# 63-00013_Battery_PCB_6_3.net
KiCad netlist of a schematic drawn in EAGLE
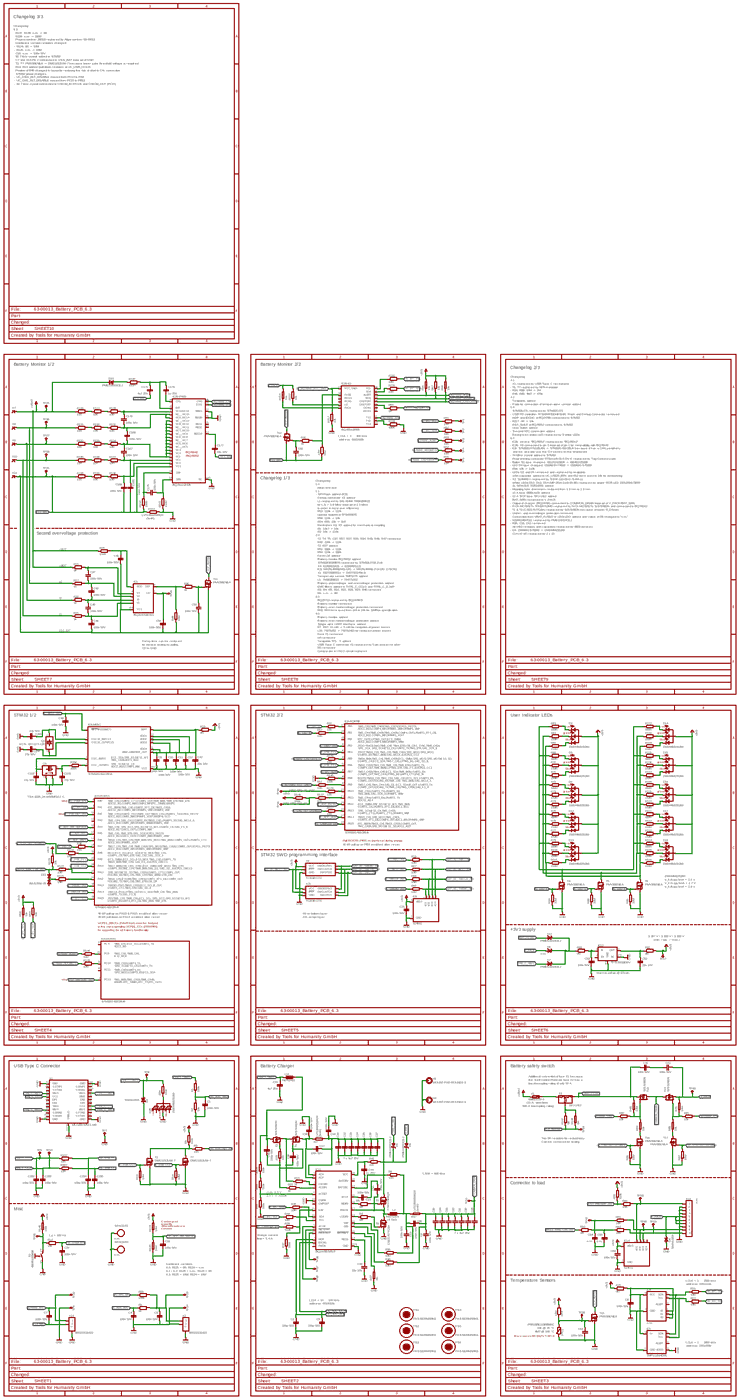
[diagram p0: schematic, sheet 1, overview]
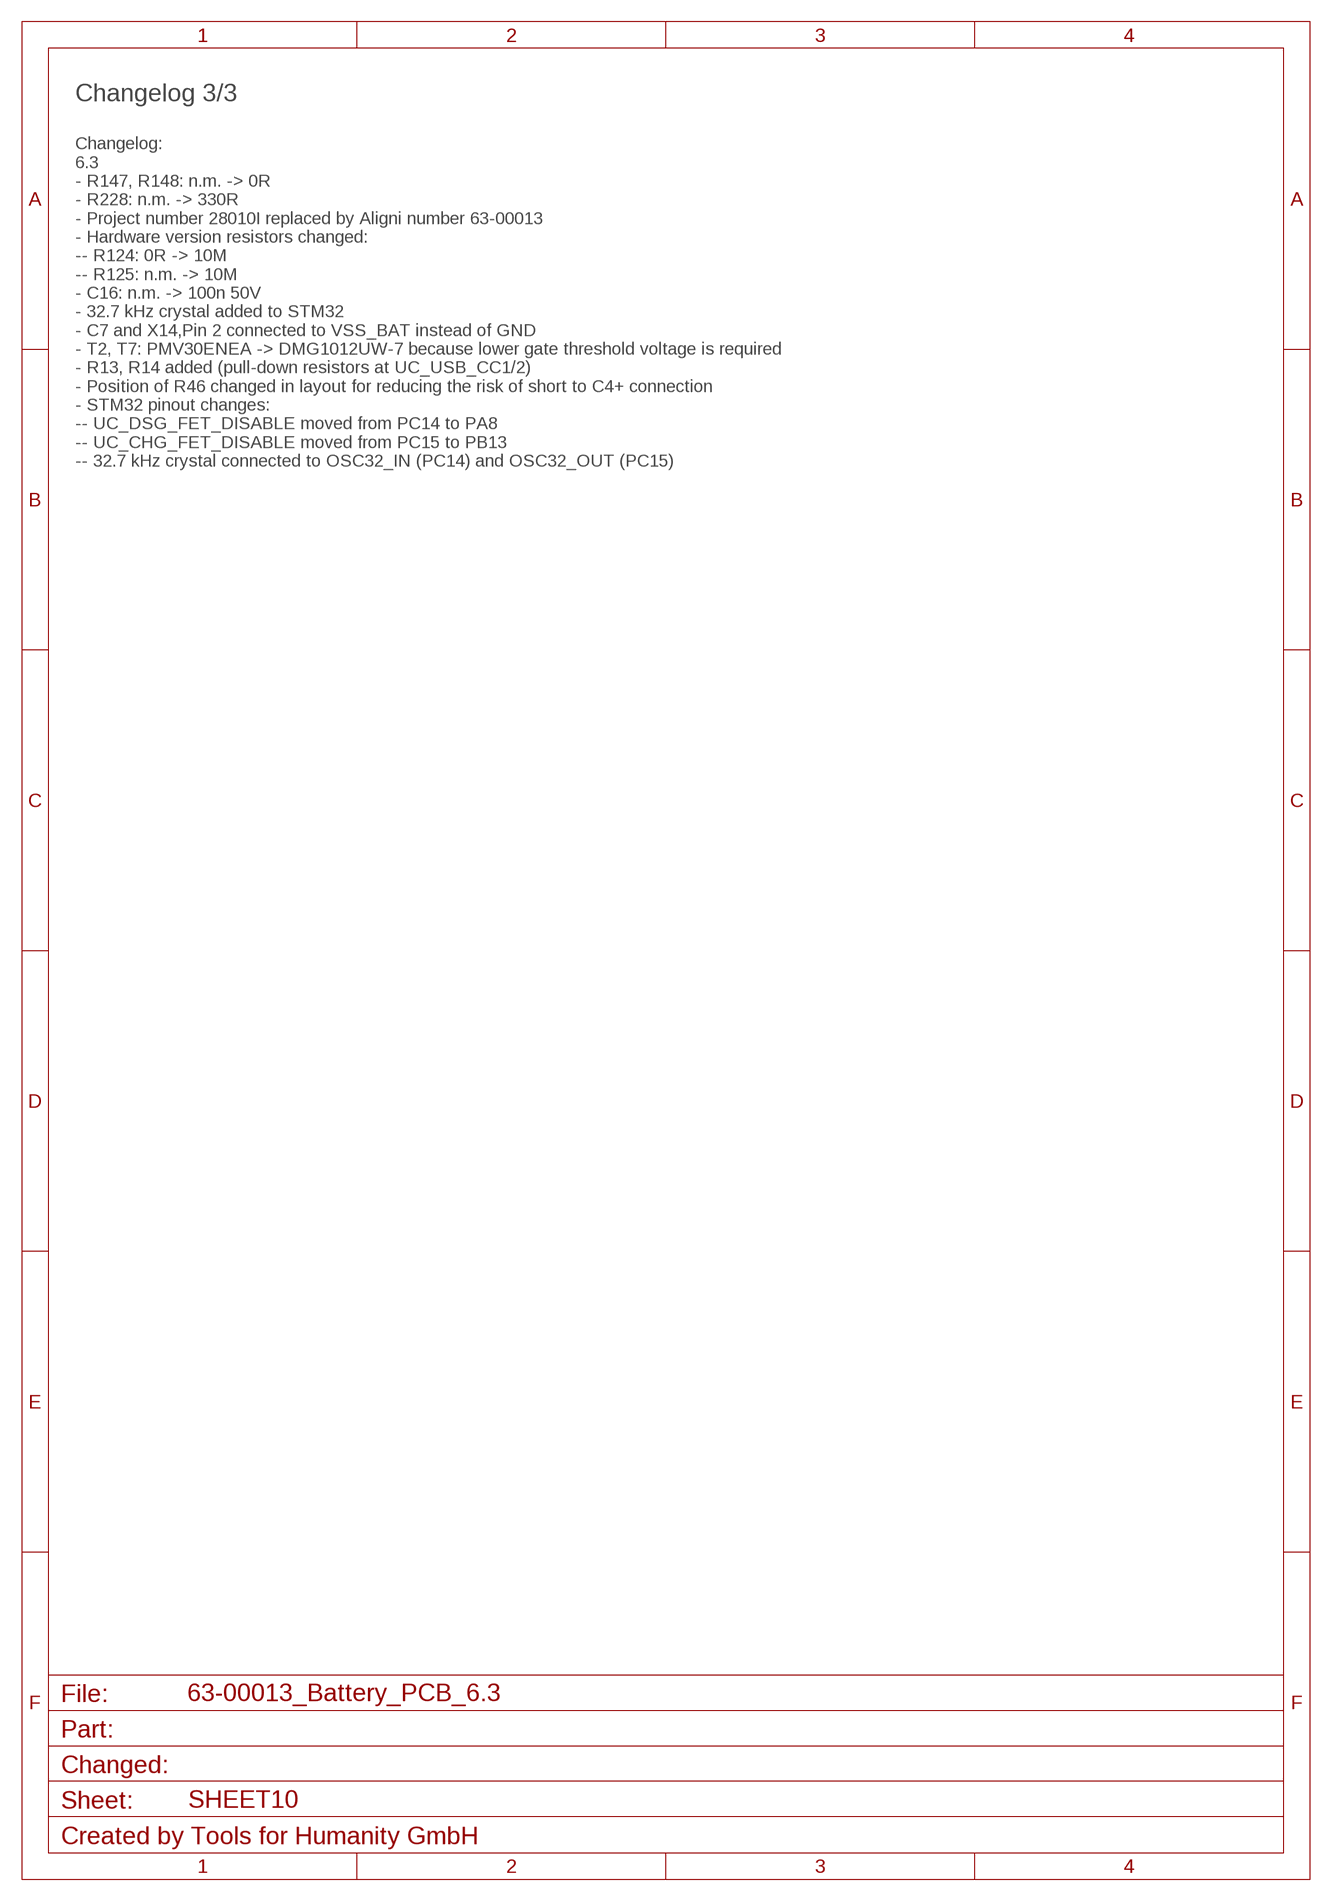
[diagram p1: schematic, sheet 1, part 1 of 7]
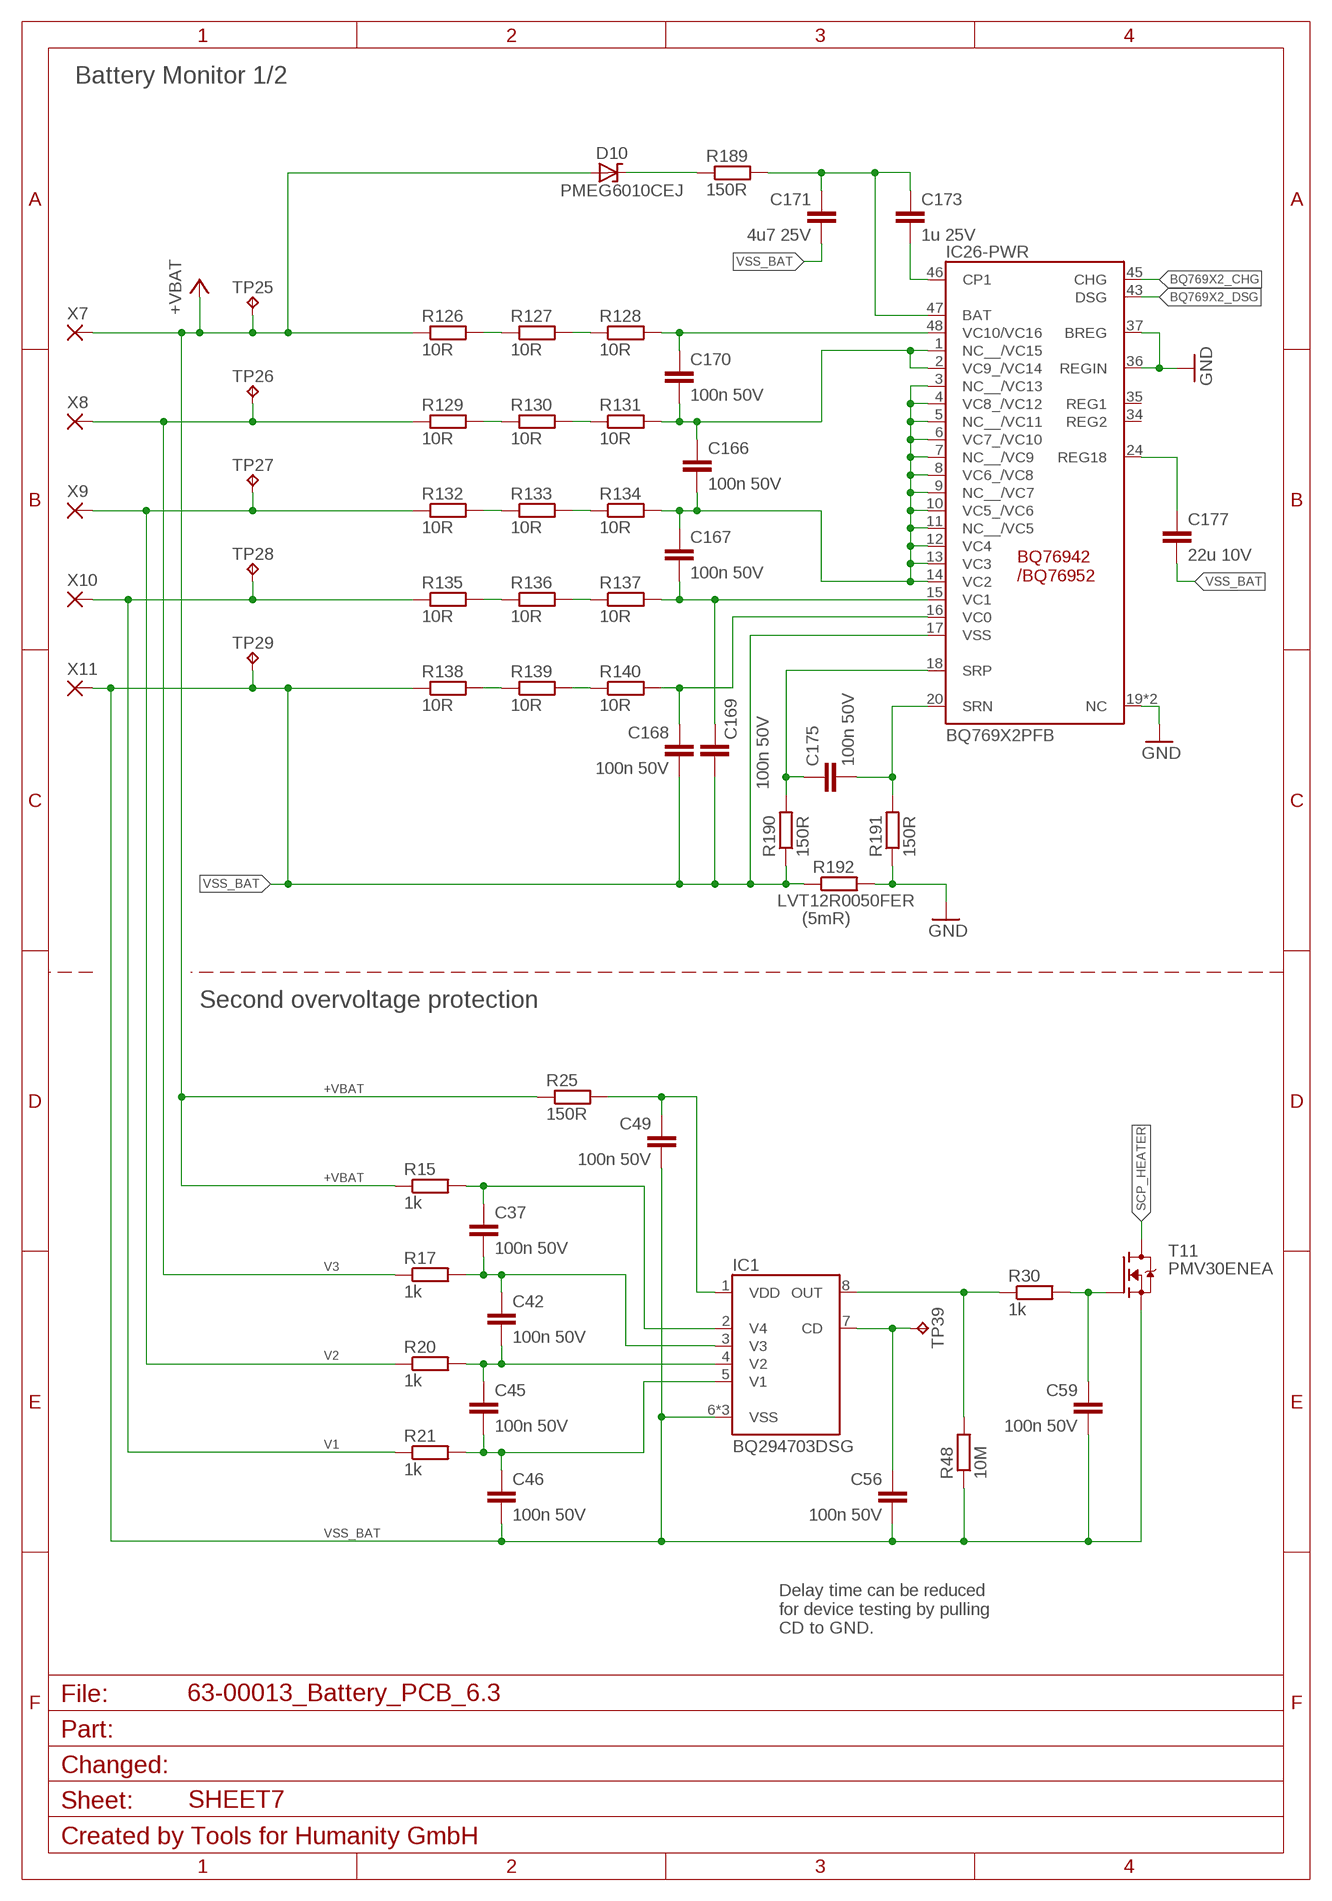
[diagram p2: schematic, sheet 1, part 2 of 7]
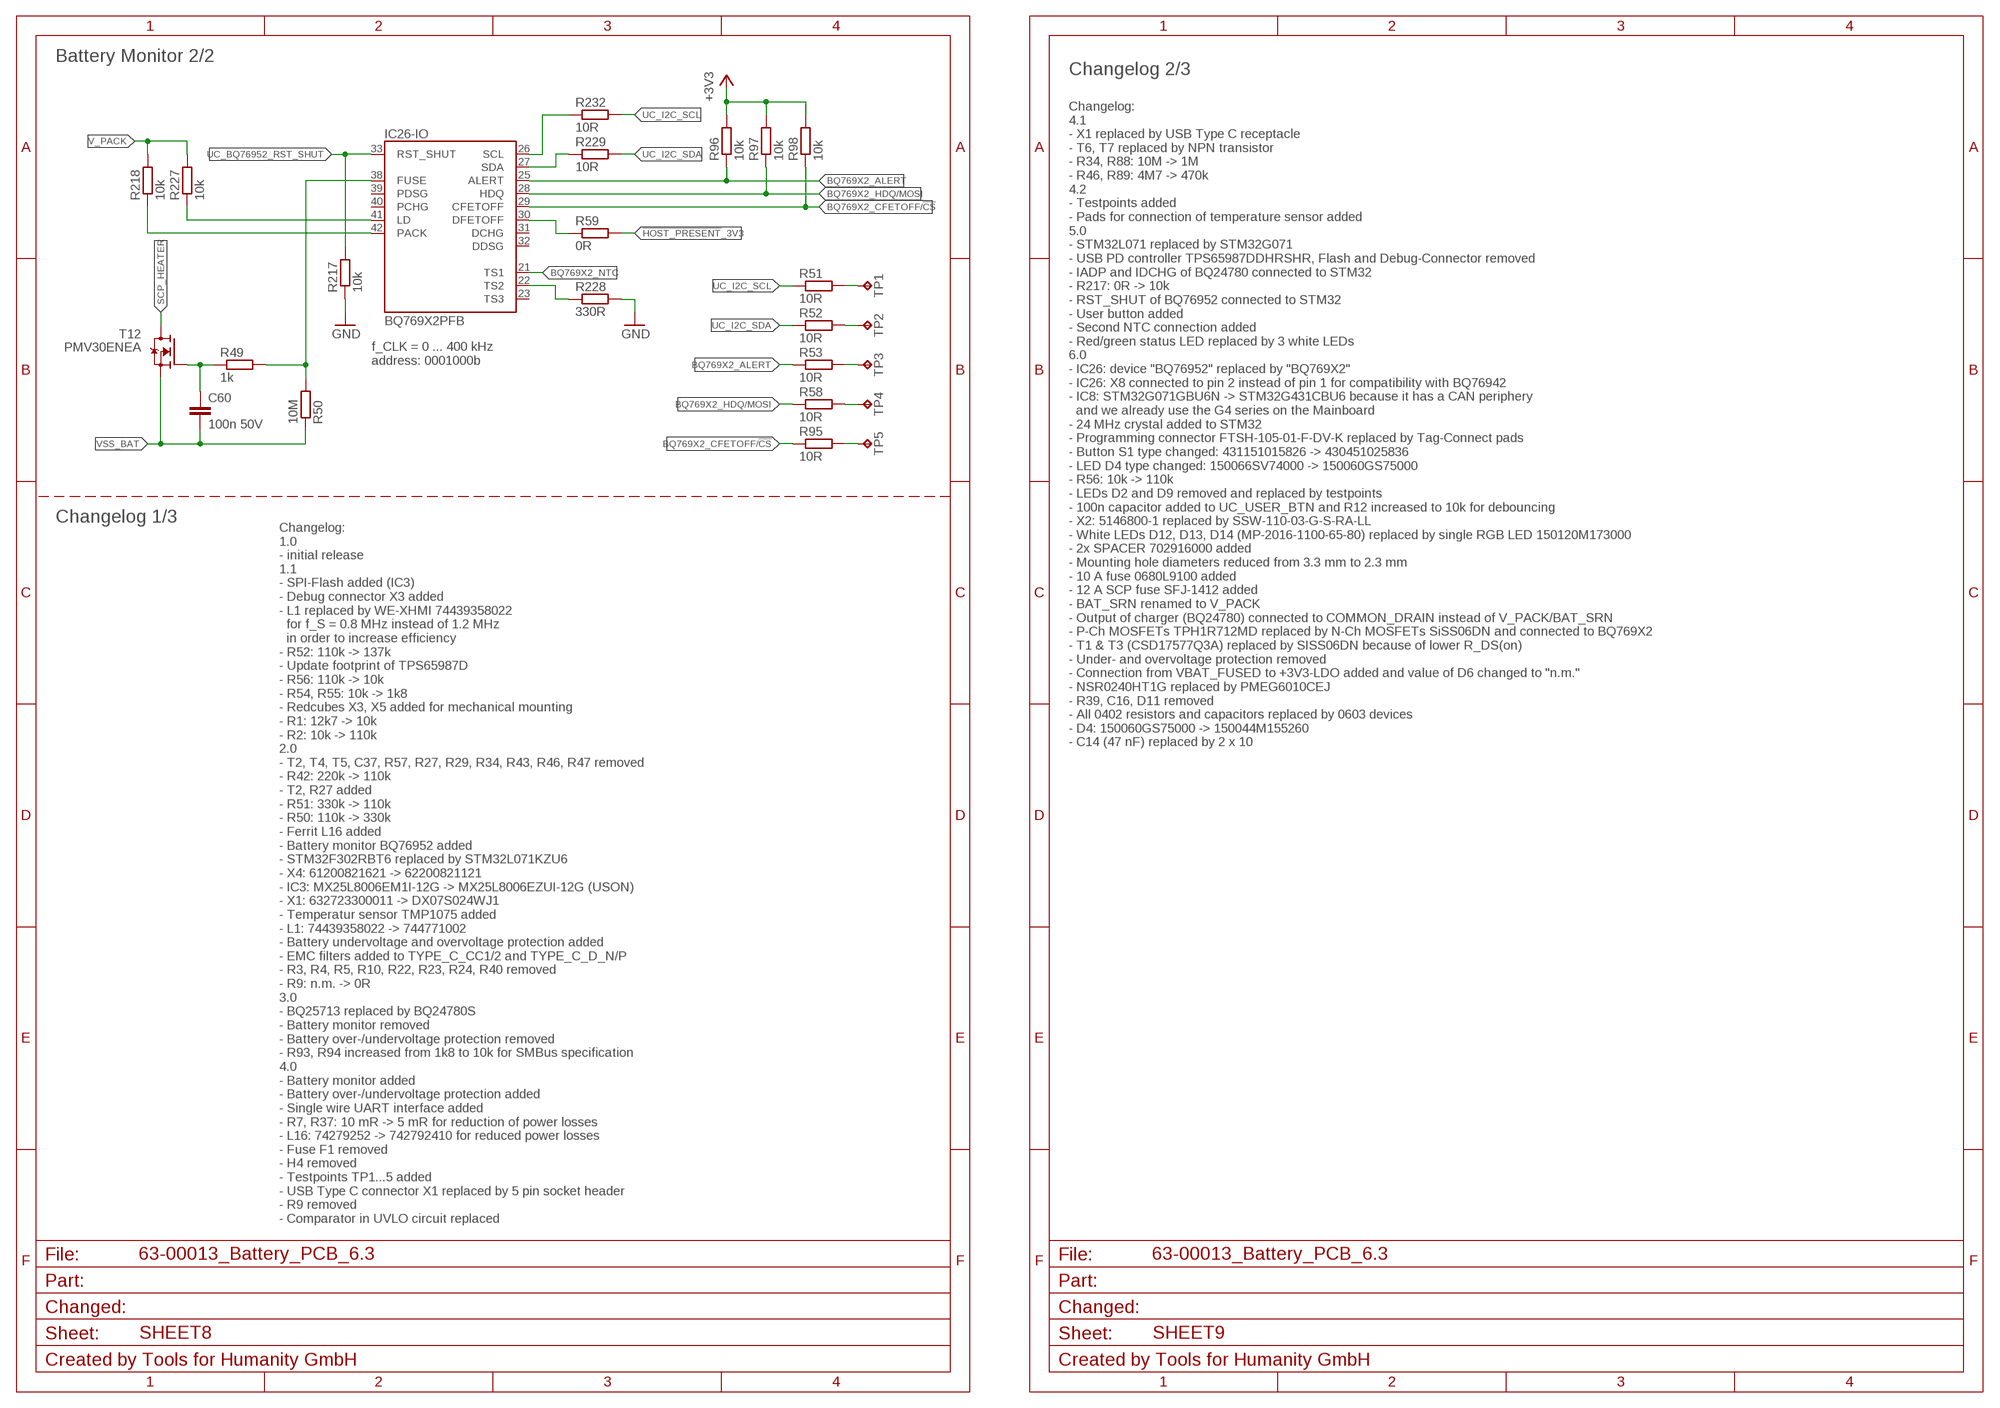
[diagram p3: schematic, sheet 1, part 3 of 7]
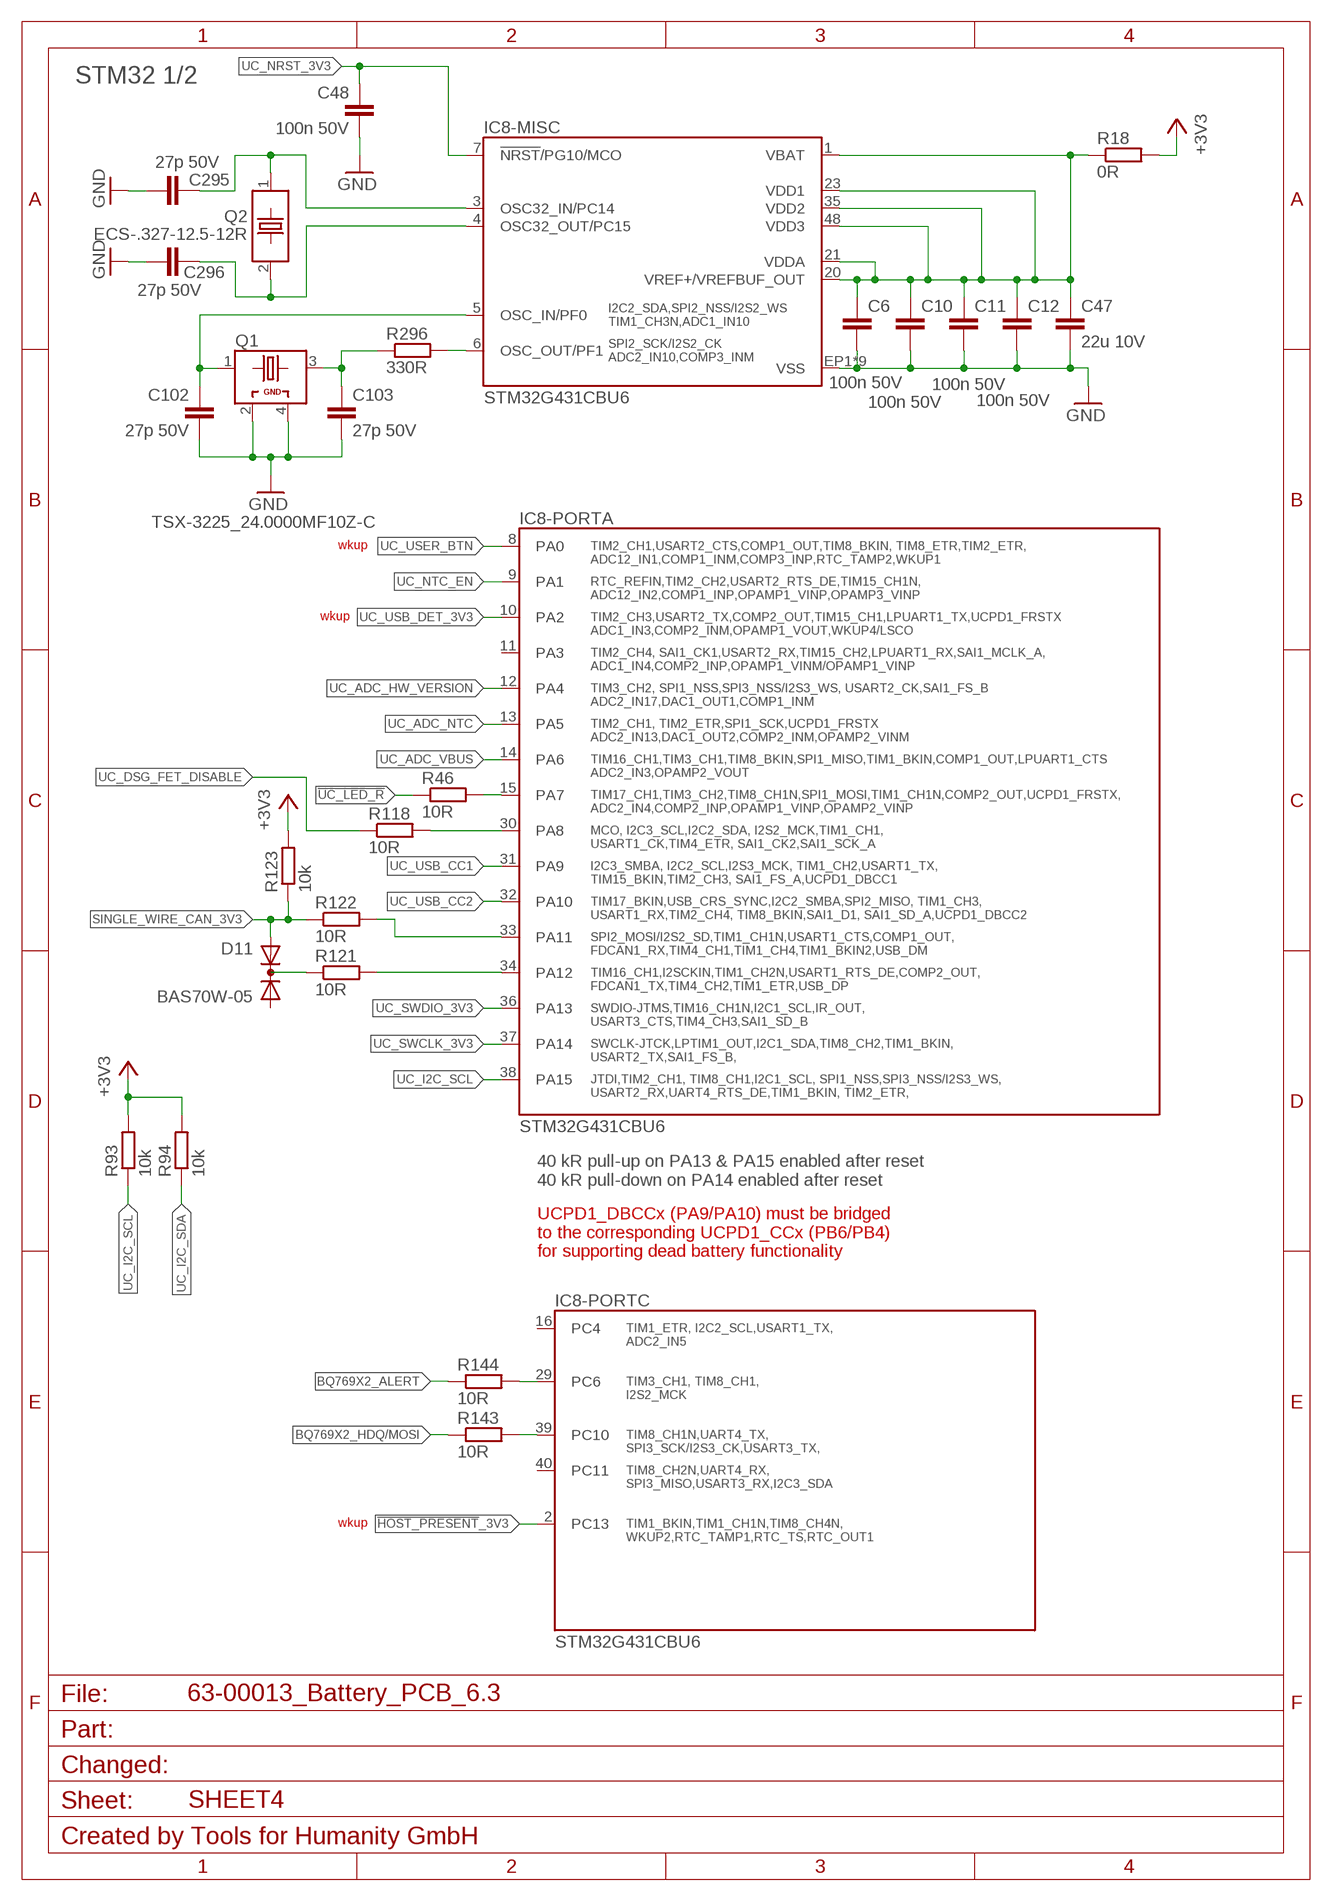
[diagram p4: schematic, sheet 1, part 4 of 7]
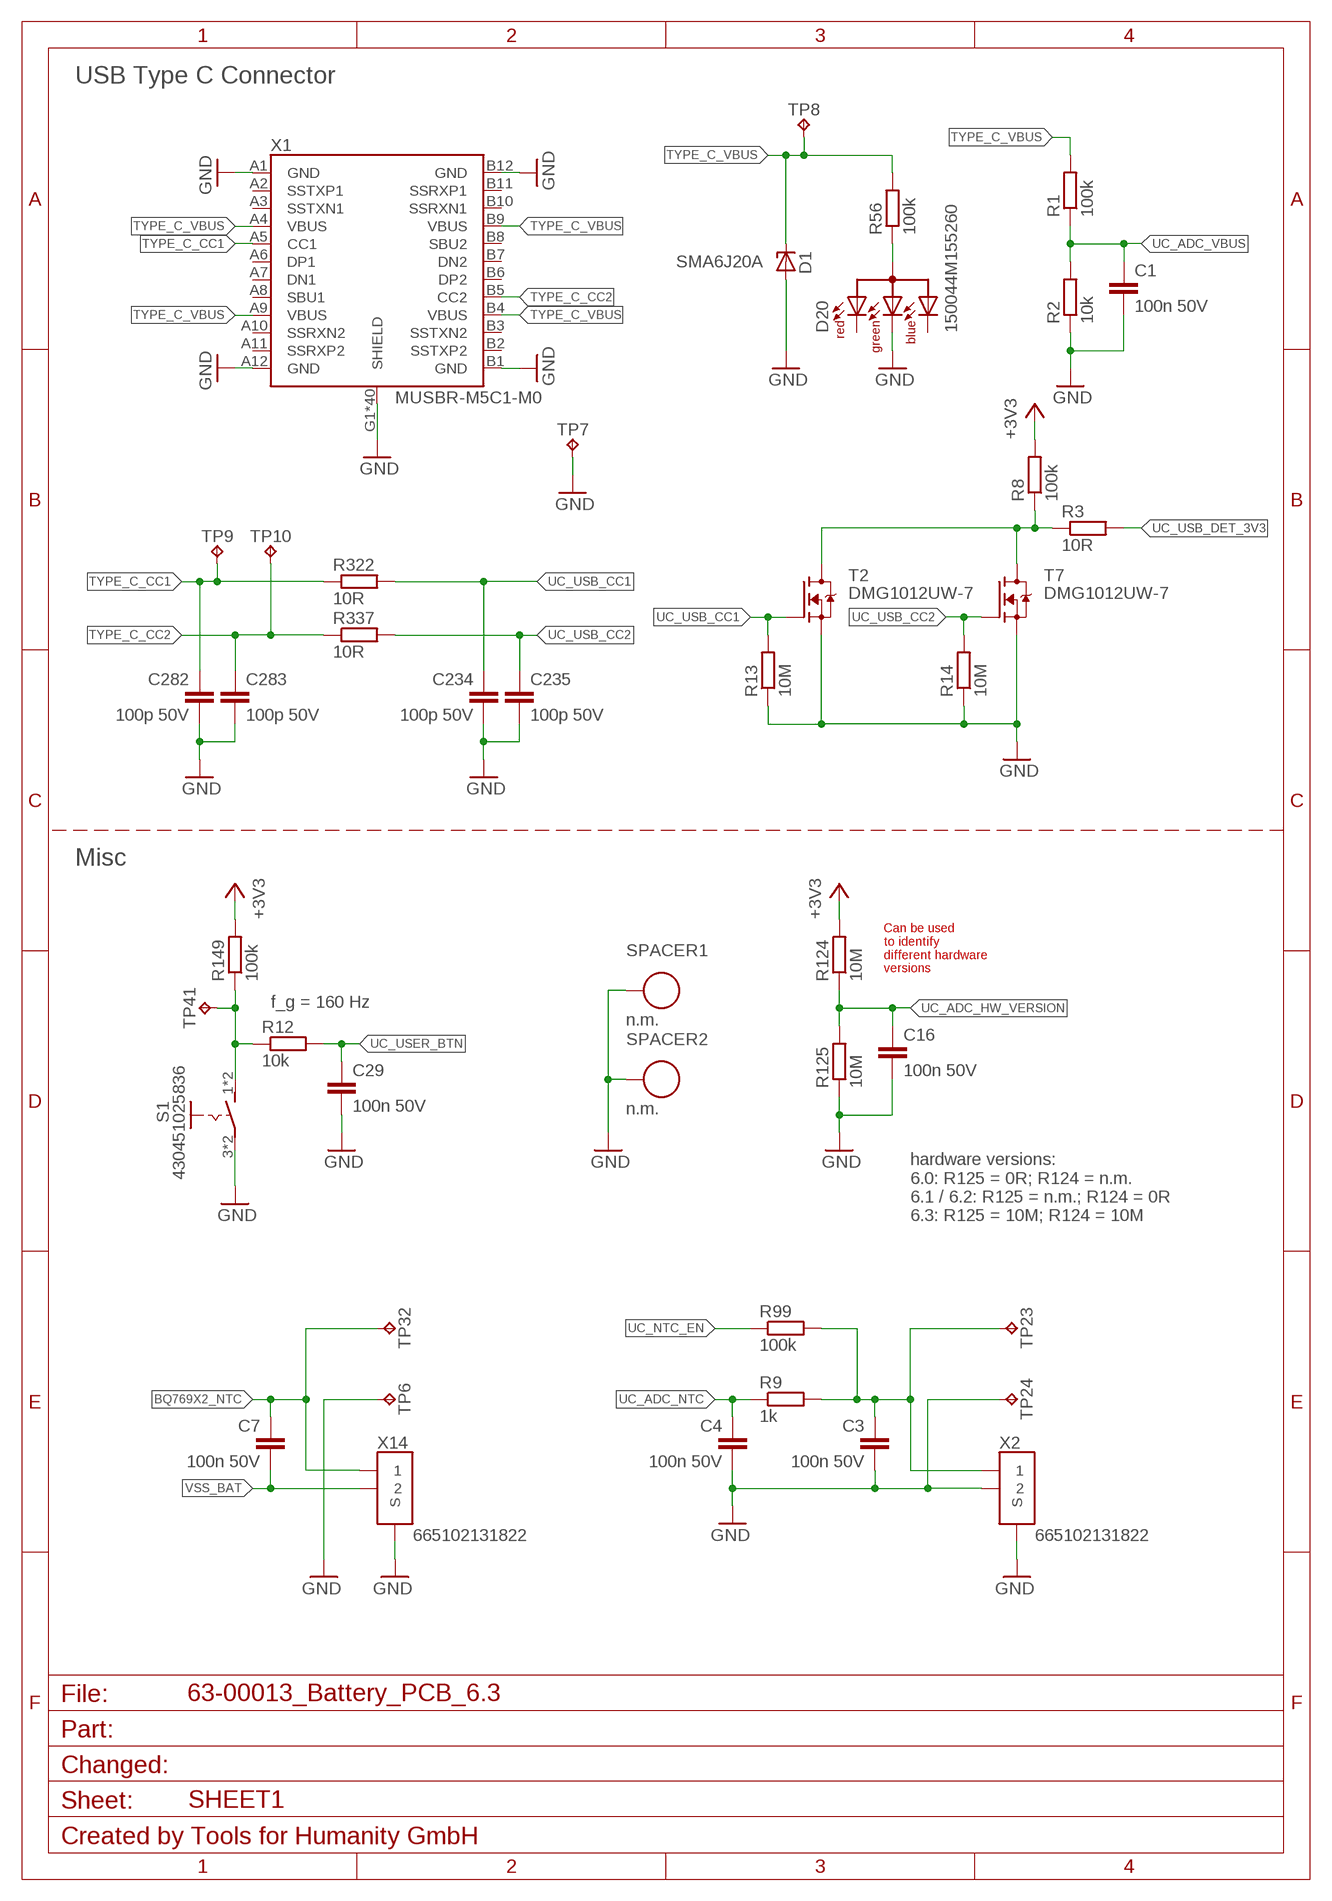
[diagram p5: schematic, sheet 1, part 5 of 7]
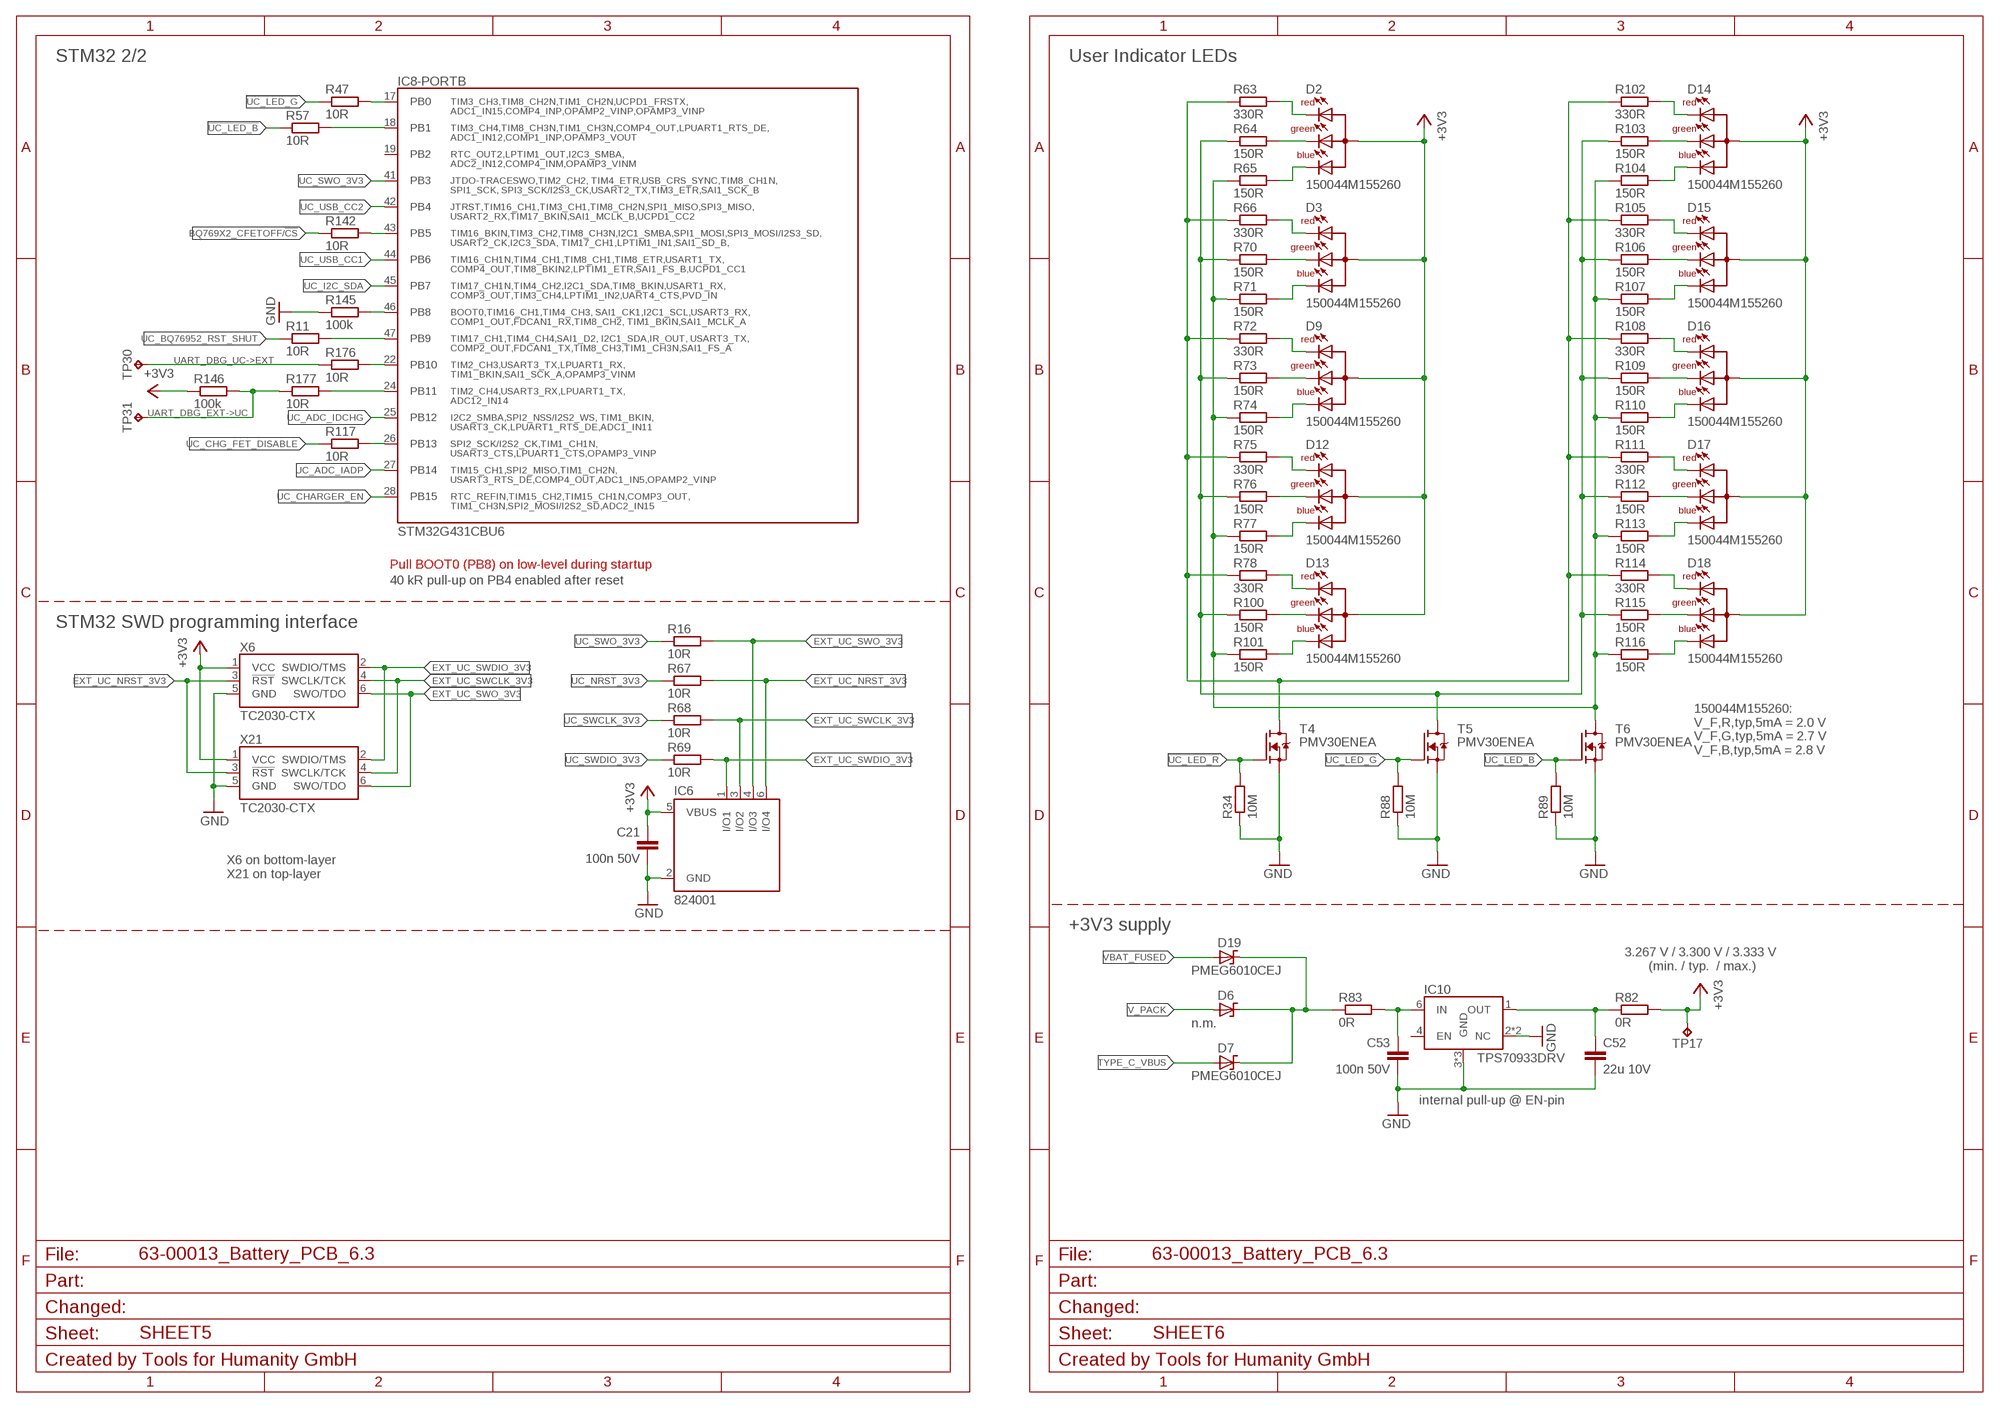
[diagram p6: schematic, sheet 1, part 6 of 7]
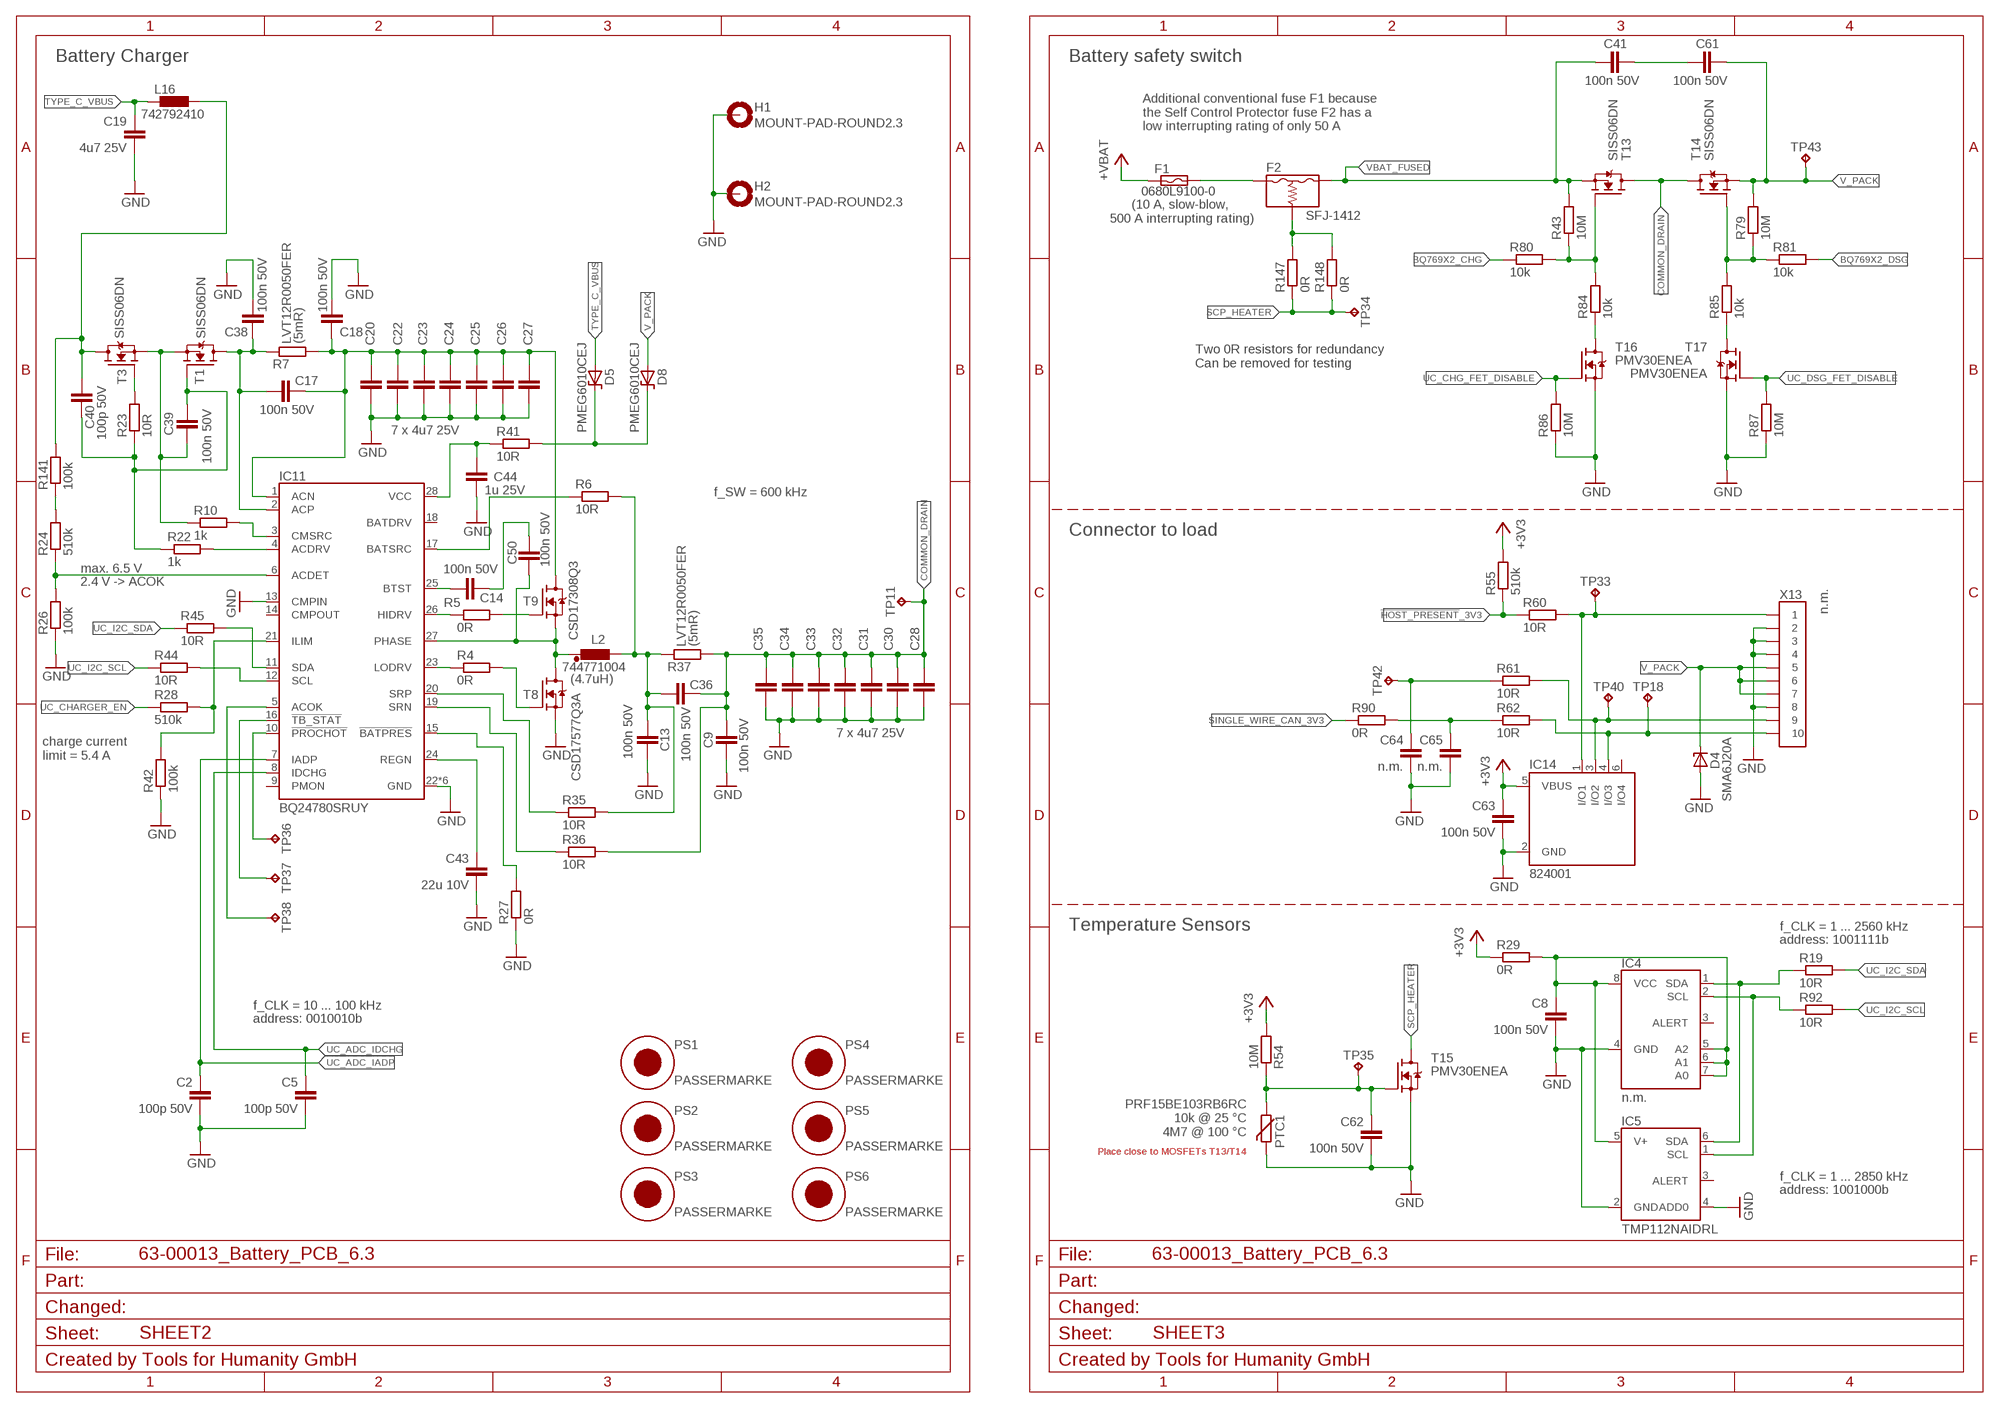
[diagram p7: schematic, sheet 1, part 7 of 7]

(export (version "E")
  (design (tool "Eeschema 10.0.6"))
  (components
    (comp (ref "C1")
      (value "100n 50V")
      (footprint "eagle-import:C0603")
      (fields
        (field (name "MANUFACTURER") "AVX")
        (field (name "TOLERANCE") "±20 %")
        (field (name "VOLTAGE") "50.0 V")
      )
      (libsource (lib "eagle-import") (part "C-EU-C0603-100N"))
    )
    (comp (ref "C2")
      (value "100p 50V")
      (footprint "eagle-import:C0603")
      (fields
        (field (name "MANUFACTURER") "Walsin")
        (field (name "TOLERANCE") "±10 %")
        (field (name "VOLTAGE") "50.0 V")
      )
      (libsource (lib "eagle-import") (part "C-EU-C0603-100P"))
    )
    (comp (ref "C3")
      (value "100n 50V")
      (footprint "eagle-import:C0603")
      (fields
        (field (name "MANUFACTURER") "AVX")
        (field (name "TOLERANCE") "±20 %")
        (field (name "VOLTAGE") "50.0 V")
      )
      (libsource (lib "eagle-import") (part "C-EU-C0603-100N"))
    )
    (comp (ref "C4")
      (value "100n 50V")
      (footprint "eagle-import:C0603")
      (fields
        (field (name "MANUFACTURER") "AVX")
        (field (name "TOLERANCE") "±20 %")
        (field (name "VOLTAGE") "50.0 V")
      )
      (libsource (lib "eagle-import") (part "C-EU-C0603-100N"))
    )
    (comp (ref "C5")
      (value "100p 50V")
      (footprint "eagle-import:C0603")
      (fields
        (field (name "MANUFACTURER") "Walsin")
        (field (name "TOLERANCE") "±10 %")
        (field (name "VOLTAGE") "50.0 V")
      )
      (libsource (lib "eagle-import") (part "C-EU-C0603-100P"))
    )
    (comp (ref "C6")
      (value "100n 50V")
      (footprint "eagle-import:C0603")
      (fields
        (field (name "MANUFACTURER") "AVX")
        (field (name "TOLERANCE") "±20 %")
        (field (name "VOLTAGE") "50.0 V")
      )
      (libsource (lib "eagle-import") (part "C-EU-C0603-100N"))
    )
    (comp (ref "C7")
      (value "100n 50V")
      (footprint "eagle-import:C0603")
      (fields
        (field (name "MANUFACTURER") "AVX")
        (field (name "TOLERANCE") "±20 %")
        (field (name "VOLTAGE") "50.0 V")
      )
      (libsource (lib "eagle-import") (part "C-EU-C0603-100N"))
    )
    (comp (ref "C8")
      (value "100n 50V")
      (footprint "eagle-import:C0603")
      (fields
        (field (name "MANUFACTURER") "AVX")
        (field (name "TOLERANCE") "±20 %")
        (field (name "VOLTAGE") "50.0 V")
      )
      (libsource (lib "eagle-import") (part "C-EU-C0603-100N"))
    )
    (comp (ref "C9")
      (value "100n 50V")
      (footprint "eagle-import:C0603")
      (fields
        (field (name "MANUFACTURER") "AVX")
        (field (name "TOLERANCE") "±20 %")
        (field (name "VOLTAGE") "50.0 V")
      )
      (libsource (lib "eagle-import") (part "C-EU-C0603-100N"))
    )
    (comp (ref "C10")
      (value "100n 50V")
      (footprint "eagle-import:C0603")
      (fields
        (field (name "MANUFACTURER") "AVX")
        (field (name "TOLERANCE") "±20 %")
        (field (name "VOLTAGE") "50.0 V")
      )
      (libsource (lib "eagle-import") (part "C-EU-C0603-100N"))
    )
    (comp (ref "C11")
      (value "100n 50V")
      (footprint "eagle-import:C0603")
      (fields
        (field (name "MANUFACTURER") "AVX")
        (field (name "TOLERANCE") "±20 %")
        (field (name "VOLTAGE") "50.0 V")
      )
      (libsource (lib "eagle-import") (part "C-EU-C0603-100N"))
    )
    (comp (ref "C12")
      (value "100n 50V")
      (footprint "eagle-import:C0603")
      (fields
        (field (name "MANUFACTURER") "AVX")
        (field (name "TOLERANCE") "±20 %")
        (field (name "VOLTAGE") "50.0 V")
      )
      (libsource (lib "eagle-import") (part "C-EU-C0603-100N"))
    )
    (comp (ref "C13")
      (value "100n 50V")
      (footprint "eagle-import:C0603")
      (fields
        (field (name "MANUFACTURER") "AVX")
        (field (name "TOLERANCE") "±20 %")
        (field (name "VOLTAGE") "50.0 V")
      )
      (libsource (lib "eagle-import") (part "C-EU-C0603-100N"))
    )
    (comp (ref "C14")
      (value "100n 50V")
      (footprint "eagle-import:C0603")
      (fields
        (field (name "MANUFACTURER") "AVX")
        (field (name "TOLERANCE") "±20 %")
        (field (name "VOLTAGE") "50.0 V")
      )
      (libsource (lib "eagle-import") (part "C-EU-C0603-100N"))
    )
    (comp (ref "C16")
      (value "100n 50V")
      (footprint "eagle-import:C0603")
      (fields
        (field (name "MANUFACTURER") "AVX")
        (field (name "TOLERANCE") "±20 %")
        (field (name "VOLTAGE") "50.0 V")
      )
      (libsource (lib "eagle-import") (part "C-EU-C0603-100N"))
    )
    (comp (ref "C17")
      (value "100n 50V")
      (footprint "eagle-import:C0603")
      (fields
        (field (name "MANUFACTURER") "AVX")
        (field (name "TOLERANCE") "±20 %")
        (field (name "VOLTAGE") "50.0 V")
      )
      (libsource (lib "eagle-import") (part "C-EU-C0603-100N"))
    )
    (comp (ref "C18")
      (value "100n 50V")
      (footprint "eagle-import:C0603")
      (fields
        (field (name "MANUFACTURER") "AVX")
        (field (name "TOLERANCE") "±20 %")
        (field (name "VOLTAGE") "50.0 V")
      )
      (libsource (lib "eagle-import") (part "C-EU-C0603-100N"))
    )
    (comp (ref "C19")
      (value "4u7 25V")
      (footprint "eagle-import:C1210")
      (fields
        (field (name "MANUFACTURER") "Taiyo Yuden")
        (field (name "TOLERANCE") "±20 %")
        (field (name "VOLTAGE") "25.0 V")
      )
      (libsource (lib "eagle-import") (part "C-EU-C1210-4U7-25V"))
    )
    (comp (ref "C20")
      (value "4u7 25V")
      (footprint "eagle-import:C1210")
      (fields
        (field (name "MANUFACTURER") "Taiyo Yuden")
        (field (name "TOLERANCE") "±20 %")
        (field (name "VOLTAGE") "25.0 V")
      )
      (libsource (lib "eagle-import") (part "C-EU-C1210-4U7-25V"))
    )
    (comp (ref "C21")
      (value "100n 50V")
      (footprint "eagle-import:C0603")
      (fields
        (field (name "MANUFACTURER") "AVX")
        (field (name "TOLERANCE") "±20 %")
        (field (name "VOLTAGE") "50.0 V")
      )
      (libsource (lib "eagle-import") (part "C-EU-C0603-100N"))
    )
    (comp (ref "C22")
      (value "4u7 25V")
      (footprint "eagle-import:C1210")
      (fields
        (field (name "MANUFACTURER") "Taiyo Yuden")
        (field (name "TOLERANCE") "±20 %")
        (field (name "VOLTAGE") "25.0 V")
      )
      (libsource (lib "eagle-import") (part "C-EU-C1210-4U7-25V"))
    )
    (comp (ref "C23")
      (value "4u7 25V")
      (footprint "eagle-import:C1210")
      (fields
        (field (name "MANUFACTURER") "Taiyo Yuden")
        (field (name "TOLERANCE") "±20 %")
        (field (name "VOLTAGE") "25.0 V")
      )
      (libsource (lib "eagle-import") (part "C-EU-C1210-4U7-25V"))
    )
    (comp (ref "C24")
      (value "4u7 25V")
      (footprint "eagle-import:C1210")
      (fields
        (field (name "MANUFACTURER") "Taiyo Yuden")
        (field (name "TOLERANCE") "±20 %")
        (field (name "VOLTAGE") "25.0 V")
      )
      (libsource (lib "eagle-import") (part "C-EU-C1210-4U7-25V"))
    )
    (comp (ref "C25")
      (value "4u7 25V")
      (footprint "eagle-import:C1210")
      (fields
        (field (name "MANUFACTURER") "Taiyo Yuden")
        (field (name "TOLERANCE") "±20 %")
        (field (name "VOLTAGE") "25.0 V")
      )
      (libsource (lib "eagle-import") (part "C-EU-C1210-4U7-25V"))
    )
    (comp (ref "C26")
      (value "4u7 25V")
      (footprint "eagle-import:C1210")
      (fields
        (field (name "MANUFACTURER") "Taiyo Yuden")
        (field (name "TOLERANCE") "±20 %")
        (field (name "VOLTAGE") "25.0 V")
      )
      (libsource (lib "eagle-import") (part "C-EU-C1210-4U7-25V"))
    )
    (comp (ref "C27")
      (value "4u7 25V")
      (footprint "eagle-import:C1210")
      (fields
        (field (name "MANUFACTURER") "Taiyo Yuden")
        (field (name "TOLERANCE") "±20 %")
        (field (name "VOLTAGE") "25.0 V")
      )
      (libsource (lib "eagle-import") (part "C-EU-C1210-4U7-25V"))
    )
    (comp (ref "C28")
      (value "4u7 25V")
      (footprint "eagle-import:C1210")
      (fields
        (field (name "MANUFACTURER") "Taiyo Yuden")
        (field (name "TOLERANCE") "±20 %")
        (field (name "VOLTAGE") "25.0 V")
      )
      (libsource (lib "eagle-import") (part "C-EU-C1210-4U7-25V"))
    )
    (comp (ref "C29")
      (value "100n 50V")
      (footprint "eagle-import:C0603")
      (fields
        (field (name "MANUFACTURER") "AVX")
        (field (name "TOLERANCE") "±20 %")
        (field (name "VOLTAGE") "50.0 V")
      )
      (libsource (lib "eagle-import") (part "C-EU-C0603-100N"))
    )
    (comp (ref "C30")
      (value "4u7 25V")
      (footprint "eagle-import:C1210")
      (fields
        (field (name "MANUFACTURER") "Taiyo Yuden")
        (field (name "TOLERANCE") "±20 %")
        (field (name "VOLTAGE") "25.0 V")
      )
      (libsource (lib "eagle-import") (part "C-EU-C1210-4U7-25V"))
    )
    (comp (ref "C31")
      (value "4u7 25V")
      (footprint "eagle-import:C1210")
      (fields
        (field (name "MANUFACTURER") "Taiyo Yuden")
        (field (name "TOLERANCE") "±20 %")
        (field (name "VOLTAGE") "25.0 V")
      )
      (libsource (lib "eagle-import") (part "C-EU-C1210-4U7-25V"))
    )
    (comp (ref "C32")
      (value "4u7 25V")
      (footprint "eagle-import:C1210")
      (fields
        (field (name "MANUFACTURER") "Taiyo Yuden")
        (field (name "TOLERANCE") "±20 %")
        (field (name "VOLTAGE") "25.0 V")
      )
      (libsource (lib "eagle-import") (part "C-EU-C1210-4U7-25V"))
    )
    (comp (ref "C33")
      (value "4u7 25V")
      (footprint "eagle-import:C1210")
      (fields
        (field (name "MANUFACTURER") "Taiyo Yuden")
        (field (name "TOLERANCE") "±20 %")
        (field (name "VOLTAGE") "25.0 V")
      )
      (libsource (lib "eagle-import") (part "C-EU-C1210-4U7-25V"))
    )
    (comp (ref "C34")
      (value "4u7 25V")
      (footprint "eagle-import:C1210")
      (fields
        (field (name "MANUFACTURER") "Taiyo Yuden")
        (field (name "TOLERANCE") "±20 %")
        (field (name "VOLTAGE") "25.0 V")
      )
      (libsource (lib "eagle-import") (part "C-EU-C1210-4U7-25V"))
    )
    (comp (ref "C35")
      (value "4u7 25V")
      (footprint "eagle-import:C1210")
      (fields
        (field (name "MANUFACTURER") "Taiyo Yuden")
        (field (name "TOLERANCE") "±20 %")
        (field (name "VOLTAGE") "25.0 V")
      )
      (libsource (lib "eagle-import") (part "C-EU-C1210-4U7-25V"))
    )
    (comp (ref "C36")
      (value "100n 50V")
      (footprint "eagle-import:C0603")
      (fields
        (field (name "MANUFACTURER") "AVX")
        (field (name "TOLERANCE") "±20 %")
        (field (name "VOLTAGE") "50.0 V")
      )
      (libsource (lib "eagle-import") (part "C-EU-C0603-100N"))
    )
    (comp (ref "C37")
      (value "100n 50V")
      (footprint "eagle-import:C0603")
      (fields
        (field (name "MANUFACTURER") "AVX")
        (field (name "TOLERANCE") "±20 %")
        (field (name "VOLTAGE") "50.0 V")
      )
      (libsource (lib "eagle-import") (part "C-EU-C0603-100N"))
    )
    (comp (ref "C38")
      (value "100n 50V")
      (footprint "eagle-import:C0603")
      (fields
        (field (name "MANUFACTURER") "AVX")
        (field (name "TOLERANCE") "±20 %")
        (field (name "VOLTAGE") "50.0 V")
      )
      (libsource (lib "eagle-import") (part "C-EU-C0603-100N"))
    )
    (comp (ref "C39")
      (value "100n 50V")
      (footprint "eagle-import:C0603")
      (fields
        (field (name "MANUFACTURER") "AVX")
        (field (name "TOLERANCE") "±20 %")
        (field (name "VOLTAGE") "50.0 V")
      )
      (libsource (lib "eagle-import") (part "C-EU-C0603-100N"))
    )
    (comp (ref "C40")
      (value "100p 50V")
      (footprint "eagle-import:C0603")
      (fields
        (field (name "MANUFACTURER") "Walsin")
        (field (name "TOLERANCE") "±10 %")
        (field (name "VOLTAGE") "50.0 V")
      )
      (libsource (lib "eagle-import") (part "C-EU-C0603-100P"))
    )
    (comp (ref "C41")
      (value "100n 50V")
      (footprint "eagle-import:C0603")
      (fields
        (field (name "MANUFACTURER") "AVX")
        (field (name "TOLERANCE") "±20 %")
        (field (name "VOLTAGE") "50.0 V")
      )
      (libsource (lib "eagle-import") (part "C-EU-C0603-100N"))
    )
    (comp (ref "C42")
      (value "100n 50V")
      (footprint "eagle-import:C0603")
      (fields
        (field (name "MANUFACTURER") "AVX")
        (field (name "TOLERANCE") "±20 %")
        (field (name "VOLTAGE") "50.0 V")
      )
      (libsource (lib "eagle-import") (part "C-EU-C0603-100N"))
    )
    (comp (ref "C43")
      (value "22u 10V")
      (footprint "eagle-import:C0805")
      (fields
        (field (name "MANUFACTURER") "AVX")
        (field (name "TOLERANCE") "±20 %")
        (field (name "VOLTAGE") "10.0 V")
      )
      (libsource (lib "eagle-import") (part "C-EU-C0805-22U"))
    )
    (comp (ref "C44")
      (value "1u 25V")
      (footprint "eagle-import:C0805")
      (fields
        (field (name "MANUFACTURER") "AVX")
        (field (name "TOLERANCE") "±20 %")
        (field (name "VOLTAGE") "25.0 V")
      )
      (libsource (lib "eagle-import") (part "C-EU-C0805-1U"))
    )
    (comp (ref "C45")
      (value "100n 50V")
      (footprint "eagle-import:C0603")
      (fields
        (field (name "MANUFACTURER") "AVX")
        (field (name "TOLERANCE") "±20 %")
        (field (name "VOLTAGE") "50.0 V")
      )
      (libsource (lib "eagle-import") (part "C-EU-C0603-100N"))
    )
    (comp (ref "C46")
      (value "100n 50V")
      (footprint "eagle-import:C0603")
      (fields
        (field (name "MANUFACTURER") "AVX")
        (field (name "TOLERANCE") "±20 %")
        (field (name "VOLTAGE") "50.0 V")
      )
      (libsource (lib "eagle-import") (part "C-EU-C0603-100N"))
    )
    (comp (ref "C47")
      (value "22u 10V")
      (footprint "eagle-import:C0805")
      (fields
        (field (name "MANUFACTURER") "AVX")
        (field (name "TOLERANCE") "±20 %")
        (field (name "VOLTAGE") "10.0 V")
      )
      (libsource (lib "eagle-import") (part "C-EU-C0805-22U"))
    )
    (comp (ref "C48")
      (value "100n 50V")
      (footprint "eagle-import:C0603")
      (fields
        (field (name "MANUFACTURER") "AVX")
        (field (name "TOLERANCE") "±20 %")
        (field (name "VOLTAGE") "50.0 V")
      )
      (libsource (lib "eagle-import") (part "C-EU-C0603-100N"))
    )
    (comp (ref "C49")
      (value "100n 50V")
      (footprint "eagle-import:C0603")
      (fields
        (field (name "MANUFACTURER") "AVX")
        (field (name "TOLERANCE") "±20 %")
        (field (name "VOLTAGE") "50.0 V")
      )
      (libsource (lib "eagle-import") (part "C-EU-C0603-100N"))
    )
    (comp (ref "C50")
      (value "100n 50V")
      (footprint "eagle-import:C0603")
      (fields
        (field (name "MANUFACTURER") "AVX")
        (field (name "TOLERANCE") "±20 %")
        (field (name "VOLTAGE") "50.0 V")
      )
      (libsource (lib "eagle-import") (part "C-EU-C0603-100N"))
    )
    (comp (ref "C52")
      (value "22u 10V")
      (footprint "eagle-import:C0805")
      (fields
        (field (name "MANUFACTURER") "AVX")
        (field (name "TOLERANCE") "±20 %")
        (field (name "VOLTAGE") "10.0 V")
      )
      (libsource (lib "eagle-import") (part "C-EU-C0805-22U"))
    )
    (comp (ref "C53")
      (value "100n 50V")
      (footprint "eagle-import:C0603")
      (fields
        (field (name "MANUFACTURER") "AVX")
        (field (name "TOLERANCE") "±20 %")
        (field (name "VOLTAGE") "50.0 V")
      )
      (libsource (lib "eagle-import") (part "C-EU-C0603-100N"))
    )
    (comp (ref "C56")
      (value "100n 50V")
      (footprint "eagle-import:C0603")
      (fields
        (field (name "MANUFACTURER") "AVX")
        (field (name "TOLERANCE") "±20 %")
        (field (name "VOLTAGE") "50.0 V")
      )
      (libsource (lib "eagle-import") (part "C-EU-C0603-100N"))
    )
    (comp (ref "C59")
      (value "100n 50V")
      (footprint "eagle-import:C0603")
      (fields
        (field (name "MANUFACTURER") "AVX")
        (field (name "TOLERANCE") "±20 %")
        (field (name "VOLTAGE") "50.0 V")
      )
      (libsource (lib "eagle-import") (part "C-EU-C0603-100N"))
    )
    (comp (ref "C60")
      (value "100n 50V")
      (footprint "eagle-import:C0603")
      (fields
        (field (name "MANUFACTURER") "AVX")
        (field (name "TOLERANCE") "±20 %")
        (field (name "VOLTAGE") "50.0 V")
      )
      (libsource (lib "eagle-import") (part "C-EU-C0603-100N"))
    )
    (comp (ref "C61")
      (value "100n 50V")
      (footprint "eagle-import:C0603")
      (fields
        (field (name "MANUFACTURER") "AVX")
        (field (name "TOLERANCE") "±20 %")
        (field (name "VOLTAGE") "50.0 V")
      )
      (libsource (lib "eagle-import") (part "C-EU-C0603-100N"))
    )
    (comp (ref "C62")
      (value "100n 50V")
      (footprint "eagle-import:C0603")
      (fields
        (field (name "MANUFACTURER") "AVX")
        (field (name "TOLERANCE") "±20 %")
        (field (name "VOLTAGE") "50.0 V")
      )
      (libsource (lib "eagle-import") (part "C-EU-C0603-100N"))
    )
    (comp (ref "C63")
      (value "100n 50V")
      (footprint "eagle-import:C0603")
      (fields
        (field (name "MANUFACTURER") "AVX")
        (field (name "TOLERANCE") "±20 %")
        (field (name "VOLTAGE") "50.0 V")
      )
      (libsource (lib "eagle-import") (part "C-EU-C0603-100N"))
    )
    (comp (ref "C64")
      (value "n.m.")
      (footprint "eagle-import:C0603")
      (fields (field (name "TOLERANCE") "±20 %") (field (name "VOLTAGE") "25.0 V"))
      (libsource (lib "eagle-import") (part "C-EU-C0603"))
    )
    (comp (ref "C65")
      (value "n.m.")
      (footprint "eagle-import:C0603")
      (fields (field (name "TOLERANCE") "±20 %") (field (name "VOLTAGE") "25.0 V"))
      (libsource (lib "eagle-import") (part "C-EU-C0603"))
    )
    (comp (ref "C102")
      (value "27p 50V")
      (footprint "eagle-import:C0603")
      (fields
        (field (name "MANUFACTURER") "AVX")
        (field (name "TOLERANCE") "±20 %")
        (field (name "VOLTAGE") "50.0 V")
      )
      (libsource (lib "eagle-import") (part "C-EU-C0603-27P"))
    )
    (comp (ref "C103")
      (value "27p 50V")
      (footprint "eagle-import:C0603")
      (fields
        (field (name "MANUFACTURER") "AVX")
        (field (name "TOLERANCE") "±20 %")
        (field (name "VOLTAGE") "50.0 V")
      )
      (libsource (lib "eagle-import") (part "C-EU-C0603-27P"))
    )
    (comp (ref "C166")
      (value "100n 50V")
      (footprint "eagle-import:C0603")
      (fields
        (field (name "MANUFACTURER") "AVX")
        (field (name "TOLERANCE") "±20 %")
        (field (name "VOLTAGE") "50.0 V")
      )
      (libsource (lib "eagle-import") (part "C-EU-C0603-100N"))
    )
    (comp (ref "C167")
      (value "100n 50V")
      (footprint "eagle-import:C0603")
      (fields
        (field (name "MANUFACTURER") "AVX")
        (field (name "TOLERANCE") "±20 %")
        (field (name "VOLTAGE") "50.0 V")
      )
      (libsource (lib "eagle-import") (part "C-EU-C0603-100N"))
    )
    (comp (ref "C168")
      (value "100n 50V")
      (footprint "eagle-import:C0603")
      (fields
        (field (name "MANUFACTURER") "AVX")
        (field (name "TOLERANCE") "±20 %")
        (field (name "VOLTAGE") "50.0 V")
      )
      (libsource (lib "eagle-import") (part "C-EU-C0603-100N"))
    )
    (comp (ref "C169")
      (value "100n 50V")
      (footprint "eagle-import:C0603")
      (fields
        (field (name "MANUFACTURER") "AVX")
        (field (name "TOLERANCE") "±20 %")
        (field (name "VOLTAGE") "50.0 V")
      )
      (libsource (lib "eagle-import") (part "C-EU-C0603-100N"))
    )
    (comp (ref "C170")
      (value "100n 50V")
      (footprint "eagle-import:C0603")
      (fields
        (field (name "MANUFACTURER") "AVX")
        (field (name "TOLERANCE") "±20 %")
        (field (name "VOLTAGE") "50.0 V")
      )
      (libsource (lib "eagle-import") (part "C-EU-C0603-100N"))
    )
    (comp (ref "C171")
      (value "4u7 25V")
      (footprint "eagle-import:C1210")
      (fields
        (field (name "MANUFACTURER") "Taiyo Yuden")
        (field (name "TOLERANCE") "±20 %")
        (field (name "VOLTAGE") "25.0 V")
      )
      (libsource (lib "eagle-import") (part "C-EU-C1210-4U7-25V"))
    )
    (comp (ref "C173")
      (value "1u 25V")
      (footprint "eagle-import:C0805")
      (fields
        (field (name "MANUFACTURER") "AVX")
        (field (name "TOLERANCE") "±20 %")
        (field (name "VOLTAGE") "25.0 V")
      )
      (libsource (lib "eagle-import") (part "C-EU-C0805-1U"))
    )
    (comp (ref "C175")
      (value "100n 50V")
      (footprint "eagle-import:C0603")
      (fields
        (field (name "MANUFACTURER") "AVX")
        (field (name "TOLERANCE") "±20 %")
        (field (name "VOLTAGE") "50.0 V")
      )
      (libsource (lib "eagle-import") (part "C-EU-C0603-100N"))
    )
    (comp (ref "C177")
      (value "22u 10V")
      (footprint "eagle-import:C0805")
      (fields
        (field (name "MANUFACTURER") "AVX")
        (field (name "TOLERANCE") "±20 %")
        (field (name "VOLTAGE") "10.0 V")
      )
      (libsource (lib "eagle-import") (part "C-EU-C0805-22U"))
    )
    (comp (ref "C234")
      (value "100p 50V")
      (footprint "eagle-import:C0603")
      (fields
        (field (name "MANUFACTURER") "Walsin")
        (field (name "TOLERANCE") "±10 %")
        (field (name "VOLTAGE") "50.0 V")
      )
      (libsource (lib "eagle-import") (part "C-EU-C0603-100P"))
    )
    (comp (ref "C235")
      (value "100p 50V")
      (footprint "eagle-import:C0603")
      (fields
        (field (name "MANUFACTURER") "Walsin")
        (field (name "TOLERANCE") "±10 %")
        (field (name "VOLTAGE") "50.0 V")
      )
      (libsource (lib "eagle-import") (part "C-EU-C0603-100P"))
    )
    (comp (ref "C282")
      (value "100p 50V")
      (footprint "eagle-import:C0603")
      (fields
        (field (name "MANUFACTURER") "Walsin")
        (field (name "TOLERANCE") "±10 %")
        (field (name "VOLTAGE") "50.0 V")
      )
      (libsource (lib "eagle-import") (part "C-EU-C0603-100P"))
    )
    (comp (ref "C283")
      (value "100p 50V")
      (footprint "eagle-import:C0603")
      (fields
        (field (name "MANUFACTURER") "Walsin")
        (field (name "TOLERANCE") "±10 %")
        (field (name "VOLTAGE") "50.0 V")
      )
      (libsource (lib "eagle-import") (part "C-EU-C0603-100P"))
    )
    (comp (ref "C295")
      (value "27p 50V")
      (footprint "eagle-import:C0603")
      (fields
        (field (name "MANUFACTURER") "AVX")
        (field (name "TOLERANCE") "±20 %")
        (field (name "VOLTAGE") "50.0 V")
      )
      (libsource (lib "eagle-import") (part "C-EU-C0603-27P"))
    )
    (comp (ref "C296")
      (value "27p 50V")
      (footprint "eagle-import:C0603")
      (fields
        (field (name "MANUFACTURER") "AVX")
        (field (name "TOLERANCE") "±20 %")
        (field (name "VOLTAGE") "50.0 V")
      )
      (libsource (lib "eagle-import") (part "C-EU-C0603-27P"))
    )
    (comp (ref "D1")
      (value "SMA6J20A")
      (footprint "eagle-import:SMA_ST")
      (fields (field (name "MANUFACTURER") "STM") (field (name "VOLTAGE") "20.0 V"))
      (libsource (lib "eagle-import") (part "SMA6JA20"))
    )
    (comp (ref "D2")
      (value "150044M155260")
      (footprint "eagle-import:150044M155260_WUERTH")
      (fields (field (name "MANUFACTURER") "Wuerth") (field (name "VOLTAGE") "5.0 V"))
      (libsource (lib "eagle-import") (part "150044M155260"))
    )
    (comp (ref "D3")
      (value "150044M155260")
      (footprint "eagle-import:150044M155260_WUERTH")
      (fields (field (name "MANUFACTURER") "Wuerth") (field (name "VOLTAGE") "5.0 V"))
      (libsource (lib "eagle-import") (part "150044M155260"))
    )
    (comp (ref "D4")
      (value "SMA6J20A")
      (footprint "eagle-import:SMA_ST")
      (fields (field (name "MANUFACTURER") "STM") (field (name "VOLTAGE") "20.0 V"))
      (libsource (lib "eagle-import") (part "SMA6JA20"))
    )
    (comp (ref "D5")
      (value "PMEG6010CEJ")
      (footprint "eagle-import:SOD323F_SC-90_NXP")
      (fields (field (name "MANUFACTURER") "Nexperia") (field (name "VOLTAGE") "60 V"))
      (libsource (lib "eagle-import") (part "PMEG6010CEJ"))
    )
    (comp (ref "D6")
      (value "n.m.")
      (footprint "eagle-import:SOD323F_SC-90_NXP")
      (fields (field (name "MANUFACTURER") "Nexperia") (field (name "VOLTAGE") "60 V"))
      (libsource (lib "eagle-import") (part "PMEG6010CEJ"))
    )
    (comp (ref "D7")
      (value "PMEG6010CEJ")
      (footprint "eagle-import:SOD323F_SC-90_NXP")
      (fields (field (name "MANUFACTURER") "Nexperia") (field (name "VOLTAGE") "60 V"))
      (libsource (lib "eagle-import") (part "PMEG6010CEJ"))
    )
    (comp (ref "D8")
      (value "PMEG6010CEJ")
      (footprint "eagle-import:SOD323F_SC-90_NXP")
      (fields (field (name "MANUFACTURER") "Nexperia") (field (name "VOLTAGE") "60 V"))
      (libsource (lib "eagle-import") (part "PMEG6010CEJ"))
    )
    (comp (ref "D9")
      (value "150044M155260")
      (footprint "eagle-import:150044M155260_WUERTH")
      (fields (field (name "MANUFACTURER") "Wuerth") (field (name "VOLTAGE") "5.0 V"))
      (libsource (lib "eagle-import") (part "150044M155260"))
    )
    (comp (ref "D10")
      (value "PMEG6010CEJ")
      (footprint "eagle-import:SOD323F_SC-90_NXP")
      (fields (field (name "MANUFACTURER") "Nexperia") (field (name "VOLTAGE") "60 V"))
      (libsource (lib "eagle-import") (part "PMEG6010CEJ"))
    )
    (comp (ref "D11")
      (value "BAS70W-05")
      (footprint "eagle-import:SOT-323_DIODES_INC")
      (fields (field (name "MANUFACTURER") "Diodes Inc") (field (name "VOLTAGE") "70.0 V"))
      (libsource (lib "eagle-import") (part "BAS70W-05"))
    )
    (comp (ref "D12")
      (value "150044M155260")
      (footprint "eagle-import:150044M155260_WUERTH")
      (fields (field (name "MANUFACTURER") "Wuerth") (field (name "VOLTAGE") "5.0 V"))
      (libsource (lib "eagle-import") (part "150044M155260"))
    )
    (comp (ref "D13")
      (value "150044M155260")
      (footprint "eagle-import:150044M155260_WUERTH")
      (fields (field (name "MANUFACTURER") "Wuerth") (field (name "VOLTAGE") "5.0 V"))
      (libsource (lib "eagle-import") (part "150044M155260"))
    )
    (comp (ref "D14")
      (value "150044M155260")
      (footprint "eagle-import:150044M155260_WUERTH")
      (fields (field (name "MANUFACTURER") "Wuerth") (field (name "VOLTAGE") "5.0 V"))
      (libsource (lib "eagle-import") (part "150044M155260"))
    )
    (comp (ref "D15")
      (value "150044M155260")
      (footprint "eagle-import:150044M155260_WUERTH")
      (fields (field (name "MANUFACTURER") "Wuerth") (field (name "VOLTAGE") "5.0 V"))
      (libsource (lib "eagle-import") (part "150044M155260"))
    )
    (comp (ref "D16")
      (value "150044M155260")
      (footprint "eagle-import:150044M155260_WUERTH")
      (fields (field (name "MANUFACTURER") "Wuerth") (field (name "VOLTAGE") "5.0 V"))
      (libsource (lib "eagle-import") (part "150044M155260"))
    )
    (comp (ref "D17")
      (value "150044M155260")
      (footprint "eagle-import:150044M155260_WUERTH")
      (fields (field (name "MANUFACTURER") "Wuerth") (field (name "VOLTAGE") "5.0 V"))
      (libsource (lib "eagle-import") (part "150044M155260"))
    )
    (comp (ref "D18")
      (value "150044M155260")
      (footprint "eagle-import:150044M155260_WUERTH")
      (fields (field (name "MANUFACTURER") "Wuerth") (field (name "VOLTAGE") "5.0 V"))
      (libsource (lib "eagle-import") (part "150044M155260"))
    )
    (comp (ref "D19")
      (value "PMEG6010CEJ")
      (footprint "eagle-import:SOD323F_SC-90_NXP")
      (fields (field (name "MANUFACTURER") "Nexperia") (field (name "VOLTAGE") "60 V"))
      (libsource (lib "eagle-import") (part "PMEG6010CEJ"))
    )
    (comp (ref "D20")
      (value "150044M155260")
      (footprint "eagle-import:150044M155260_WUERTH")
      (fields (field (name "MANUFACTURER") "Wuerth") (field (name "VOLTAGE") "5.0 V"))
      (libsource (lib "eagle-import") (part "150044M155260"))
    )
    (comp (ref "F1")
      (value "0680L9100-0")
      (footprint "eagle-import:0680L_BEL_FUSE")
      (fields (field (name "MANUFACTURER") "Bel Fuse"))
      (libsource (lib "eagle-import") (part "0680L9100-0"))
    )
    (comp (ref "F2")
      (value "SFJ-1412")
      (footprint "eagle-import:SFJ-XX12_DEXERIALS")
      (fields (field (name "MANUFACTURER") "Dexerials") (field (name "VOLTAGE") "19.6 V"))
      (libsource (lib "eagle-import") (part "SFJ-1412"))
    )
    (comp (ref "H1")
      (value "MOUNT-PAD-ROUND2.3")
      (footprint "eagle-import:2,3-PAD")
      (libsource (lib "eagle-import") (part "MOUNT-PAD-ROUND2.3"))
    )
    (comp (ref "H2")
      (value "MOUNT-PAD-ROUND2.3")
      (footprint "eagle-import:2,3-PAD")
      (libsource (lib "eagle-import") (part "MOUNT-PAD-ROUND2.3"))
    )
    (comp (ref "IC1")
      (value "BQ294703DSG")
      (footprint "eagle-import:DSG0008A_WSON_TI")
      (fields (field (name "MANUFACTURER") "TI") (field (name "VOLTAGE") "20.0 V"))
      (libsource (lib "eagle-import") (part "BQ2947DSG03"))
    )
    (comp (ref "IC4")
      (value "n.m.")
      (footprint "eagle-import:S-PDSO-G8_DGK_VSSOP_TI")
      (fields (field (name "MANUFACTURER") "TI") (field (name "VOLTAGE") "5.5 V"))
      (libsource (lib "eagle-import") (part "TMP1075DGK"))
    )
    (comp (ref "IC5")
      (value "TMP112NAIDRL")
      (footprint "eagle-import:DRL0006A_TI")
      (fields (field (name "MANUFACTURER") "TI") (field (name "VOLTAGE") "3.6 V"))
      (libsource (lib "eagle-import") (part "TMP112DRLNAI"))
    )
    (comp (ref "IC6")
      (value "824001")
      (footprint "eagle-import:SOT23-6L_WE")
      (fields (field (name "MANUFACTURER") "Wuerth") (field (name "VOLTAGE") "5.0 V"))
      (libsource (lib "eagle-import") (part "824001"))
    )
    (comp (ref "IC8")
      (value "STM32G431CBU6")
      (footprint "eagle-import:UFQFPN48_ST")
      (fields (field (name "MANUFACTURER") "STM") (field (name "VOLTAGE") "3.6 V"))
      (libsource (lib "eagle-import") (part "STM32G431CBU6"))
    )
    (comp (ref "IC10")
      (value "TPS70933DRV")
      (footprint "eagle-import:DRV0006A_TI")
      (fields (field (name "MANUFACTURER") "TI") (field (name "VOLTAGE") "30.0 V"))
      (libsource (lib "eagle-import") (part "TPS70933DRV"))
    )
    (comp (ref "IC11")
      (value "BQ24780SRUY")
      (footprint "eagle-import:RUY0028A_TI")
      (fields (field (name "MANUFACTURER") "TI") (field (name "VOLTAGE") "24.0 V"))
      (libsource (lib "eagle-import") (part "BQ24780SRUY"))
    )
    (comp (ref "IC14")
      (value "824001")
      (footprint "eagle-import:SOT23-6L_WE")
      (fields (field (name "MANUFACTURER") "Wuerth") (field (name "VOLTAGE") "5.0 V"))
      (libsource (lib "eagle-import") (part "824001"))
    )
    (comp (ref "IC26")
      (value "BQ769X2PFB")
      (footprint "eagle-import:S-PQFP-G48_PFB_TI")
      (fields (field (name "MANUFACTURER") "TI") (field (name "VOLTAGE") "55.0 / 80.0 V"))
      (libsource (lib "eagle-import") (part "BQ769X2PFB"))
    )
    (comp (ref "L2")
      (value "744771004")
      (footprint "eagle-import:WE-PD_1260_WE")
      (fields (field (name "MANUFACTURER") "Wuerth") (field (name "TOLERANCE") "±20 %"))
      (libsource (lib "eagle-import") (part "744771004"))
    )
    (comp (ref "L16")
      (value "742792410")
      (footprint "eagle-import:FERRIT_1806_WUERTH")
      (fields (field (name "MANUFACTURER") "Wuerth"))
      (libsource (lib "eagle-import") (part "742792410"))
    )
    (comp (ref "PS1")
      (value "PASSERMARKE")
      (footprint "eagle-import:PASSERMARKE")
      (libsource (lib "eagle-import") (part "PASSERMARKE"))
    )
    (comp (ref "PS2")
      (value "PASSERMARKE")
      (footprint "eagle-import:PASSERMARKE")
      (libsource (lib "eagle-import") (part "PASSERMARKE"))
    )
    (comp (ref "PS3")
      (value "PASSERMARKE")
      (footprint "eagle-import:PASSERMARKE")
      (libsource (lib "eagle-import") (part "PASSERMARKE"))
    )
    (comp (ref "PS4")
      (value "PASSERMARKE")
      (footprint "eagle-import:PASSERMARKE")
      (libsource (lib "eagle-import") (part "PASSERMARKE"))
    )
    (comp (ref "PS5")
      (value "PASSERMARKE")
      (footprint "eagle-import:PASSERMARKE")
      (libsource (lib "eagle-import") (part "PASSERMARKE"))
    )
    (comp (ref "PS6")
      (value "PASSERMARKE")
      (footprint "eagle-import:PASSERMARKE")
      (libsource (lib "eagle-import") (part "PASSERMARKE"))
    )
    (comp (ref "PTC1")
      (value "PRF15BE103RB6RC")
      (footprint "eagle-import:R0402")
      (fields
        (field (name "MANUFACTURER") "Murata")
        (field (name "TOLERANCE") "±50 %")
        (field (name "VOLTAGE") "32.0 V")
      )
      (libsource (lib "eagle-import") (part "PRF15BE103RB6RC"))
    )
    (comp (ref "Q1")
      (value "TSX-3225_24.0000MF10Z-C")
      (footprint "eagle-import:TSX-3225_SEIKO_EPSON")
      (fields (field (name "MANUFACTURER") "Epson") (field (name "TOLERANCE") "±10 PPM"))
      (libsource (lib "eagle-import") (part "TSX-3225_24.0000MF10Z-C"))
    )
    (comp (ref "Q2")
      (value "ECS-.327-12.5-12R")
      (footprint "eagle-import:ECX-12R_ECS")
      (fields (field (name "MANUFACTURER") "ECS") (field (name "TOLERANCE") "±20 ppm"))
      (libsource (lib "eagle-import") (part "ECS-.327-12.5-12R"))
    )
    (comp (ref "R1")
      (value "100k")
      (footprint "eagle-import:R0603")
      (fields
        (field (name "MANUFACTURER") "Stackpole")
        (field (name "POWER") "63 mW")
        (field (name "TOLERANCE") "±1 %")
      )
      (libsource (lib "eagle-import") (part "R-EU-R0603-100K"))
    )
    (comp (ref "R2")
      (value "10k")
      (footprint "eagle-import:R0603")
      (fields
        (field (name "MANUFACTURER") "Stackpole")
        (field (name "POWER") "63 mW")
        (field (name "TOLERANCE") "±1 %")
      )
      (libsource (lib "eagle-import") (part "R-EU-R0603-10K"))
    )
    (comp (ref "R3")
      (value "10R")
      (footprint "eagle-import:R0603")
      (fields
        (field (name "MANUFACTURER") "Stackpole")
        (field (name "POWER") "63 mW")
        (field (name "TOLERANCE") "±1 %")
      )
      (libsource (lib "eagle-import") (part "R-EU-R0603-10R"))
    )
    (comp (ref "R4")
      (value "0R")
      (footprint "eagle-import:R0603")
      (fields
        (field (name "MANUFACTURER") "Stackpole")
        (field (name "POWER") "63 mW")
        (field (name "VOLTAGE") "50.0 V")
      )
      (libsource (lib "eagle-import") (part "R-EU-R0603-0R"))
    )
    (comp (ref "R5")
      (value "0R")
      (footprint "eagle-import:R0603")
      (fields
        (field (name "MANUFACTURER") "Stackpole")
        (field (name "POWER") "63 mW")
        (field (name "VOLTAGE") "50.0 V")
      )
      (libsource (lib "eagle-import") (part "R-EU-R0603-0R"))
    )
    (comp (ref "R6")
      (value "10R")
      (footprint "eagle-import:R0603")
      (fields
        (field (name "MANUFACTURER") "Stackpole")
        (field (name "POWER") "63 mW")
        (field (name "TOLERANCE") "±1 %")
      )
      (libsource (lib "eagle-import") (part "R-EU-R0603-10R"))
    )
    (comp (ref "R7")
      (value "LVT12R0050FER")
      (footprint "eagle-import:LVT12_R003_OHMITE")
      (fields (field (name "MANUFACTURER") "ohmite") (field (name "TOLERANCE") "±1 %"))
      (libsource (lib "eagle-import") (part "LVT12R0050FER"))
    )
    (comp (ref "R8")
      (value "100k")
      (footprint "eagle-import:R0603")
      (fields
        (field (name "MANUFACTURER") "Stackpole")
        (field (name "POWER") "63 mW")
        (field (name "TOLERANCE") "±1 %")
      )
      (libsource (lib "eagle-import") (part "R-EU-R0603-100K"))
    )
    (comp (ref "R9")
      (value "1k")
      (footprint "eagle-import:R0603")
      (fields
        (field (name "MANUFACTURER") "Stackpole")
        (field (name "POWER") "63 mW")
        (field (name "TOLERANCE") "±1 %")
      )
      (libsource (lib "eagle-import") (part "R-EU-R0603-1K"))
    )
    (comp (ref "R10")
      (value "1k")
      (footprint "eagle-import:R0603")
      (fields
        (field (name "MANUFACTURER") "Stackpole")
        (field (name "POWER") "63 mW")
        (field (name "TOLERANCE") "±1 %")
      )
      (libsource (lib "eagle-import") (part "R-EU-R0603-1K"))
    )
    (comp (ref "R11")
      (value "10R")
      (footprint "eagle-import:R0603")
      (fields
        (field (name "MANUFACTURER") "Stackpole")
        (field (name "POWER") "63 mW")
        (field (name "TOLERANCE") "±1 %")
      )
      (libsource (lib "eagle-import") (part "R-EU-R0603-10R"))
    )
    (comp (ref "R12")
      (value "10k")
      (footprint "eagle-import:R0603")
      (fields
        (field (name "MANUFACTURER") "Stackpole")
        (field (name "POWER") "63 mW")
        (field (name "TOLERANCE") "±1 %")
      )
      (libsource (lib "eagle-import") (part "R-EU-R0603-10K"))
    )
    (comp (ref "R13")
      (value "10M")
      (footprint "eagle-import:R0603")
      (fields
        (field (name "MANUFACTURER") "Stackpole")
        (field (name "POWER") "63 mW")
        (field (name "TOLERANCE") "±1 %")
      )
      (libsource (lib "eagle-import") (part "R-EU-R0603-10M"))
    )
    (comp (ref "R14")
      (value "10M")
      (footprint "eagle-import:R0603")
      (fields
        (field (name "MANUFACTURER") "Stackpole")
        (field (name "POWER") "63 mW")
        (field (name "TOLERANCE") "±1 %")
      )
      (libsource (lib "eagle-import") (part "R-EU-R0603-10M"))
    )
    (comp (ref "R15")
      (value "1k")
      (footprint "eagle-import:R0603")
      (fields
        (field (name "MANUFACTURER") "Stackpole")
        (field (name "POWER") "63 mW")
        (field (name "TOLERANCE") "±1 %")
      )
      (libsource (lib "eagle-import") (part "R-EU-R0603-1K"))
    )
    (comp (ref "R16")
      (value "10R")
      (footprint "eagle-import:R0603")
      (fields
        (field (name "MANUFACTURER") "Stackpole")
        (field (name "POWER") "63 mW")
        (field (name "TOLERANCE") "±1 %")
      )
      (libsource (lib "eagle-import") (part "R-EU-R0603-10R"))
    )
    (comp (ref "R17")
      (value "1k")
      (footprint "eagle-import:R0603")
      (fields
        (field (name "MANUFACTURER") "Stackpole")
        (field (name "POWER") "63 mW")
        (field (name "TOLERANCE") "±1 %")
      )
      (libsource (lib "eagle-import") (part "R-EU-R0603-1K"))
    )
    (comp (ref "R18")
      (value "0R")
      (footprint "eagle-import:R0603")
      (fields
        (field (name "MANUFACTURER") "Stackpole")
        (field (name "POWER") "63 mW")
        (field (name "VOLTAGE") "50.0 V")
      )
      (libsource (lib "eagle-import") (part "R-EU-R0603-0R"))
    )
    (comp (ref "R19")
      (value "10R")
      (footprint "eagle-import:R0603")
      (fields
        (field (name "MANUFACTURER") "Stackpole")
        (field (name "POWER") "63 mW")
        (field (name "TOLERANCE") "±1 %")
      )
      (libsource (lib "eagle-import") (part "R-EU-R0603-10R"))
    )
    (comp (ref "R20")
      (value "1k")
      (footprint "eagle-import:R0603")
      (fields
        (field (name "MANUFACTURER") "Stackpole")
        (field (name "POWER") "63 mW")
        (field (name "TOLERANCE") "±1 %")
      )
      (libsource (lib "eagle-import") (part "R-EU-R0603-1K"))
    )
    (comp (ref "R21")
      (value "1k")
      (footprint "eagle-import:R0603")
      (fields
        (field (name "MANUFACTURER") "Stackpole")
        (field (name "POWER") "63 mW")
        (field (name "TOLERANCE") "±1 %")
      )
      (libsource (lib "eagle-import") (part "R-EU-R0603-1K"))
    )
    (comp (ref "R22")
      (value "1k")
      (footprint "eagle-import:R0603")
      (fields
        (field (name "MANUFACTURER") "Stackpole")
        (field (name "POWER") "63 mW")
        (field (name "TOLERANCE") "±1 %")
      )
      (libsource (lib "eagle-import") (part "R-EU-R0603-1K"))
    )
    (comp (ref "R23")
      (value "10R")
      (footprint "eagle-import:R0603")
      (fields
        (field (name "MANUFACTURER") "Stackpole")
        (field (name "POWER") "63 mW")
        (field (name "TOLERANCE") "±1 %")
      )
      (libsource (lib "eagle-import") (part "R-EU-R0603-10R"))
    )
    (comp (ref "R24")
      (value "510k")
      (footprint "eagle-import:R0603")
      (fields
        (field (name "MANUFACTURER") "Stackpole")
        (field (name "POWER") "63 mW")
        (field (name "TOLERANCE") "±1 %")
      )
      (libsource (lib "eagle-import") (part "R-EU-R0603-510K"))
    )
    (comp (ref "R25")
      (value "150R")
      (footprint "eagle-import:R0603")
      (fields
        (field (name "MANUFACTURER") "Uniroyal")
        (field (name "POWER") "63 mW")
        (field (name "TOLERANCE") "±1 %")
      )
      (libsource (lib "eagle-import") (part "R-EU-R0603-150R"))
    )
    (comp (ref "R26")
      (value "100k")
      (footprint "eagle-import:R0603")
      (fields
        (field (name "MANUFACTURER") "Stackpole")
        (field (name "POWER") "63 mW")
        (field (name "TOLERANCE") "±1 %")
      )
      (libsource (lib "eagle-import") (part "R-EU-R0603-100K"))
    )
    (comp (ref "R27")
      (value "0R")
      (footprint "eagle-import:R0603")
      (fields
        (field (name "MANUFACTURER") "Stackpole")
        (field (name "POWER") "63 mW")
        (field (name "VOLTAGE") "50.0 V")
      )
      (libsource (lib "eagle-import") (part "R-EU-R0603-0R"))
    )
    (comp (ref "R28")
      (value "510k")
      (footprint "eagle-import:R0603")
      (fields
        (field (name "MANUFACTURER") "Stackpole")
        (field (name "POWER") "63 mW")
        (field (name "TOLERANCE") "±1 %")
      )
      (libsource (lib "eagle-import") (part "R-EU-R0603-510K"))
    )
    (comp (ref "R29")
      (value "0R")
      (footprint "eagle-import:R0603")
      (fields
        (field (name "MANUFACTURER") "Stackpole")
        (field (name "POWER") "63 mW")
        (field (name "VOLTAGE") "50.0 V")
      )
      (libsource (lib "eagle-import") (part "R-EU-R0603-0R"))
    )
    (comp (ref "R30")
      (value "1k")
      (footprint "eagle-import:R0603")
      (fields
        (field (name "MANUFACTURER") "Stackpole")
        (field (name "POWER") "63 mW")
        (field (name "TOLERANCE") "±1 %")
      )
      (libsource (lib "eagle-import") (part "R-EU-R0603-1K"))
    )
    (comp (ref "R34")
      (value "10M")
      (footprint "eagle-import:R0603")
      (fields
        (field (name "MANUFACTURER") "Stackpole")
        (field (name "POWER") "63 mW")
        (field (name "TOLERANCE") "±1 %")
      )
      (libsource (lib "eagle-import") (part "R-EU-R0603-10M"))
    )
    (comp (ref "R35")
      (value "10R")
      (footprint "eagle-import:R0603")
      (fields
        (field (name "MANUFACTURER") "Stackpole")
        (field (name "POWER") "63 mW")
        (field (name "TOLERANCE") "±1 %")
      )
      (libsource (lib "eagle-import") (part "R-EU-R0603-10R"))
    )
    (comp (ref "R36")
      (value "10R")
      (footprint "eagle-import:R0603")
      (fields
        (field (name "MANUFACTURER") "Stackpole")
        (field (name "POWER") "63 mW")
        (field (name "TOLERANCE") "±1 %")
      )
      (libsource (lib "eagle-import") (part "R-EU-R0603-10R"))
    )
    (comp (ref "R37")
      (value "LVT12R0050FER")
      (footprint "eagle-import:LVT12_R003_OHMITE")
      (fields (field (name "MANUFACTURER") "ohmite") (field (name "TOLERANCE") "±1 %"))
      (libsource (lib "eagle-import") (part "LVT12R0050FER"))
    )
    (comp (ref "R41")
      (value "10R")
      (footprint "eagle-import:R0603")
      (fields
        (field (name "MANUFACTURER") "Stackpole")
        (field (name "POWER") "63 mW")
        (field (name "TOLERANCE") "±1 %")
      )
      (libsource (lib "eagle-import") (part "R-EU-R0603-10R"))
    )
    (comp (ref "R42")
      (value "100k")
      (footprint "eagle-import:R0603")
      (fields
        (field (name "MANUFACTURER") "Stackpole")
        (field (name "POWER") "63 mW")
        (field (name "TOLERANCE") "±1 %")
      )
      (libsource (lib "eagle-import") (part "R-EU-R0603-100K"))
    )
    (comp (ref "R43")
      (value "10M")
      (footprint "eagle-import:R0603")
      (fields
        (field (name "MANUFACTURER") "Stackpole")
        (field (name "POWER") "63 mW")
        (field (name "TOLERANCE") "±1 %")
      )
      (libsource (lib "eagle-import") (part "R-EU-R0603-10M"))
    )
    (comp (ref "R44")
      (value "10R")
      (footprint "eagle-import:R0603")
      (fields
        (field (name "MANUFACTURER") "Stackpole")
        (field (name "POWER") "63 mW")
        (field (name "TOLERANCE") "±1 %")
      )
      (libsource (lib "eagle-import") (part "R-EU-R0603-10R"))
    )
    (comp (ref "R45")
      (value "10R")
      (footprint "eagle-import:R0603")
      (fields
        (field (name "MANUFACTURER") "Stackpole")
        (field (name "POWER") "63 mW")
        (field (name "TOLERANCE") "±1 %")
      )
      (libsource (lib "eagle-import") (part "R-EU-R0603-10R"))
    )
    (comp (ref "R46")
      (value "10R")
      (footprint "eagle-import:R0603")
      (fields
        (field (name "MANUFACTURER") "Stackpole")
        (field (name "POWER") "63 mW")
        (field (name "TOLERANCE") "±1 %")
      )
      (libsource (lib "eagle-import") (part "R-EU-R0603-10R"))
    )
    (comp (ref "R47")
      (value "10R")
      (footprint "eagle-import:R0603")
      (fields
        (field (name "MANUFACTURER") "Stackpole")
        (field (name "POWER") "63 mW")
        (field (name "TOLERANCE") "±1 %")
      )
      (libsource (lib "eagle-import") (part "R-EU-R0603-10R"))
    )
    (comp (ref "R48")
      (value "10M")
      (footprint "eagle-import:R0603")
      (fields
        (field (name "MANUFACTURER") "Stackpole")
        (field (name "POWER") "63 mW")
        (field (name "TOLERANCE") "±1 %")
      )
      (libsource (lib "eagle-import") (part "R-EU-R0603-10M"))
    )
    (comp (ref "R49")
      (value "1k")
      (footprint "eagle-import:R0603")
      (fields
        (field (name "MANUFACTURER") "Stackpole")
        (field (name "POWER") "63 mW")
        (field (name "TOLERANCE") "±1 %")
      )
      (libsource (lib "eagle-import") (part "R-EU-R0603-1K"))
    )
    (comp (ref "R50")
      (value "10M")
      (footprint "eagle-import:R0603")
      (fields
        (field (name "MANUFACTURER") "Stackpole")
        (field (name "POWER") "63 mW")
        (field (name "TOLERANCE") "±1 %")
      )
      (libsource (lib "eagle-import") (part "R-EU-R0603-10M"))
    )
    (comp (ref "R51")
      (value "10R")
      (footprint "eagle-import:R0603")
      (fields
        (field (name "MANUFACTURER") "Stackpole")
        (field (name "POWER") "63 mW")
        (field (name "TOLERANCE") "±1 %")
      )
      (libsource (lib "eagle-import") (part "R-EU-R0603-10R"))
    )
    (comp (ref "R52")
      (value "10R")
      (footprint "eagle-import:R0603")
      (fields
        (field (name "MANUFACTURER") "Stackpole")
        (field (name "POWER") "63 mW")
        (field (name "TOLERANCE") "±1 %")
      )
      (libsource (lib "eagle-import") (part "R-EU-R0603-10R"))
    )
    (comp (ref "R53")
      (value "10R")
      (footprint "eagle-import:R0603")
      (fields
        (field (name "MANUFACTURER") "Stackpole")
        (field (name "POWER") "63 mW")
        (field (name "TOLERANCE") "±1 %")
      )
      (libsource (lib "eagle-import") (part "R-EU-R0603-10R"))
    )
    (comp (ref "R54")
      (value "10M")
      (footprint "eagle-import:R0603")
      (fields
        (field (name "MANUFACTURER") "Stackpole")
        (field (name "POWER") "63 mW")
        (field (name "TOLERANCE") "±1 %")
      )
      (libsource (lib "eagle-import") (part "R-EU-R0603-10M"))
    )
    (comp (ref "R55")
      (value "510k")
      (footprint "eagle-import:R0603")
      (fields
        (field (name "MANUFACTURER") "Stackpole")
        (field (name "POWER") "63 mW")
        (field (name "TOLERANCE") "±1 %")
      )
      (libsource (lib "eagle-import") (part "R-EU-R0603-510K"))
    )
    (comp (ref "R56")
      (value "100k")
      (footprint "eagle-import:R0603")
      (fields
        (field (name "MANUFACTURER") "Stackpole")
        (field (name "POWER") "63 mW")
        (field (name "TOLERANCE") "±1 %")
      )
      (libsource (lib "eagle-import") (part "R-EU-R0603-100K"))
    )
    (comp (ref "R57")
      (value "10R")
      (footprint "eagle-import:R0603")
      (fields
        (field (name "MANUFACTURER") "Stackpole")
        (field (name "POWER") "63 mW")
        (field (name "TOLERANCE") "±1 %")
      )
      (libsource (lib "eagle-import") (part "R-EU-R0603-10R"))
    )
    (comp (ref "R58")
      (value "10R")
      (footprint "eagle-import:R0603")
      (fields
        (field (name "MANUFACTURER") "Stackpole")
        (field (name "POWER") "63 mW")
        (field (name "TOLERANCE") "±1 %")
      )
      (libsource (lib "eagle-import") (part "R-EU-R0603-10R"))
    )
    (comp (ref "R59")
      (value "0R")
      (footprint "eagle-import:R0603")
      (fields
        (field (name "MANUFACTURER") "Stackpole")
        (field (name "POWER") "63 mW")
        (field (name "VOLTAGE") "50.0 V")
      )
      (libsource (lib "eagle-import") (part "R-EU-R0603-0R"))
    )
    (comp (ref "R60")
      (value "10R")
      (footprint "eagle-import:R0603")
      (fields
        (field (name "MANUFACTURER") "Stackpole")
        (field (name "POWER") "63 mW")
        (field (name "TOLERANCE") "±1 %")
      )
      (libsource (lib "eagle-import") (part "R-EU-R0603-10R"))
    )
    (comp (ref "R61")
      (value "10R")
      (footprint "eagle-import:R0603")
      (fields
        (field (name "MANUFACTURER") "Stackpole")
        (field (name "POWER") "63 mW")
        (field (name "TOLERANCE") "±1 %")
      )
      (libsource (lib "eagle-import") (part "R-EU-R0603-10R"))
    )
    (comp (ref "R62")
      (value "10R")
      (footprint "eagle-import:R0603")
      (fields
        (field (name "MANUFACTURER") "Stackpole")
        (field (name "POWER") "63 mW")
        (field (name "TOLERANCE") "±1 %")
      )
      (libsource (lib "eagle-import") (part "R-EU-R0603-10R"))
    )
    (comp (ref "R63")
      (value "330R")
      (footprint "eagle-import:R0603")
      (fields
        (field (name "MANUFACTURER") "Stackpole")
        (field (name "POWER") "63 mW")
        (field (name "TOLERANCE") "±1 %")
      )
      (libsource (lib "eagle-import") (part "R-EU-R0603-330R"))
    )
    (comp (ref "R64")
      (value "150R")
      (footprint "eagle-import:R0603")
      (fields
        (field (name "MANUFACTURER") "Uniroyal")
        (field (name "POWER") "63 mW")
        (field (name "TOLERANCE") "±1 %")
      )
      (libsource (lib "eagle-import") (part "R-EU-R0603-150R"))
    )
    (comp (ref "R65")
      (value "150R")
      (footprint "eagle-import:R0603")
      (fields
        (field (name "MANUFACTURER") "Uniroyal")
        (field (name "POWER") "63 mW")
        (field (name "TOLERANCE") "±1 %")
      )
      (libsource (lib "eagle-import") (part "R-EU-R0603-150R"))
    )
    (comp (ref "R66")
      (value "330R")
      (footprint "eagle-import:R0603")
      (fields
        (field (name "MANUFACTURER") "Stackpole")
        (field (name "POWER") "63 mW")
        (field (name "TOLERANCE") "±1 %")
      )
      (libsource (lib "eagle-import") (part "R-EU-R0603-330R"))
    )
    (comp (ref "R67")
      (value "10R")
      (footprint "eagle-import:R0603")
      (fields
        (field (name "MANUFACTURER") "Stackpole")
        (field (name "POWER") "63 mW")
        (field (name "TOLERANCE") "±1 %")
      )
      (libsource (lib "eagle-import") (part "R-EU-R0603-10R"))
    )
    (comp (ref "R68")
      (value "10R")
      (footprint "eagle-import:R0603")
      (fields
        (field (name "MANUFACTURER") "Stackpole")
        (field (name "POWER") "63 mW")
        (field (name "TOLERANCE") "±1 %")
      )
      (libsource (lib "eagle-import") (part "R-EU-R0603-10R"))
    )
    (comp (ref "R69")
      (value "10R")
      (footprint "eagle-import:R0603")
      (fields
        (field (name "MANUFACTURER") "Stackpole")
        (field (name "POWER") "63 mW")
        (field (name "TOLERANCE") "±1 %")
      )
      (libsource (lib "eagle-import") (part "R-EU-R0603-10R"))
    )
    (comp (ref "R70")
      (value "150R")
      (footprint "eagle-import:R0603")
      (fields
        (field (name "MANUFACTURER") "Uniroyal")
        (field (name "POWER") "63 mW")
        (field (name "TOLERANCE") "±1 %")
      )
      (libsource (lib "eagle-import") (part "R-EU-R0603-150R"))
    )
    (comp (ref "R71")
      (value "150R")
      (footprint "eagle-import:R0603")
      (fields
        (field (name "MANUFACTURER") "Uniroyal")
        (field (name "POWER") "63 mW")
        (field (name "TOLERANCE") "±1 %")
      )
      (libsource (lib "eagle-import") (part "R-EU-R0603-150R"))
    )
    (comp (ref "R72")
      (value "330R")
      (footprint "eagle-import:R0603")
      (fields
        (field (name "MANUFACTURER") "Stackpole")
        (field (name "POWER") "63 mW")
        (field (name "TOLERANCE") "±1 %")
      )
      (libsource (lib "eagle-import") (part "R-EU-R0603-330R"))
    )
    (comp (ref "R73")
      (value "150R")
      (footprint "eagle-import:R0603")
      (fields
        (field (name "MANUFACTURER") "Uniroyal")
        (field (name "POWER") "63 mW")
        (field (name "TOLERANCE") "±1 %")
      )
      (libsource (lib "eagle-import") (part "R-EU-R0603-150R"))
    )
    (comp (ref "R74")
      (value "150R")
      (footprint "eagle-import:R0603")
      (fields
        (field (name "MANUFACTURER") "Uniroyal")
        (field (name "POWER") "63 mW")
        (field (name "TOLERANCE") "±1 %")
      )
      (libsource (lib "eagle-import") (part "R-EU-R0603-150R"))
    )
    (comp (ref "R75")
      (value "330R")
      (footprint "eagle-import:R0603")
      (fields
        (field (name "MANUFACTURER") "Stackpole")
        (field (name "POWER") "63 mW")
        (field (name "TOLERANCE") "±1 %")
      )
      (libsource (lib "eagle-import") (part "R-EU-R0603-330R"))
    )
    (comp (ref "R76")
      (value "150R")
      (footprint "eagle-import:R0603")
      (fields
        (field (name "MANUFACTURER") "Uniroyal")
        (field (name "POWER") "63 mW")
        (field (name "TOLERANCE") "±1 %")
      )
      (libsource (lib "eagle-import") (part "R-EU-R0603-150R"))
    )
    (comp (ref "R77")
      (value "150R")
      (footprint "eagle-import:R0603")
      (fields
        (field (name "MANUFACTURER") "Uniroyal")
        (field (name "POWER") "63 mW")
        (field (name "TOLERANCE") "±1 %")
      )
      (libsource (lib "eagle-import") (part "R-EU-R0603-150R"))
    )
    (comp (ref "R78")
      (value "330R")
      (footprint "eagle-import:R0603")
      (fields
        (field (name "MANUFACTURER") "Stackpole")
        (field (name "POWER") "63 mW")
        (field (name "TOLERANCE") "±1 %")
      )
      (libsource (lib "eagle-import") (part "R-EU-R0603-330R"))
    )
    (comp (ref "R79")
      (value "10M")
      (footprint "eagle-import:R0603")
      (fields
        (field (name "MANUFACTURER") "Stackpole")
        (field (name "POWER") "63 mW")
        (field (name "TOLERANCE") "±1 %")
      )
      (libsource (lib "eagle-import") (part "R-EU-R0603-10M"))
    )
    (comp (ref "R80")
      (value "10k")
      (footprint "eagle-import:R0603")
      (fields
        (field (name "MANUFACTURER") "Stackpole")
        (field (name "POWER") "63 mW")
        (field (name "TOLERANCE") "±1 %")
      )
      (libsource (lib "eagle-import") (part "R-EU-R0603-10K"))
    )
    (comp (ref "R81")
      (value "10k")
      (footprint "eagle-import:R0603")
      (fields
        (field (name "MANUFACTURER") "Stackpole")
        (field (name "POWER") "63 mW")
        (field (name "TOLERANCE") "±1 %")
      )
      (libsource (lib "eagle-import") (part "R-EU-R0603-10K"))
    )
    (comp (ref "R82")
      (value "0R")
      (footprint "eagle-import:R0603")
      (fields
        (field (name "MANUFACTURER") "Stackpole")
        (field (name "POWER") "63 mW")
        (field (name "VOLTAGE") "50.0 V")
      )
      (libsource (lib "eagle-import") (part "R-EU-R0603-0R"))
    )
    (comp (ref "R83")
      (value "0R")
      (footprint "eagle-import:R0603")
      (fields
        (field (name "MANUFACTURER") "Stackpole")
        (field (name "POWER") "63 mW")
        (field (name "VOLTAGE") "50.0 V")
      )
      (libsource (lib "eagle-import") (part "R-EU-R0603-0R"))
    )
    (comp (ref "R84")
      (value "10k")
      (footprint "eagle-import:R0603")
      (fields
        (field (name "MANUFACTURER") "Stackpole")
        (field (name "POWER") "63 mW")
        (field (name "TOLERANCE") "±1 %")
      )
      (libsource (lib "eagle-import") (part "R-EU-R0603-10K"))
    )
    (comp (ref "R85")
      (value "10k")
      (footprint "eagle-import:R0603")
      (fields
        (field (name "MANUFACTURER") "Stackpole")
        (field (name "POWER") "63 mW")
        (field (name "TOLERANCE") "±1 %")
      )
      (libsource (lib "eagle-import") (part "R-EU-R0603-10K"))
    )
    (comp (ref "R86")
      (value "10M")
      (footprint "eagle-import:R0603")
      (fields
        (field (name "MANUFACTURER") "Stackpole")
        (field (name "POWER") "63 mW")
        (field (name "TOLERANCE") "±1 %")
      )
      (libsource (lib "eagle-import") (part "R-EU-R0603-10M"))
    )
    (comp (ref "R87")
      (value "10M")
      (footprint "eagle-import:R0603")
      (fields
        (field (name "MANUFACTURER") "Stackpole")
        (field (name "POWER") "63 mW")
        (field (name "TOLERANCE") "±1 %")
      )
      (libsource (lib "eagle-import") (part "R-EU-R0603-10M"))
    )
    (comp (ref "R88")
      (value "10M")
      (footprint "eagle-import:R0603")
      (fields
        (field (name "MANUFACTURER") "Stackpole")
        (field (name "POWER") "63 mW")
        (field (name "TOLERANCE") "±1 %")
      )
      (libsource (lib "eagle-import") (part "R-EU-R0603-10M"))
    )
    (comp (ref "R89")
      (value "10M")
      (footprint "eagle-import:R0603")
      (fields
        (field (name "MANUFACTURER") "Stackpole")
        (field (name "POWER") "63 mW")
        (field (name "TOLERANCE") "±1 %")
      )
      (libsource (lib "eagle-import") (part "R-EU-R0603-10M"))
    )
    (comp (ref "R90")
      (value "0R")
      (footprint "eagle-import:R0603")
      (fields
        (field (name "MANUFACTURER") "Stackpole")
        (field (name "POWER") "63 mW")
        (field (name "VOLTAGE") "50.0 V")
      )
      (libsource (lib "eagle-import") (part "R-EU-R0603-0R"))
    )
    (comp (ref "R92")
      (value "10R")
      (footprint "eagle-import:R0603")
      (fields
        (field (name "MANUFACTURER") "Stackpole")
        (field (name "POWER") "63 mW")
        (field (name "TOLERANCE") "±1 %")
      )
      (libsource (lib "eagle-import") (part "R-EU-R0603-10R"))
    )
    (comp (ref "R93")
      (value "10k")
      (footprint "eagle-import:R0603")
      (fields
        (field (name "MANUFACTURER") "Stackpole")
        (field (name "POWER") "63 mW")
        (field (name "TOLERANCE") "±1 %")
      )
      (libsource (lib "eagle-import") (part "R-EU-R0603-10K"))
    )
    (comp (ref "R94")
      (value "10k")
      (footprint "eagle-import:R0603")
      (fields
        (field (name "MANUFACTURER") "Stackpole")
        (field (name "POWER") "63 mW")
        (field (name "TOLERANCE") "±1 %")
      )
      (libsource (lib "eagle-import") (part "R-EU-R0603-10K"))
    )
    (comp (ref "R95")
      (value "10R")
      (footprint "eagle-import:R0603")
      (fields
        (field (name "MANUFACTURER") "Stackpole")
        (field (name "POWER") "63 mW")
        (field (name "TOLERANCE") "±1 %")
      )
      (libsource (lib "eagle-import") (part "R-EU-R0603-10R"))
    )
    (comp (ref "R96")
      (value "10k")
      (footprint "eagle-import:R0603")
      (fields
        (field (name "MANUFACTURER") "Stackpole")
        (field (name "POWER") "63 mW")
        (field (name "TOLERANCE") "±1 %")
      )
      (libsource (lib "eagle-import") (part "R-EU-R0603-10K"))
    )
    (comp (ref "R97")
      (value "10k")
      (footprint "eagle-import:R0603")
      (fields
        (field (name "MANUFACTURER") "Stackpole")
        (field (name "POWER") "63 mW")
        (field (name "TOLERANCE") "±1 %")
      )
      (libsource (lib "eagle-import") (part "R-EU-R0603-10K"))
    )
    (comp (ref "R98")
      (value "10k")
      (footprint "eagle-import:R0603")
      (fields
        (field (name "MANUFACTURER") "Stackpole")
        (field (name "POWER") "63 mW")
        (field (name "TOLERANCE") "±1 %")
      )
      (libsource (lib "eagle-import") (part "R-EU-R0603-10K"))
    )
    (comp (ref "R99")
      (value "100k")
      (footprint "eagle-import:R0603")
      (fields
        (field (name "MANUFACTURER") "Stackpole")
        (field (name "POWER") "63 mW")
        (field (name "TOLERANCE") "±1 %")
      )
      (libsource (lib "eagle-import") (part "R-EU-R0603-100K"))
    )
    (comp (ref "R100")
      (value "150R")
      (footprint "eagle-import:R0603")
      (fields
        (field (name "MANUFACTURER") "Uniroyal")
        (field (name "POWER") "63 mW")
        (field (name "TOLERANCE") "±1 %")
      )
      (libsource (lib "eagle-import") (part "R-EU-R0603-150R"))
    )
    (comp (ref "R101")
      (value "150R")
      (footprint "eagle-import:R0603")
      (fields
        (field (name "MANUFACTURER") "Uniroyal")
        (field (name "POWER") "63 mW")
        (field (name "TOLERANCE") "±1 %")
      )
      (libsource (lib "eagle-import") (part "R-EU-R0603-150R"))
    )
    (comp (ref "R102")
      (value "330R")
      (footprint "eagle-import:R0603")
      (fields
        (field (name "MANUFACTURER") "Stackpole")
        (field (name "POWER") "63 mW")
        (field (name "TOLERANCE") "±1 %")
      )
      (libsource (lib "eagle-import") (part "R-EU-R0603-330R"))
    )
    (comp (ref "R103")
      (value "150R")
      (footprint "eagle-import:R0603")
      (fields
        (field (name "MANUFACTURER") "Uniroyal")
        (field (name "POWER") "63 mW")
        (field (name "TOLERANCE") "±1 %")
      )
      (libsource (lib "eagle-import") (part "R-EU-R0603-150R"))
    )
    (comp (ref "R104")
      (value "150R")
      (footprint "eagle-import:R0603")
      (fields
        (field (name "MANUFACTURER") "Uniroyal")
        (field (name "POWER") "63 mW")
        (field (name "TOLERANCE") "±1 %")
      )
      (libsource (lib "eagle-import") (part "R-EU-R0603-150R"))
    )
    (comp (ref "R105")
      (value "330R")
      (footprint "eagle-import:R0603")
      (fields
        (field (name "MANUFACTURER") "Stackpole")
        (field (name "POWER") "63 mW")
        (field (name "TOLERANCE") "±1 %")
      )
      (libsource (lib "eagle-import") (part "R-EU-R0603-330R"))
    )
    (comp (ref "R106")
      (value "150R")
      (footprint "eagle-import:R0603")
      (fields
        (field (name "MANUFACTURER") "Uniroyal")
        (field (name "POWER") "63 mW")
        (field (name "TOLERANCE") "±1 %")
      )
      (libsource (lib "eagle-import") (part "R-EU-R0603-150R"))
    )
    (comp (ref "R107")
      (value "150R")
      (footprint "eagle-import:R0603")
      (fields
        (field (name "MANUFACTURER") "Uniroyal")
        (field (name "POWER") "63 mW")
        (field (name "TOLERANCE") "±1 %")
      )
      (libsource (lib "eagle-import") (part "R-EU-R0603-150R"))
    )
    (comp (ref "R108")
      (value "330R")
      (footprint "eagle-import:R0603")
      (fields
        (field (name "MANUFACTURER") "Stackpole")
        (field (name "POWER") "63 mW")
        (field (name "TOLERANCE") "±1 %")
      )
      (libsource (lib "eagle-import") (part "R-EU-R0603-330R"))
    )
    (comp (ref "R109")
      (value "150R")
      (footprint "eagle-import:R0603")
      (fields
        (field (name "MANUFACTURER") "Uniroyal")
        (field (name "POWER") "63 mW")
        (field (name "TOLERANCE") "±1 %")
      )
      (libsource (lib "eagle-import") (part "R-EU-R0603-150R"))
    )
    (comp (ref "R110")
      (value "150R")
      (footprint "eagle-import:R0603")
      (fields
        (field (name "MANUFACTURER") "Uniroyal")
        (field (name "POWER") "63 mW")
        (field (name "TOLERANCE") "±1 %")
      )
      (libsource (lib "eagle-import") (part "R-EU-R0603-150R"))
    )
    (comp (ref "R111")
      (value "330R")
      (footprint "eagle-import:R0603")
      (fields
        (field (name "MANUFACTURER") "Stackpole")
        (field (name "POWER") "63 mW")
        (field (name "TOLERANCE") "±1 %")
      )
      (libsource (lib "eagle-import") (part "R-EU-R0603-330R"))
    )
    (comp (ref "R112")
      (value "150R")
      (footprint "eagle-import:R0603")
      (fields
        (field (name "MANUFACTURER") "Uniroyal")
        (field (name "POWER") "63 mW")
        (field (name "TOLERANCE") "±1 %")
      )
      (libsource (lib "eagle-import") (part "R-EU-R0603-150R"))
    )
    (comp (ref "R113")
      (value "150R")
      (footprint "eagle-import:R0603")
      (fields
        (field (name "MANUFACTURER") "Uniroyal")
        (field (name "POWER") "63 mW")
        (field (name "TOLERANCE") "±1 %")
      )
      (libsource (lib "eagle-import") (part "R-EU-R0603-150R"))
    )
    (comp (ref "R114")
      (value "330R")
      (footprint "eagle-import:R0603")
      (fields
        (field (name "MANUFACTURER") "Stackpole")
        (field (name "POWER") "63 mW")
        (field (name "TOLERANCE") "±1 %")
      )
      (libsource (lib "eagle-import") (part "R-EU-R0603-330R"))
    )
    (comp (ref "R115")
      (value "150R")
      (footprint "eagle-import:R0603")
      (fields
        (field (name "MANUFACTURER") "Uniroyal")
        (field (name "POWER") "63 mW")
        (field (name "TOLERANCE") "±1 %")
      )
      (libsource (lib "eagle-import") (part "R-EU-R0603-150R"))
    )
    (comp (ref "R116")
      (value "150R")
      (footprint "eagle-import:R0603")
      (fields
        (field (name "MANUFACTURER") "Uniroyal")
        (field (name "POWER") "63 mW")
        (field (name "TOLERANCE") "±1 %")
      )
      (libsource (lib "eagle-import") (part "R-EU-R0603-150R"))
    )
    (comp (ref "R117")
      (value "10R")
      (footprint "eagle-import:R0603")
      (fields
        (field (name "MANUFACTURER") "Stackpole")
        (field (name "POWER") "63 mW")
        (field (name "TOLERANCE") "±1 %")
      )
      (libsource (lib "eagle-import") (part "R-EU-R0603-10R"))
    )
    (comp (ref "R118")
      (value "10R")
      (footprint "eagle-import:R0603")
      (fields
        (field (name "MANUFACTURER") "Stackpole")
        (field (name "POWER") "63 mW")
        (field (name "TOLERANCE") "±1 %")
      )
      (libsource (lib "eagle-import") (part "R-EU-R0603-10R"))
    )
    (comp (ref "R121")
      (value "10R")
      (footprint "eagle-import:R0603")
      (fields
        (field (name "MANUFACTURER") "Stackpole")
        (field (name "POWER") "63 mW")
        (field (name "TOLERANCE") "±1 %")
      )
      (libsource (lib "eagle-import") (part "R-EU-R0603-10R"))
    )
    (comp (ref "R122")
      (value "10R")
      (footprint "eagle-import:R0603")
      (fields
        (field (name "MANUFACTURER") "Stackpole")
        (field (name "POWER") "63 mW")
        (field (name "TOLERANCE") "±1 %")
      )
      (libsource (lib "eagle-import") (part "R-EU-R0603-10R"))
    )
    (comp (ref "R123")
      (value "10k")
      (footprint "eagle-import:R0603")
      (fields
        (field (name "MANUFACTURER") "Stackpole")
        (field (name "POWER") "63 mW")
        (field (name "TOLERANCE") "±1 %")
      )
      (libsource (lib "eagle-import") (part "R-EU-R0603-10K"))
    )
    (comp (ref "R124")
      (value "10M")
      (footprint "eagle-import:R0603")
      (fields
        (field (name "MANUFACTURER") "Stackpole")
        (field (name "POWER") "63 mW")
        (field (name "TOLERANCE") "±1 %")
      )
      (libsource (lib "eagle-import") (part "R-EU-R0603-10M"))
    )
    (comp (ref "R125")
      (value "10M")
      (footprint "eagle-import:R0603")
      (fields
        (field (name "MANUFACTURER") "Stackpole")
        (field (name "POWER") "63 mW")
        (field (name "TOLERANCE") "±1 %")
      )
      (libsource (lib "eagle-import") (part "R-EU-R0603-10M"))
    )
    (comp (ref "R126")
      (value "10R")
      (footprint "eagle-import:R0603")
      (fields
        (field (name "MANUFACTURER") "Stackpole")
        (field (name "POWER") "63 mW")
        (field (name "TOLERANCE") "±1 %")
      )
      (libsource (lib "eagle-import") (part "R-EU-R0603-10R"))
    )
    (comp (ref "R127")
      (value "10R")
      (footprint "eagle-import:R0603")
      (fields
        (field (name "MANUFACTURER") "Stackpole")
        (field (name "POWER") "63 mW")
        (field (name "TOLERANCE") "±1 %")
      )
      (libsource (lib "eagle-import") (part "R-EU-R0603-10R"))
    )
    (comp (ref "R128")
      (value "10R")
      (footprint "eagle-import:R0603")
      (fields
        (field (name "MANUFACTURER") "Stackpole")
        (field (name "POWER") "63 mW")
        (field (name "TOLERANCE") "±1 %")
      )
      (libsource (lib "eagle-import") (part "R-EU-R0603-10R"))
    )
    (comp (ref "R129")
      (value "10R")
      (footprint "eagle-import:R0603")
      (fields
        (field (name "MANUFACTURER") "Stackpole")
        (field (name "POWER") "63 mW")
        (field (name "TOLERANCE") "±1 %")
      )
      (libsource (lib "eagle-import") (part "R-EU-R0603-10R"))
    )
    (comp (ref "R130")
      (value "10R")
      (footprint "eagle-import:R0603")
      (fields
        (field (name "MANUFACTURER") "Stackpole")
        (field (name "POWER") "63 mW")
        (field (name "TOLERANCE") "±1 %")
      )
      (libsource (lib "eagle-import") (part "R-EU-R0603-10R"))
    )
    (comp (ref "R131")
      (value "10R")
      (footprint "eagle-import:R0603")
      (fields
        (field (name "MANUFACTURER") "Stackpole")
        (field (name "POWER") "63 mW")
        (field (name "TOLERANCE") "±1 %")
      )
      (libsource (lib "eagle-import") (part "R-EU-R0603-10R"))
    )
    (comp (ref "R132")
      (value "10R")
      (footprint "eagle-import:R0603")
      (fields
        (field (name "MANUFACTURER") "Stackpole")
        (field (name "POWER") "63 mW")
        (field (name "TOLERANCE") "±1 %")
      )
      (libsource (lib "eagle-import") (part "R-EU-R0603-10R"))
    )
    (comp (ref "R133")
      (value "10R")
      (footprint "eagle-import:R0603")
      (fields
        (field (name "MANUFACTURER") "Stackpole")
        (field (name "POWER") "63 mW")
        (field (name "TOLERANCE") "±1 %")
      )
      (libsource (lib "eagle-import") (part "R-EU-R0603-10R"))
    )
    (comp (ref "R134")
      (value "10R")
      (footprint "eagle-import:R0603")
      (fields
        (field (name "MANUFACTURER") "Stackpole")
        (field (name "POWER") "63 mW")
        (field (name "TOLERANCE") "±1 %")
      )
      (libsource (lib "eagle-import") (part "R-EU-R0603-10R"))
    )
    (comp (ref "R135")
      (value "10R")
      (footprint "eagle-import:R0603")
      (fields
        (field (name "MANUFACTURER") "Stackpole")
        (field (name "POWER") "63 mW")
        (field (name "TOLERANCE") "±1 %")
      )
      (libsource (lib "eagle-import") (part "R-EU-R0603-10R"))
    )
    (comp (ref "R136")
      (value "10R")
      (footprint "eagle-import:R0603")
      (fields
        (field (name "MANUFACTURER") "Stackpole")
        (field (name "POWER") "63 mW")
        (field (name "TOLERANCE") "±1 %")
      )
      (libsource (lib "eagle-import") (part "R-EU-R0603-10R"))
    )
    (comp (ref "R137")
      (value "10R")
      (footprint "eagle-import:R0603")
      (fields
        (field (name "MANUFACTURER") "Stackpole")
        (field (name "POWER") "63 mW")
        (field (name "TOLERANCE") "±1 %")
      )
      (libsource (lib "eagle-import") (part "R-EU-R0603-10R"))
    )
    (comp (ref "R138")
      (value "10R")
      (footprint "eagle-import:R0603")
      (fields
        (field (name "MANUFACTURER") "Stackpole")
        (field (name "POWER") "63 mW")
        (field (name "TOLERANCE") "±1 %")
      )
      (libsource (lib "eagle-import") (part "R-EU-R0603-10R"))
    )
    (comp (ref "R139")
      (value "10R")
      (footprint "eagle-import:R0603")
      (fields
        (field (name "MANUFACTURER") "Stackpole")
        (field (name "POWER") "63 mW")
        (field (name "TOLERANCE") "±1 %")
      )
      (libsource (lib "eagle-import") (part "R-EU-R0603-10R"))
    )
    (comp (ref "R140")
      (value "10R")
      (footprint "eagle-import:R0603")
      (fields
        (field (name "MANUFACTURER") "Stackpole")
        (field (name "POWER") "63 mW")
        (field (name "TOLERANCE") "±1 %")
      )
      (libsource (lib "eagle-import") (part "R-EU-R0603-10R"))
    )
    (comp (ref "R141")
      (value "100k")
      (footprint "eagle-import:R0603")
      (fields
        (field (name "MANUFACTURER") "Stackpole")
        (field (name "POWER") "63 mW")
        (field (name "TOLERANCE") "±1 %")
      )
      (libsource (lib "eagle-import") (part "R-EU-R0603-100K"))
    )
    (comp (ref "R142")
      (value "10R")
      (footprint "eagle-import:R0603")
      (fields
        (field (name "MANUFACTURER") "Stackpole")
        (field (name "POWER") "63 mW")
        (field (name "TOLERANCE") "±1 %")
      )
      (libsource (lib "eagle-import") (part "R-EU-R0603-10R"))
    )
    (comp (ref "R143")
      (value "10R")
      (footprint "eagle-import:R0603")
      (fields
        (field (name "MANUFACTURER") "Stackpole")
        (field (name "POWER") "63 mW")
        (field (name "TOLERANCE") "±1 %")
      )
      (libsource (lib "eagle-import") (part "R-EU-R0603-10R"))
    )
    (comp (ref "R144")
      (value "10R")
      (footprint "eagle-import:R0603")
      (fields
        (field (name "MANUFACTURER") "Stackpole")
        (field (name "POWER") "63 mW")
        (field (name "TOLERANCE") "±1 %")
      )
      (libsource (lib "eagle-import") (part "R-EU-R0603-10R"))
    )
    (comp (ref "R145")
      (value "100k")
      (footprint "eagle-import:R0603")
      (fields
        (field (name "MANUFACTURER") "Stackpole")
        (field (name "POWER") "63 mW")
        (field (name "TOLERANCE") "±1 %")
      )
      (libsource (lib "eagle-import") (part "R-EU-R0603-100K"))
    )
    (comp (ref "R146")
      (value "100k")
      (footprint "eagle-import:R0603")
      (fields
        (field (name "MANUFACTURER") "Stackpole")
        (field (name "POWER") "63 mW")
        (field (name "TOLERANCE") "±1 %")
      )
      (libsource (lib "eagle-import") (part "R-EU-R0603-100K"))
    )
    (comp (ref "R147")
      (value "0R")
      (footprint "eagle-import:R0603")
      (fields
        (field (name "MANUFACTURER") "Stackpole")
        (field (name "POWER") "63 mW")
        (field (name "VOLTAGE") "50.0 V")
      )
      (libsource (lib "eagle-import") (part "R-EU-R0603-0R"))
    )
    (comp (ref "R148")
      (value "0R")
      (footprint "eagle-import:R0603")
      (fields
        (field (name "MANUFACTURER") "Stackpole")
        (field (name "POWER") "63 mW")
        (field (name "VOLTAGE") "50.0 V")
      )
      (libsource (lib "eagle-import") (part "R-EU-R0603-0R"))
    )
    (comp (ref "R149")
      (value "100k")
      (footprint "eagle-import:R0603")
      (fields
        (field (name "MANUFACTURER") "Stackpole")
        (field (name "POWER") "63 mW")
        (field (name "TOLERANCE") "±1 %")
      )
      (libsource (lib "eagle-import") (part "R-EU-R0603-100K"))
    )
    (comp (ref "R176")
      (value "10R")
      (footprint "eagle-import:R0603")
      (fields
        (field (name "MANUFACTURER") "Stackpole")
        (field (name "POWER") "63 mW")
        (field (name "TOLERANCE") "±1 %")
      )
      (libsource (lib "eagle-import") (part "R-EU-R0603-10R"))
    )
    (comp (ref "R177")
      (value "10R")
      (footprint "eagle-import:R0603")
      (fields
        (field (name "MANUFACTURER") "Stackpole")
        (field (name "POWER") "63 mW")
        (field (name "TOLERANCE") "±1 %")
      )
      (libsource (lib "eagle-import") (part "R-EU-R0603-10R"))
    )
    (comp (ref "R189")
      (value "150R")
      (footprint "eagle-import:R0603")
      (fields
        (field (name "MANUFACTURER") "Uniroyal")
        (field (name "POWER") "63 mW")
        (field (name "TOLERANCE") "±1 %")
      )
      (libsource (lib "eagle-import") (part "R-EU-R0603-150R"))
    )
    (comp (ref "R190")
      (value "150R")
      (footprint "eagle-import:R0603")
      (fields
        (field (name "MANUFACTURER") "Uniroyal")
        (field (name "POWER") "63 mW")
        (field (name "TOLERANCE") "±1 %")
      )
      (libsource (lib "eagle-import") (part "R-EU-R0603-150R"))
    )
    (comp (ref "R191")
      (value "150R")
      (footprint "eagle-import:R0603")
      (fields
        (field (name "MANUFACTURER") "Uniroyal")
        (field (name "POWER") "63 mW")
        (field (name "TOLERANCE") "±1 %")
      )
      (libsource (lib "eagle-import") (part "R-EU-R0603-150R"))
    )
    (comp (ref "R192")
      (value "LVT12R0050FER")
      (footprint "eagle-import:LVT12_R003_OHMITE")
      (fields (field (name "MANUFACTURER") "ohmite") (field (name "TOLERANCE") "±1 %"))
      (libsource (lib "eagle-import") (part "LVT12R0050FER"))
    )
    (comp (ref "R217")
      (value "10k")
      (footprint "eagle-import:R0603")
      (fields
        (field (name "MANUFACTURER") "Stackpole")
        (field (name "POWER") "63 mW")
        (field (name "TOLERANCE") "±1 %")
      )
      (libsource (lib "eagle-import") (part "R-EU-R0603-10K"))
    )
    (comp (ref "R218")
      (value "10k")
      (footprint "eagle-import:R0603")
      (fields
        (field (name "MANUFACTURER") "Stackpole")
        (field (name "POWER") "63 mW")
        (field (name "TOLERANCE") "±1 %")
      )
      (libsource (lib "eagle-import") (part "R-EU-R0603-10K"))
    )
    (comp (ref "R227")
      (value "10k")
      (footprint "eagle-import:R0603")
      (fields
        (field (name "MANUFACTURER") "Stackpole")
        (field (name "POWER") "63 mW")
        (field (name "TOLERANCE") "±1 %")
      )
      (libsource (lib "eagle-import") (part "R-EU-R0603-10K"))
    )
    (comp (ref "R228")
      (value "330R")
      (footprint "eagle-import:R0603")
      (fields
        (field (name "MANUFACTURER") "Stackpole")
        (field (name "POWER") "63 mW")
        (field (name "TOLERANCE") "±1 %")
      )
      (libsource (lib "eagle-import") (part "R-EU-R0603-330R"))
    )
    (comp (ref "R229")
      (value "10R")
      (footprint "eagle-import:R0603")
      (fields
        (field (name "MANUFACTURER") "Stackpole")
        (field (name "POWER") "63 mW")
        (field (name "TOLERANCE") "±1 %")
      )
      (libsource (lib "eagle-import") (part "R-EU-R0603-10R"))
    )
    (comp (ref "R232")
      (value "10R")
      (footprint "eagle-import:R0603")
      (fields
        (field (name "MANUFACTURER") "Stackpole")
        (field (name "POWER") "63 mW")
        (field (name "TOLERANCE") "±1 %")
      )
      (libsource (lib "eagle-import") (part "R-EU-R0603-10R"))
    )
    (comp (ref "R296")
      (value "330R")
      (footprint "eagle-import:R0603")
      (fields
        (field (name "MANUFACTURER") "Stackpole")
        (field (name "POWER") "63 mW")
        (field (name "TOLERANCE") "±1 %")
      )
      (libsource (lib "eagle-import") (part "R-EU-R0603-330R"))
    )
    (comp (ref "R322")
      (value "10R")
      (footprint "eagle-import:R0603")
      (fields
        (field (name "MANUFACTURER") "Stackpole")
        (field (name "POWER") "63 mW")
        (field (name "TOLERANCE") "±1 %")
      )
      (libsource (lib "eagle-import") (part "R-EU-R0603-10R"))
    )
    (comp (ref "R337")
      (value "10R")
      (footprint "eagle-import:R0603")
      (fields
        (field (name "MANUFACTURER") "Stackpole")
        (field (name "POWER") "63 mW")
        (field (name "TOLERANCE") "±1 %")
      )
      (libsource (lib "eagle-import") (part "R-EU-R0603-10R"))
    )
    (comp (ref "S1")
      (value "430451025836")
      (footprint "eagle-import:430451025836_WUERTH")
      (fields (field (name "MANUFACTURER") "Wuerth") (field (name "VOLTAGE") "12.0 V"))
      (libsource (lib "eagle-import") (part "430451025836"))
    )
    (comp (ref "SPACER1")
      (value "n.m.")
      (footprint "eagle-import:702916000_WUERTH")
      (fields (field (name "MANUFACTURER") "Wuerth"))
      (libsource (lib "eagle-import") (part "702916000"))
    )
    (comp (ref "SPACER2")
      (value "n.m.")
      (footprint "eagle-import:702916000_WUERTH")
      (fields (field (name "MANUFACTURER") "Wuerth"))
      (libsource (lib "eagle-import") (part "702916000"))
    )
    (comp (ref "T1")
      (value "SISS06DN")
      (footprint "eagle-import:POWERPAK_1212-8S_VISHAY")
      (fields (field (name "MANUFACTURER") "Vishay"))
      (libsource (lib "eagle-import") (part "SISS06DN"))
    )
    (comp (ref "T2")
      (value "DMG1012UW-7")
      (footprint "eagle-import:SOT-323_DIODES_INC")
      (fields (field (name "MANUFACTURER") "Diodes Inc"))
      (libsource (lib "eagle-import") (part "DMG1012UW-7"))
    )
    (comp (ref "T3")
      (value "SISS06DN")
      (footprint "eagle-import:POWERPAK_1212-8S_VISHAY")
      (fields (field (name "MANUFACTURER") "Vishay"))
      (libsource (lib "eagle-import") (part "SISS06DN"))
    )
    (comp (ref "T4")
      (value "PMV30ENEA")
      (footprint "eagle-import:SOT-23_NXP")
      (fields (field (name "MANUFACTURER") "Nexperia"))
      (libsource (lib "eagle-import") (part "PMV30ENEA"))
    )
    (comp (ref "T5")
      (value "PMV30ENEA")
      (footprint "eagle-import:SOT-23_NXP")
      (fields (field (name "MANUFACTURER") "Nexperia"))
      (libsource (lib "eagle-import") (part "PMV30ENEA"))
    )
    (comp (ref "T6")
      (value "PMV30ENEA")
      (footprint "eagle-import:SOT-23_NXP")
      (fields (field (name "MANUFACTURER") "Nexperia"))
      (libsource (lib "eagle-import") (part "PMV30ENEA"))
    )
    (comp (ref "T7")
      (value "DMG1012UW-7")
      (footprint "eagle-import:SOT-323_DIODES_INC")
      (fields (field (name "MANUFACTURER") "Diodes Inc"))
      (libsource (lib "eagle-import") (part "DMG1012UW-7"))
    )
    (comp (ref "T8")
      (value "CSD17577Q3A")
      (footprint "eagle-import:Q3A_TI")
      (fields (field (name "MANUFACTURER") "TI"))
      (libsource (lib "eagle-import") (part "CSD17577Q3A"))
    )
    (comp (ref "T9")
      (value "CSD17308Q3")
      (footprint "eagle-import:Q3_TI")
      (fields (field (name "MANUFACTURER") "TI"))
      (libsource (lib "eagle-import") (part "CSD17308Q3"))
    )
    (comp (ref "T11")
      (value "PMV30ENEA")
      (footprint "eagle-import:SOT-23_NXP")
      (fields (field (name "MANUFACTURER") "Nexperia"))
      (libsource (lib "eagle-import") (part "PMV30ENEA"))
    )
    (comp (ref "T12")
      (value "PMV30ENEA")
      (footprint "eagle-import:SOT-23_NXP")
      (fields (field (name "MANUFACTURER") "Nexperia"))
      (libsource (lib "eagle-import") (part "PMV30ENEA"))
    )
    (comp (ref "T13")
      (value "SISS06DN")
      (footprint "eagle-import:POWERPAK_1212-8S_VISHAY")
      (fields (field (name "MANUFACTURER") "Vishay"))
      (libsource (lib "eagle-import") (part "SISS06DN"))
    )
    (comp (ref "T14")
      (value "SISS06DN")
      (footprint "eagle-import:POWERPAK_1212-8S_VISHAY")
      (fields (field (name "MANUFACTURER") "Vishay"))
      (libsource (lib "eagle-import") (part "SISS06DN"))
    )
    (comp (ref "T15")
      (value "PMV30ENEA")
      (footprint "eagle-import:SOT-23_NXP")
      (fields (field (name "MANUFACTURER") "Nexperia"))
      (libsource (lib "eagle-import") (part "PMV30ENEA"))
    )
    (comp (ref "T16")
      (value "PMV30ENEA")
      (footprint "eagle-import:SOT-23_NXP")
      (fields (field (name "MANUFACTURER") "Nexperia"))
      (libsource (lib "eagle-import") (part "PMV30ENEA"))
    )
    (comp (ref "T17")
      (value "PMV30ENEA")
      (footprint "eagle-import:SOT-23_NXP")
      (fields (field (name "MANUFACTURER") "Nexperia"))
      (libsource (lib "eagle-import") (part "PMV30ENEA"))
    )
    (comp (ref "TP1")
      (value "TESTPOINT_VIA_ROUND_0.8MM")
      (footprint "eagle-import:TESTVIA_ROUND_0.8MM")
      (libsource (lib "eagle-import") (part "TESTPOINT_VIA_ROUND_0.8MM"))
    )
    (comp (ref "TP2")
      (value "TESTPOINT_VIA_ROUND_0.8MM")
      (footprint "eagle-import:TESTVIA_ROUND_0.8MM")
      (libsource (lib "eagle-import") (part "TESTPOINT_VIA_ROUND_0.8MM"))
    )
    (comp (ref "TP3")
      (value "TESTPOINT_VIA_ROUND_0.8MM")
      (footprint "eagle-import:TESTVIA_ROUND_0.8MM")
      (libsource (lib "eagle-import") (part "TESTPOINT_VIA_ROUND_0.8MM"))
    )
    (comp (ref "TP4")
      (value "TESTPOINT_VIA_ROUND_0.8MM")
      (footprint "eagle-import:TESTVIA_ROUND_0.8MM")
      (libsource (lib "eagle-import") (part "TESTPOINT_VIA_ROUND_0.8MM"))
    )
    (comp (ref "TP5")
      (value "TESTPOINT_VIA_ROUND_0.8MM")
      (footprint "eagle-import:TESTVIA_ROUND_0.8MM")
      (libsource (lib "eagle-import") (part "TESTPOINT_VIA_ROUND_0.8MM"))
    )
    (comp (ref "TP6")
      (value "TESTPOINT_VIA_ROUND_0.8MM")
      (footprint "eagle-import:TESTVIA_ROUND_0.8MM")
      (libsource (lib "eagle-import") (part "TESTPOINT_VIA_ROUND_0.8MM"))
    )
    (comp (ref "TP7")
      (value "TESTPOINT_VIA_ROUND_0.8MM")
      (footprint "eagle-import:TESTVIA_ROUND_0.8MM")
      (libsource (lib "eagle-import") (part "TESTPOINT_VIA_ROUND_0.8MM"))
    )
    (comp (ref "TP8")
      (value "TESTPOINT_VIA_ROUND_0.8MM")
      (footprint "eagle-import:TESTVIA_ROUND_0.8MM")
      (libsource (lib "eagle-import") (part "TESTPOINT_VIA_ROUND_0.8MM"))
    )
    (comp (ref "TP9")
      (value "TESTPOINT_VIA_ROUND_0.8MM")
      (footprint "eagle-import:TESTVIA_ROUND_0.8MM")
      (libsource (lib "eagle-import") (part "TESTPOINT_VIA_ROUND_0.8MM"))
    )
    (comp (ref "TP10")
      (value "TESTPOINT_VIA_ROUND_0.8MM")
      (footprint "eagle-import:TESTVIA_ROUND_0.8MM")
      (libsource (lib "eagle-import") (part "TESTPOINT_VIA_ROUND_0.8MM"))
    )
    (comp (ref "TP11")
      (value "TESTPOINT_VIA_ROUND_0.8MM")
      (footprint "eagle-import:TESTVIA_ROUND_0.8MM")
      (libsource (lib "eagle-import") (part "TESTPOINT_VIA_ROUND_0.8MM"))
    )
    (comp (ref "TP17")
      (value "TESTPOINT_VIA_ROUND_0.8MM")
      (footprint "eagle-import:TESTVIA_ROUND_0.8MM")
      (libsource (lib "eagle-import") (part "TESTPOINT_VIA_ROUND_0.8MM"))
    )
    (comp (ref "TP18")
      (value "TESTPOINT_VIA_ROUND_0.8MM")
      (footprint "eagle-import:TESTVIA_ROUND_0.8MM")
      (libsource (lib "eagle-import") (part "TESTPOINT_VIA_ROUND_0.8MM"))
    )
    (comp (ref "TP23")
      (value "TESTPOINT_VIA_ROUND_0.8MM")
      (footprint "eagle-import:TESTVIA_ROUND_0.8MM")
      (libsource (lib "eagle-import") (part "TESTPOINT_VIA_ROUND_0.8MM"))
    )
    (comp (ref "TP24")
      (value "TESTPOINT_VIA_ROUND_0.8MM")
      (footprint "eagle-import:TESTVIA_ROUND_0.8MM")
      (libsource (lib "eagle-import") (part "TESTPOINT_VIA_ROUND_0.8MM"))
    )
    (comp (ref "TP25")
      (value "TESTPOINT_VIA_ROUND_0.8MM")
      (footprint "eagle-import:TESTVIA_ROUND_0.8MM")
      (libsource (lib "eagle-import") (part "TESTPOINT_VIA_ROUND_0.8MM"))
    )
    (comp (ref "TP26")
      (value "TESTPOINT_VIA_ROUND_0.8MM")
      (footprint "eagle-import:TESTVIA_ROUND_0.8MM")
      (libsource (lib "eagle-import") (part "TESTPOINT_VIA_ROUND_0.8MM"))
    )
    (comp (ref "TP27")
      (value "TESTPOINT_VIA_ROUND_0.8MM")
      (footprint "eagle-import:TESTVIA_ROUND_0.8MM")
      (libsource (lib "eagle-import") (part "TESTPOINT_VIA_ROUND_0.8MM"))
    )
    (comp (ref "TP28")
      (value "TESTPOINT_VIA_ROUND_0.8MM")
      (footprint "eagle-import:TESTVIA_ROUND_0.8MM")
      (libsource (lib "eagle-import") (part "TESTPOINT_VIA_ROUND_0.8MM"))
    )
    (comp (ref "TP29")
      (value "TESTPOINT_VIA_ROUND_0.8MM")
      (footprint "eagle-import:TESTVIA_ROUND_0.8MM")
      (libsource (lib "eagle-import") (part "TESTPOINT_VIA_ROUND_0.8MM"))
    )
    (comp (ref "TP30")
      (value "TESTPOINT_VIA_ROUND_0.8MM")
      (footprint "eagle-import:TESTVIA_ROUND_0.8MM")
      (libsource (lib "eagle-import") (part "TESTPOINT_VIA_ROUND_0.8MM"))
    )
    (comp (ref "TP31")
      (value "TESTPOINT_VIA_ROUND_0.8MM")
      (footprint "eagle-import:TESTVIA_ROUND_0.8MM")
      (libsource (lib "eagle-import") (part "TESTPOINT_VIA_ROUND_0.8MM"))
    )
    (comp (ref "TP32")
      (value "TESTPOINT_VIA_ROUND_0.8MM")
      (footprint "eagle-import:TESTVIA_ROUND_0.8MM")
      (libsource (lib "eagle-import") (part "TESTPOINT_VIA_ROUND_0.8MM"))
    )
    (comp (ref "TP33")
      (value "TESTPOINT_VIA_ROUND_0.8MM")
      (footprint "eagle-import:TESTVIA_ROUND_0.8MM")
      (libsource (lib "eagle-import") (part "TESTPOINT_VIA_ROUND_0.8MM"))
    )
    (comp (ref "TP34")
      (value "TESTPOINT_VIA_ROUND_0.8MM")
      (footprint "eagle-import:TESTVIA_ROUND_0.8MM")
      (libsource (lib "eagle-import") (part "TESTPOINT_VIA_ROUND_0.8MM"))
    )
    (comp (ref "TP35")
      (value "TESTPOINT_VIA_ROUND_0.8MM")
      (footprint "eagle-import:TESTVIA_ROUND_0.8MM")
      (libsource (lib "eagle-import") (part "TESTPOINT_VIA_ROUND_0.8MM"))
    )
    (comp (ref "TP36")
      (value "TESTPOINT_VIA_ROUND_0.8MM")
      (footprint "eagle-import:TESTVIA_ROUND_0.8MM")
      (libsource (lib "eagle-import") (part "TESTPOINT_VIA_ROUND_0.8MM"))
    )
    (comp (ref "TP37")
      (value "TESTPOINT_VIA_ROUND_0.8MM")
      (footprint "eagle-import:TESTVIA_ROUND_0.8MM")
      (libsource (lib "eagle-import") (part "TESTPOINT_VIA_ROUND_0.8MM"))
    )
    (comp (ref "TP38")
      (value "TESTPOINT_VIA_ROUND_0.8MM")
      (footprint "eagle-import:TESTVIA_ROUND_0.8MM")
      (libsource (lib "eagle-import") (part "TESTPOINT_VIA_ROUND_0.8MM"))
    )
    (comp (ref "TP39")
      (value "TESTPOINT_VIA_ROUND_0.8MM")
      (footprint "eagle-import:TESTVIA_ROUND_0.8MM")
      (libsource (lib "eagle-import") (part "TESTPOINT_VIA_ROUND_0.8MM"))
    )
    (comp (ref "TP40")
      (value "TESTPOINT_VIA_ROUND_0.8MM")
      (footprint "eagle-import:TESTVIA_ROUND_0.8MM")
      (libsource (lib "eagle-import") (part "TESTPOINT_VIA_ROUND_0.8MM"))
    )
    (comp (ref "TP41")
      (value "TESTPOINT_VIA_ROUND_0.8MM")
      (footprint "eagle-import:TESTVIA_ROUND_0.8MM")
      (libsource (lib "eagle-import") (part "TESTPOINT_VIA_ROUND_0.8MM"))
    )
    (comp (ref "TP42")
      (value "TESTPOINT_VIA_ROUND_0.8MM")
      (footprint "eagle-import:TESTVIA_ROUND_0.8MM")
      (libsource (lib "eagle-import") (part "TESTPOINT_VIA_ROUND_0.8MM"))
    )
    (comp (ref "TP43")
      (value "TESTPOINT_VIA_ROUND_0.8MM")
      (footprint "eagle-import:TESTVIA_ROUND_0.8MM")
      (libsource (lib "eagle-import") (part "TESTPOINT_VIA_ROUND_0.8MM"))
    )
    (comp (ref "X1")
      (value "MUSBR-M5C1-M0")
      (footprint "eagle-import:MUSBR-M5C1-XX_AMPHENOL")
      (fields (field (name "MANUFACTURER") "Amphenol"))
      (libsource (lib "eagle-import") (part "MUSBR-M5C1-M0"))
    )
    (comp (ref "X2")
      (value "665102131822")
      (footprint "eagle-import:665102131822_WURTH")
      (fields (field (name "MANUFACTURER") "Wuerth") (field (name "VOLTAGE") "50.0 V"))
      (libsource (lib "eagle-import") (part "665102131822"))
    )
    (comp (ref "X6")
      (value "TC2030-CTX")
      (footprint "eagle-import:TC2030-IDC-FP_TAGCONNECT")
      (libsource (lib "eagle-import") (part "TC2030-CTX"))
    )
    (comp (ref "X7")
      (value "WIREPAD_0.8X6.5MM")
      (footprint "eagle-import:WIREPAD_0.8X6.5MM")
      (libsource (lib "eagle-import") (part "WIREPAD_0.8X6.5MM"))
    )
    (comp (ref "X8")
      (value "WIREPAD_0.8X6.5MM")
      (footprint "eagle-import:WIREPAD_0.8X6.5MM")
      (libsource (lib "eagle-import") (part "WIREPAD_0.8X6.5MM"))
    )
    (comp (ref "X9")
      (value "WIREPAD_0.8X6.5MM")
      (footprint "eagle-import:WIREPAD_0.8X6.5MM")
      (libsource (lib "eagle-import") (part "WIREPAD_0.8X6.5MM"))
    )
    (comp (ref "X10")
      (value "WIREPAD_0.8X6.5MM")
      (footprint "eagle-import:WIREPAD_0.8X6.5MM")
      (libsource (lib "eagle-import") (part "WIREPAD_0.8X6.5MM"))
    )
    (comp (ref "X11")
      (value "WIREPAD_0.8X6.5MM")
      (footprint "eagle-import:WIREPAD_0.8X6.5MM")
      (libsource (lib "eagle-import") (part "WIREPAD_0.8X6.5MM"))
    )
    (comp (ref "X13")
      (value "n.m.")
      (footprint "eagle-import:SSW-110-03-G-S-RA-LL_SAMTEC")
      (fields (field (name "MANUFACTURER") "Samtec") (field (name "VOLTAGE") "465 VAC"))
      (libsource (lib "eagle-import") (part "SSW-110-03-G-S-RA-LL"))
    )
    (comp (ref "X14")
      (value "665102131822")
      (footprint "eagle-import:665102131822_WURTH")
      (fields (field (name "MANUFACTURER") "Wuerth") (field (name "VOLTAGE") "50.0 V"))
      (libsource (lib "eagle-import") (part "665102131822"))
    )
    (comp (ref "X21")
      (value "TC2030-CTX")
      (footprint "eagle-import:TC2030-IDC-FP_TAGCONNECT")
      (libsource (lib "eagle-import") (part "TC2030-CTX"))
    )
  )
  (nets
    (net (code "1") (name "+3V3") (class "Default")
      (node (ref "C21") (pin "1") (pinfunction "1_1") (pintype "passive"))
      (node (ref "C63") (pin "1") (pinfunction "1_1") (pintype "passive"))
      (node (ref "D12") (pin "1") (pinfunction "A_1") (pintype "passive"))
      (node (ref "D13") (pin "1") (pinfunction "A_1") (pintype "passive"))
      (node (ref "D14") (pin "1") (pinfunction "A_1") (pintype "passive"))
      (node (ref "D15") (pin "1") (pinfunction "A_1") (pintype "passive"))
      (node (ref "D16") (pin "1") (pinfunction "A_1") (pintype "passive"))
      (node (ref "D17") (pin "1") (pinfunction "A_1") (pintype "passive"))
      (node (ref "D18") (pin "1") (pinfunction "A_1") (pintype "passive"))
      (node (ref "D2") (pin "1") (pinfunction "A_1") (pintype "passive"))
      (node (ref "D3") (pin "1") (pinfunction "A_1") (pintype "passive"))
      (node (ref "D9") (pin "1") (pinfunction "A_1") (pintype "passive"))
      (node (ref "IC14") (pin "5") (pinfunction "VBUS_5") (pintype "input"))
      (node (ref "IC6") (pin "5") (pinfunction "VBUS_5") (pintype "input"))
      (node (ref "R123") (pin "2") (pinfunction "2_2") (pintype "passive"))
      (node (ref "R124") (pin "2") (pinfunction "2_2") (pintype "passive"))
      (node (ref "R146") (pin "1") (pinfunction "1_1") (pintype "passive"))
      (node (ref "R149") (pin "2") (pinfunction "2_2") (pintype "passive"))
      (node (ref "R18") (pin "2") (pinfunction "2_2") (pintype "passive"))
      (node (ref "R29") (pin "1") (pinfunction "1_1") (pintype "passive"))
      (node (ref "R54") (pin "2") (pinfunction "2_2") (pintype "passive"))
      (node (ref "R55") (pin "2") (pinfunction "2_2") (pintype "passive"))
      (node (ref "R8") (pin "2") (pinfunction "2_2") (pintype "passive"))
      (node (ref "R82") (pin "2") (pinfunction "2_2") (pintype "passive"))
      (node (ref "R93") (pin "2") (pinfunction "2_2") (pintype "passive"))
      (node (ref "R94") (pin "2") (pinfunction "2_2") (pintype "passive"))
      (node (ref "R96") (pin "2") (pinfunction "2_2") (pintype "passive"))
      (node (ref "R97") (pin "2") (pinfunction "2_2") (pintype "passive"))
      (node (ref "R98") (pin "2") (pinfunction "2_2") (pintype "passive"))
      (node (ref "TP17") (pin "P$1") (pinfunction "TP_P$1") (pintype "input"))
      (node (ref "X21") (pin "1") (pinfunction "VCC_1") (pintype "input"))
      (node (ref "X6") (pin "1") (pinfunction "VCC_1") (pintype "input"))
    )
    (net (code "2") (name "+VBAT") (class "Default")
      (node (ref "D10") (pin "A") (pinfunction "A_A") (pintype "passive"))
      (node (ref "F1") (pin "1") (pinfunction "1_1") (pintype "passive"))
      (node (ref "R126") (pin "1") (pinfunction "1_1") (pintype "passive"))
      (node (ref "R15") (pin "1") (pinfunction "1_1") (pintype "passive"))
      (node (ref "R25") (pin "1") (pinfunction "1_1") (pintype "passive"))
      (node (ref "TP25") (pin "P$1") (pinfunction "TP_P$1") (pintype "input"))
      (node (ref "X7") (pin "P$1") (pinfunction "P_P$1") (pintype "passive"))
      (node (ref "X7") (pin "P$10") (pinfunction "P_P$10") (pintype "passive"))
      (node (ref "X7") (pin "P$11") (pinfunction "P_P$11") (pintype "passive"))
      (node (ref "X7") (pin "P$12") (pinfunction "P_P$12") (pintype "passive"))
      (node (ref "X7") (pin "P$13") (pinfunction "P_P$13") (pintype "passive"))
      (node (ref "X7") (pin "P$14") (pinfunction "P_P$14") (pintype "passive"))
      (node (ref "X7") (pin "P$15") (pinfunction "P_P$15") (pintype "passive"))
      (node (ref "X7") (pin "P$16") (pinfunction "P_P$16") (pintype "passive"))
      (node (ref "X7") (pin "P$17") (pinfunction "P_P$17") (pintype "passive"))
      (node (ref "X7") (pin "P$18") (pinfunction "P_P$18") (pintype "passive"))
      (node (ref "X7") (pin "P$19") (pinfunction "P_P$19") (pintype "passive"))
      (node (ref "X7") (pin "P$2") (pinfunction "P_P$2") (pintype "passive"))
      (node (ref "X7") (pin "P$20") (pinfunction "P_P$20") (pintype "passive"))
      (node (ref "X7") (pin "P$21") (pinfunction "P_P$21") (pintype "passive"))
      (node (ref "X7") (pin "P$22") (pinfunction "P_P$22") (pintype "passive"))
      (node (ref "X7") (pin "P$23") (pinfunction "P_P$23") (pintype "passive"))
      (node (ref "X7") (pin "P$24") (pinfunction "P_P$24") (pintype "passive"))
      (node (ref "X7") (pin "P$25") (pinfunction "P_P$25") (pintype "passive"))
      (node (ref "X7") (pin "P$26") (pinfunction "P_P$26") (pintype "passive"))
      (node (ref "X7") (pin "P$27") (pinfunction "P_P$27") (pintype "passive"))
      (node (ref "X7") (pin "P$28") (pinfunction "P_P$28") (pintype "passive"))
      (node (ref "X7") (pin "P$29") (pinfunction "P_P$29") (pintype "passive"))
      (node (ref "X7") (pin "P$3") (pinfunction "P_P$3") (pintype "passive"))
      (node (ref "X7") (pin "P$30") (pinfunction "P_P$30") (pintype "passive"))
      (node (ref "X7") (pin "P$31") (pinfunction "P_P$31") (pintype "passive"))
      (node (ref "X7") (pin "P$32") (pinfunction "P_P$32") (pintype "passive"))
      (node (ref "X7") (pin "P$33") (pinfunction "P_P$33") (pintype "passive"))
      (node (ref "X7") (pin "P$34") (pinfunction "P_P$34") (pintype "passive"))
      (node (ref "X7") (pin "P$35") (pinfunction "P_P$35") (pintype "passive"))
      (node (ref "X7") (pin "P$36") (pinfunction "P_P$36") (pintype "passive"))
      (node (ref "X7") (pin "P$37") (pinfunction "P_P$37") (pintype "passive"))
      (node (ref "X7") (pin "P$38") (pinfunction "P_P$38") (pintype "passive"))
      (node (ref "X7") (pin "P$39") (pinfunction "P_P$39") (pintype "passive"))
      (node (ref "X7") (pin "P$4") (pinfunction "P_P$4") (pintype "passive"))
      (node (ref "X7") (pin "P$40") (pinfunction "P_P$40") (pintype "passive"))
      (node (ref "X7") (pin "P$41") (pinfunction "P_P$41") (pintype "passive"))
      (node (ref "X7") (pin "P$42") (pinfunction "P_P$42") (pintype "passive"))
      (node (ref "X7") (pin "P$43") (pinfunction "P_P$43") (pintype "passive"))
      (node (ref "X7") (pin "P$44") (pinfunction "P_P$44") (pintype "passive"))
      (node (ref "X7") (pin "P$45") (pinfunction "P_P$45") (pintype "passive"))
      (node (ref "X7") (pin "P$46") (pinfunction "P_P$46") (pintype "passive"))
      (node (ref "X7") (pin "P$47") (pinfunction "P_P$47") (pintype "passive"))
      (node (ref "X7") (pin "P$48") (pinfunction "P_P$48") (pintype "passive"))
      (node (ref "X7") (pin "P$49") (pinfunction "P_P$49") (pintype "passive"))
      (node (ref "X7") (pin "P$5") (pinfunction "P_P$5") (pintype "passive"))
      (node (ref "X7") (pin "P$50") (pinfunction "P_P$50") (pintype "passive"))
      (node (ref "X7") (pin "P$51") (pinfunction "P_P$51") (pintype "passive"))
      (node (ref "X7") (pin "P$52") (pinfunction "P_P$52") (pintype "passive"))
      (node (ref "X7") (pin "P$53") (pinfunction "P_P$53") (pintype "passive"))
      (node (ref "X7") (pin "P$54") (pinfunction "P_P$54") (pintype "passive"))
      (node (ref "X7") (pin "P$55") (pinfunction "P_P$55") (pintype "passive"))
      (node (ref "X7") (pin "P$56") (pinfunction "P_P$56") (pintype "passive"))
      (node (ref "X7") (pin "P$57") (pinfunction "P_P$57") (pintype "passive"))
      (node (ref "X7") (pin "P$58") (pinfunction "P_P$58") (pintype "passive"))
      (node (ref "X7") (pin "P$59") (pinfunction "P_P$59") (pintype "passive"))
      (node (ref "X7") (pin "P$6") (pinfunction "P_P$6") (pintype "passive"))
      (node (ref "X7") (pin "P$60") (pinfunction "P_P$60") (pintype "passive"))
      (node (ref "X7") (pin "P$61") (pinfunction "P_P$61") (pintype "passive"))
      (node (ref "X7") (pin "P$62") (pinfunction "P_P$62") (pintype "passive"))
      (node (ref "X7") (pin "P$63") (pinfunction "P_P$63") (pintype "passive"))
      (node (ref "X7") (pin "P$64") (pinfunction "P_P$64") (pintype "passive"))
      (node (ref "X7") (pin "P$65") (pinfunction "P_P$65") (pintype "passive"))
      (node (ref "X7") (pin "P$66") (pinfunction "P_P$66") (pintype "passive"))
      (node (ref "X7") (pin "P$67") (pinfunction "P_P$67") (pintype "passive"))
      (node (ref "X7") (pin "P$7") (pinfunction "P_P$7") (pintype "passive"))
      (node (ref "X7") (pin "P$8") (pinfunction "P_P$8") (pintype "passive"))
      (node (ref "X7") (pin "P$9") (pinfunction "P_P$9") (pintype "passive"))
    )
    (net (code "3") (name "/BQ769X2_CFETOFF{slash}~{CS}") (class "Default")
      (node (ref "IC26") (pin "29") (pinfunction "CFETOFF_29") (pintype "bidirectional"))
      (node (ref "R142") (pin "1") (pinfunction "1_1") (pintype "passive"))
      (node (ref "R95") (pin "1") (pinfunction "1_1") (pintype "passive"))
      (node (ref "R98") (pin "1") (pinfunction "1_1") (pintype "passive"))
    )
    (net (code "4") (name "/UART_DBG_EXT->UC") (class "Default")
      (node (ref "R146") (pin "2") (pinfunction "2_2") (pintype "passive"))
      (node (ref "R177") (pin "1") (pinfunction "1_1") (pintype "passive"))
      (node (ref "TP31") (pin "P$1") (pinfunction "TP_P$1") (pintype "input"))
    )
    (net (code "5") (name "/UART_DBG_UC->EXT") (class "Default")
      (node (ref "R176") (pin "1") (pinfunction "1_1") (pintype "passive"))
      (node (ref "TP30") (pin "P$1") (pinfunction "TP_P$1") (pintype "input"))
    )
    (net (code "6") (name "/V1") (class "Default")
      (node (ref "R135") (pin "1") (pinfunction "1_1") (pintype "passive"))
      (node (ref "R21") (pin "1") (pinfunction "1_1") (pintype "passive"))
      (node (ref "TP28") (pin "P$1") (pinfunction "TP_P$1") (pintype "input"))
      (node (ref "X10") (pin "P$1") (pinfunction "P_P$1") (pintype "passive"))
      (node (ref "X10") (pin "P$10") (pinfunction "P_P$10") (pintype "passive"))
      (node (ref "X10") (pin "P$11") (pinfunction "P_P$11") (pintype "passive"))
      (node (ref "X10") (pin "P$12") (pinfunction "P_P$12") (pintype "passive"))
      (node (ref "X10") (pin "P$13") (pinfunction "P_P$13") (pintype "passive"))
      (node (ref "X10") (pin "P$14") (pinfunction "P_P$14") (pintype "passive"))
      (node (ref "X10") (pin "P$15") (pinfunction "P_P$15") (pintype "passive"))
      (node (ref "X10") (pin "P$16") (pinfunction "P_P$16") (pintype "passive"))
      (node (ref "X10") (pin "P$17") (pinfunction "P_P$17") (pintype "passive"))
      (node (ref "X10") (pin "P$18") (pinfunction "P_P$18") (pintype "passive"))
      (node (ref "X10") (pin "P$19") (pinfunction "P_P$19") (pintype "passive"))
      (node (ref "X10") (pin "P$2") (pinfunction "P_P$2") (pintype "passive"))
      (node (ref "X10") (pin "P$20") (pinfunction "P_P$20") (pintype "passive"))
      (node (ref "X10") (pin "P$21") (pinfunction "P_P$21") (pintype "passive"))
      (node (ref "X10") (pin "P$22") (pinfunction "P_P$22") (pintype "passive"))
      (node (ref "X10") (pin "P$23") (pinfunction "P_P$23") (pintype "passive"))
      (node (ref "X10") (pin "P$24") (pinfunction "P_P$24") (pintype "passive"))
      (node (ref "X10") (pin "P$25") (pinfunction "P_P$25") (pintype "passive"))
      (node (ref "X10") (pin "P$26") (pinfunction "P_P$26") (pintype "passive"))
      (node (ref "X10") (pin "P$27") (pinfunction "P_P$27") (pintype "passive"))
      (node (ref "X10") (pin "P$28") (pinfunction "P_P$28") (pintype "passive"))
      (node (ref "X10") (pin "P$29") (pinfunction "P_P$29") (pintype "passive"))
      (node (ref "X10") (pin "P$3") (pinfunction "P_P$3") (pintype "passive"))
      (node (ref "X10") (pin "P$30") (pinfunction "P_P$30") (pintype "passive"))
      (node (ref "X10") (pin "P$31") (pinfunction "P_P$31") (pintype "passive"))
      (node (ref "X10") (pin "P$32") (pinfunction "P_P$32") (pintype "passive"))
      (node (ref "X10") (pin "P$33") (pinfunction "P_P$33") (pintype "passive"))
      (node (ref "X10") (pin "P$34") (pinfunction "P_P$34") (pintype "passive"))
      (node (ref "X10") (pin "P$35") (pinfunction "P_P$35") (pintype "passive"))
      (node (ref "X10") (pin "P$36") (pinfunction "P_P$36") (pintype "passive"))
      (node (ref "X10") (pin "P$37") (pinfunction "P_P$37") (pintype "passive"))
      (node (ref "X10") (pin "P$38") (pinfunction "P_P$38") (pintype "passive"))
      (node (ref "X10") (pin "P$39") (pinfunction "P_P$39") (pintype "passive"))
      (node (ref "X10") (pin "P$4") (pinfunction "P_P$4") (pintype "passive"))
      (node (ref "X10") (pin "P$40") (pinfunction "P_P$40") (pintype "passive"))
      (node (ref "X10") (pin "P$41") (pinfunction "P_P$41") (pintype "passive"))
      (node (ref "X10") (pin "P$42") (pinfunction "P_P$42") (pintype "passive"))
      (node (ref "X10") (pin "P$43") (pinfunction "P_P$43") (pintype "passive"))
      (node (ref "X10") (pin "P$44") (pinfunction "P_P$44") (pintype "passive"))
      (node (ref "X10") (pin "P$45") (pinfunction "P_P$45") (pintype "passive"))
      (node (ref "X10") (pin "P$46") (pinfunction "P_P$46") (pintype "passive"))
      (node (ref "X10") (pin "P$47") (pinfunction "P_P$47") (pintype "passive"))
      (node (ref "X10") (pin "P$48") (pinfunction "P_P$48") (pintype "passive"))
      (node (ref "X10") (pin "P$49") (pinfunction "P_P$49") (pintype "passive"))
      (node (ref "X10") (pin "P$5") (pinfunction "P_P$5") (pintype "passive"))
      (node (ref "X10") (pin "P$50") (pinfunction "P_P$50") (pintype "passive"))
      (node (ref "X10") (pin "P$51") (pinfunction "P_P$51") (pintype "passive"))
      (node (ref "X10") (pin "P$52") (pinfunction "P_P$52") (pintype "passive"))
      (node (ref "X10") (pin "P$53") (pinfunction "P_P$53") (pintype "passive"))
      (node (ref "X10") (pin "P$54") (pinfunction "P_P$54") (pintype "passive"))
      (node (ref "X10") (pin "P$55") (pinfunction "P_P$55") (pintype "passive"))
      (node (ref "X10") (pin "P$56") (pinfunction "P_P$56") (pintype "passive"))
      (node (ref "X10") (pin "P$57") (pinfunction "P_P$57") (pintype "passive"))
      (node (ref "X10") (pin "P$58") (pinfunction "P_P$58") (pintype "passive"))
      (node (ref "X10") (pin "P$59") (pinfunction "P_P$59") (pintype "passive"))
      (node (ref "X10") (pin "P$6") (pinfunction "P_P$6") (pintype "passive"))
      (node (ref "X10") (pin "P$60") (pinfunction "P_P$60") (pintype "passive"))
      (node (ref "X10") (pin "P$61") (pinfunction "P_P$61") (pintype "passive"))
      (node (ref "X10") (pin "P$62") (pinfunction "P_P$62") (pintype "passive"))
      (node (ref "X10") (pin "P$63") (pinfunction "P_P$63") (pintype "passive"))
      (node (ref "X10") (pin "P$64") (pinfunction "P_P$64") (pintype "passive"))
      (node (ref "X10") (pin "P$65") (pinfunction "P_P$65") (pintype "passive"))
      (node (ref "X10") (pin "P$66") (pinfunction "P_P$66") (pintype "passive"))
      (node (ref "X10") (pin "P$67") (pinfunction "P_P$67") (pintype "passive"))
      (node (ref "X10") (pin "P$7") (pinfunction "P_P$7") (pintype "passive"))
      (node (ref "X10") (pin "P$8") (pinfunction "P_P$8") (pintype "passive"))
      (node (ref "X10") (pin "P$9") (pinfunction "P_P$9") (pintype "passive"))
    )
    (net (code "7") (name "/V2") (class "Default")
      (node (ref "R132") (pin "1") (pinfunction "1_1") (pintype "passive"))
      (node (ref "R20") (pin "1") (pinfunction "1_1") (pintype "passive"))
      (node (ref "TP27") (pin "P$1") (pinfunction "TP_P$1") (pintype "input"))
      (node (ref "X9") (pin "P$1") (pinfunction "P_P$1") (pintype "passive"))
      (node (ref "X9") (pin "P$10") (pinfunction "P_P$10") (pintype "passive"))
      (node (ref "X9") (pin "P$11") (pinfunction "P_P$11") (pintype "passive"))
      (node (ref "X9") (pin "P$12") (pinfunction "P_P$12") (pintype "passive"))
      (node (ref "X9") (pin "P$13") (pinfunction "P_P$13") (pintype "passive"))
      (node (ref "X9") (pin "P$14") (pinfunction "P_P$14") (pintype "passive"))
      (node (ref "X9") (pin "P$15") (pinfunction "P_P$15") (pintype "passive"))
      (node (ref "X9") (pin "P$16") (pinfunction "P_P$16") (pintype "passive"))
      (node (ref "X9") (pin "P$17") (pinfunction "P_P$17") (pintype "passive"))
      (node (ref "X9") (pin "P$18") (pinfunction "P_P$18") (pintype "passive"))
      (node (ref "X9") (pin "P$19") (pinfunction "P_P$19") (pintype "passive"))
      (node (ref "X9") (pin "P$2") (pinfunction "P_P$2") (pintype "passive"))
      (node (ref "X9") (pin "P$20") (pinfunction "P_P$20") (pintype "passive"))
      (node (ref "X9") (pin "P$21") (pinfunction "P_P$21") (pintype "passive"))
      (node (ref "X9") (pin "P$22") (pinfunction "P_P$22") (pintype "passive"))
      (node (ref "X9") (pin "P$23") (pinfunction "P_P$23") (pintype "passive"))
      (node (ref "X9") (pin "P$24") (pinfunction "P_P$24") (pintype "passive"))
      (node (ref "X9") (pin "P$25") (pinfunction "P_P$25") (pintype "passive"))
      (node (ref "X9") (pin "P$26") (pinfunction "P_P$26") (pintype "passive"))
      (node (ref "X9") (pin "P$27") (pinfunction "P_P$27") (pintype "passive"))
      (node (ref "X9") (pin "P$28") (pinfunction "P_P$28") (pintype "passive"))
      (node (ref "X9") (pin "P$29") (pinfunction "P_P$29") (pintype "passive"))
      (node (ref "X9") (pin "P$3") (pinfunction "P_P$3") (pintype "passive"))
      (node (ref "X9") (pin "P$30") (pinfunction "P_P$30") (pintype "passive"))
      (node (ref "X9") (pin "P$31") (pinfunction "P_P$31") (pintype "passive"))
      (node (ref "X9") (pin "P$32") (pinfunction "P_P$32") (pintype "passive"))
      (node (ref "X9") (pin "P$33") (pinfunction "P_P$33") (pintype "passive"))
      (node (ref "X9") (pin "P$34") (pinfunction "P_P$34") (pintype "passive"))
      (node (ref "X9") (pin "P$35") (pinfunction "P_P$35") (pintype "passive"))
      (node (ref "X9") (pin "P$36") (pinfunction "P_P$36") (pintype "passive"))
      (node (ref "X9") (pin "P$37") (pinfunction "P_P$37") (pintype "passive"))
      (node (ref "X9") (pin "P$38") (pinfunction "P_P$38") (pintype "passive"))
      (node (ref "X9") (pin "P$39") (pinfunction "P_P$39") (pintype "passive"))
      (node (ref "X9") (pin "P$4") (pinfunction "P_P$4") (pintype "passive"))
      (node (ref "X9") (pin "P$40") (pinfunction "P_P$40") (pintype "passive"))
      (node (ref "X9") (pin "P$41") (pinfunction "P_P$41") (pintype "passive"))
      (node (ref "X9") (pin "P$42") (pinfunction "P_P$42") (pintype "passive"))
      (node (ref "X9") (pin "P$43") (pinfunction "P_P$43") (pintype "passive"))
      (node (ref "X9") (pin "P$44") (pinfunction "P_P$44") (pintype "passive"))
      (node (ref "X9") (pin "P$45") (pinfunction "P_P$45") (pintype "passive"))
      (node (ref "X9") (pin "P$46") (pinfunction "P_P$46") (pintype "passive"))
      (node (ref "X9") (pin "P$47") (pinfunction "P_P$47") (pintype "passive"))
      (node (ref "X9") (pin "P$48") (pinfunction "P_P$48") (pintype "passive"))
      (node (ref "X9") (pin "P$49") (pinfunction "P_P$49") (pintype "passive"))
      (node (ref "X9") (pin "P$5") (pinfunction "P_P$5") (pintype "passive"))
      (node (ref "X9") (pin "P$50") (pinfunction "P_P$50") (pintype "passive"))
      (node (ref "X9") (pin "P$51") (pinfunction "P_P$51") (pintype "passive"))
      (node (ref "X9") (pin "P$52") (pinfunction "P_P$52") (pintype "passive"))
      (node (ref "X9") (pin "P$53") (pinfunction "P_P$53") (pintype "passive"))
      (node (ref "X9") (pin "P$54") (pinfunction "P_P$54") (pintype "passive"))
      (node (ref "X9") (pin "P$55") (pinfunction "P_P$55") (pintype "passive"))
      (node (ref "X9") (pin "P$56") (pinfunction "P_P$56") (pintype "passive"))
      (node (ref "X9") (pin "P$57") (pinfunction "P_P$57") (pintype "passive"))
      (node (ref "X9") (pin "P$58") (pinfunction "P_P$58") (pintype "passive"))
      (node (ref "X9") (pin "P$59") (pinfunction "P_P$59") (pintype "passive"))
      (node (ref "X9") (pin "P$6") (pinfunction "P_P$6") (pintype "passive"))
      (node (ref "X9") (pin "P$60") (pinfunction "P_P$60") (pintype "passive"))
      (node (ref "X9") (pin "P$61") (pinfunction "P_P$61") (pintype "passive"))
      (node (ref "X9") (pin "P$62") (pinfunction "P_P$62") (pintype "passive"))
      (node (ref "X9") (pin "P$63") (pinfunction "P_P$63") (pintype "passive"))
      (node (ref "X9") (pin "P$64") (pinfunction "P_P$64") (pintype "passive"))
      (node (ref "X9") (pin "P$65") (pinfunction "P_P$65") (pintype "passive"))
      (node (ref "X9") (pin "P$66") (pinfunction "P_P$66") (pintype "passive"))
      (node (ref "X9") (pin "P$67") (pinfunction "P_P$67") (pintype "passive"))
      (node (ref "X9") (pin "P$7") (pinfunction "P_P$7") (pintype "passive"))
      (node (ref "X9") (pin "P$8") (pinfunction "P_P$8") (pintype "passive"))
      (node (ref "X9") (pin "P$9") (pinfunction "P_P$9") (pintype "passive"))
    )
    (net (code "8") (name "/V3") (class "Default")
      (node (ref "R129") (pin "1") (pinfunction "1_1") (pintype "passive"))
      (node (ref "R17") (pin "1") (pinfunction "1_1") (pintype "passive"))
      (node (ref "TP26") (pin "P$1") (pinfunction "TP_P$1") (pintype "input"))
      (node (ref "X8") (pin "P$1") (pinfunction "P_P$1") (pintype "passive"))
      (node (ref "X8") (pin "P$10") (pinfunction "P_P$10") (pintype "passive"))
      (node (ref "X8") (pin "P$11") (pinfunction "P_P$11") (pintype "passive"))
      (node (ref "X8") (pin "P$12") (pinfunction "P_P$12") (pintype "passive"))
      (node (ref "X8") (pin "P$13") (pinfunction "P_P$13") (pintype "passive"))
      (node (ref "X8") (pin "P$14") (pinfunction "P_P$14") (pintype "passive"))
      (node (ref "X8") (pin "P$15") (pinfunction "P_P$15") (pintype "passive"))
      (node (ref "X8") (pin "P$16") (pinfunction "P_P$16") (pintype "passive"))
      (node (ref "X8") (pin "P$17") (pinfunction "P_P$17") (pintype "passive"))
      (node (ref "X8") (pin "P$18") (pinfunction "P_P$18") (pintype "passive"))
      (node (ref "X8") (pin "P$19") (pinfunction "P_P$19") (pintype "passive"))
      (node (ref "X8") (pin "P$2") (pinfunction "P_P$2") (pintype "passive"))
      (node (ref "X8") (pin "P$20") (pinfunction "P_P$20") (pintype "passive"))
      (node (ref "X8") (pin "P$21") (pinfunction "P_P$21") (pintype "passive"))
      (node (ref "X8") (pin "P$22") (pinfunction "P_P$22") (pintype "passive"))
      (node (ref "X8") (pin "P$23") (pinfunction "P_P$23") (pintype "passive"))
      (node (ref "X8") (pin "P$24") (pinfunction "P_P$24") (pintype "passive"))
      (node (ref "X8") (pin "P$25") (pinfunction "P_P$25") (pintype "passive"))
      (node (ref "X8") (pin "P$26") (pinfunction "P_P$26") (pintype "passive"))
      (node (ref "X8") (pin "P$27") (pinfunction "P_P$27") (pintype "passive"))
      (node (ref "X8") (pin "P$28") (pinfunction "P_P$28") (pintype "passive"))
      (node (ref "X8") (pin "P$29") (pinfunction "P_P$29") (pintype "passive"))
      (node (ref "X8") (pin "P$3") (pinfunction "P_P$3") (pintype "passive"))
      (node (ref "X8") (pin "P$30") (pinfunction "P_P$30") (pintype "passive"))
      (node (ref "X8") (pin "P$31") (pinfunction "P_P$31") (pintype "passive"))
      (node (ref "X8") (pin "P$32") (pinfunction "P_P$32") (pintype "passive"))
      (node (ref "X8") (pin "P$33") (pinfunction "P_P$33") (pintype "passive"))
      (node (ref "X8") (pin "P$34") (pinfunction "P_P$34") (pintype "passive"))
      (node (ref "X8") (pin "P$35") (pinfunction "P_P$35") (pintype "passive"))
      (node (ref "X8") (pin "P$36") (pinfunction "P_P$36") (pintype "passive"))
      (node (ref "X8") (pin "P$37") (pinfunction "P_P$37") (pintype "passive"))
      (node (ref "X8") (pin "P$38") (pinfunction "P_P$38") (pintype "passive"))
      (node (ref "X8") (pin "P$39") (pinfunction "P_P$39") (pintype "passive"))
      (node (ref "X8") (pin "P$4") (pinfunction "P_P$4") (pintype "passive"))
      (node (ref "X8") (pin "P$40") (pinfunction "P_P$40") (pintype "passive"))
      (node (ref "X8") (pin "P$41") (pinfunction "P_P$41") (pintype "passive"))
      (node (ref "X8") (pin "P$42") (pinfunction "P_P$42") (pintype "passive"))
      (node (ref "X8") (pin "P$43") (pinfunction "P_P$43") (pintype "passive"))
      (node (ref "X8") (pin "P$44") (pinfunction "P_P$44") (pintype "passive"))
      (node (ref "X8") (pin "P$45") (pinfunction "P_P$45") (pintype "passive"))
      (node (ref "X8") (pin "P$46") (pinfunction "P_P$46") (pintype "passive"))
      (node (ref "X8") (pin "P$47") (pinfunction "P_P$47") (pintype "passive"))
      (node (ref "X8") (pin "P$48") (pinfunction "P_P$48") (pintype "passive"))
      (node (ref "X8") (pin "P$49") (pinfunction "P_P$49") (pintype "passive"))
      (node (ref "X8") (pin "P$5") (pinfunction "P_P$5") (pintype "passive"))
      (node (ref "X8") (pin "P$50") (pinfunction "P_P$50") (pintype "passive"))
      (node (ref "X8") (pin "P$51") (pinfunction "P_P$51") (pintype "passive"))
      (node (ref "X8") (pin "P$52") (pinfunction "P_P$52") (pintype "passive"))
      (node (ref "X8") (pin "P$53") (pinfunction "P_P$53") (pintype "passive"))
      (node (ref "X8") (pin "P$54") (pinfunction "P_P$54") (pintype "passive"))
      (node (ref "X8") (pin "P$55") (pinfunction "P_P$55") (pintype "passive"))
      (node (ref "X8") (pin "P$56") (pinfunction "P_P$56") (pintype "passive"))
      (node (ref "X8") (pin "P$57") (pinfunction "P_P$57") (pintype "passive"))
      (node (ref "X8") (pin "P$58") (pinfunction "P_P$58") (pintype "passive"))
      (node (ref "X8") (pin "P$59") (pinfunction "P_P$59") (pintype "passive"))
      (node (ref "X8") (pin "P$6") (pinfunction "P_P$6") (pintype "passive"))
      (node (ref "X8") (pin "P$60") (pinfunction "P_P$60") (pintype "passive"))
      (node (ref "X8") (pin "P$61") (pinfunction "P_P$61") (pintype "passive"))
      (node (ref "X8") (pin "P$62") (pinfunction "P_P$62") (pintype "passive"))
      (node (ref "X8") (pin "P$63") (pinfunction "P_P$63") (pintype "passive"))
      (node (ref "X8") (pin "P$64") (pinfunction "P_P$64") (pintype "passive"))
      (node (ref "X8") (pin "P$65") (pinfunction "P_P$65") (pintype "passive"))
      (node (ref "X8") (pin "P$66") (pinfunction "P_P$66") (pintype "passive"))
      (node (ref "X8") (pin "P$67") (pinfunction "P_P$67") (pintype "passive"))
      (node (ref "X8") (pin "P$7") (pinfunction "P_P$7") (pintype "passive"))
      (node (ref "X8") (pin "P$8") (pinfunction "P_P$8") (pintype "passive"))
      (node (ref "X8") (pin "P$9") (pinfunction "P_P$9") (pintype "passive"))
    )
    (net (code "9") (name "/~{HOST_PRESENT}_3V3") (class "Default")
      (node (ref "IC8") (pin "2") (pinfunction "PC13_2") (pintype "bidirectional"))
      (node (ref "R55") (pin "1") (pinfunction "1_1") (pintype "passive"))
      (node (ref "R59") (pin "2") (pinfunction "2_2") (pintype "passive"))
      (node (ref "R60") (pin "1") (pinfunction "1_1") (pintype "passive"))
    )
    (net (code "10") (name "/~{UC_LED_B}") (class "Default")
      (node (ref "R57") (pin "1") (pinfunction "1_1") (pintype "passive"))
      (node (ref "R89") (pin "2") (pinfunction "2_2") (pintype "passive"))
      (node (ref "T6") (pin "1") (pinfunction "G_1") (pintype "passive"))
    )
    (net (code "11") (name "/~{UC_LED_G}") (class "Default")
      (node (ref "R47") (pin "1") (pinfunction "1_1") (pintype "passive"))
      (node (ref "R88") (pin "2") (pinfunction "2_2") (pintype "passive"))
      (node (ref "T5") (pin "1") (pinfunction "G_1") (pintype "passive"))
    )
    (net (code "12") (name "/~{UC_LED_R}") (class "Default")
      (node (ref "R34") (pin "2") (pinfunction "2_2") (pintype "passive"))
      (node (ref "R46") (pin "1") (pinfunction "1_1") (pintype "passive"))
      (node (ref "T4") (pin "1") (pinfunction "G_1") (pintype "passive"))
    )
    (net (code "13") (name "BQ769X2_ALERT") (class "Default")
      (node (ref "IC26") (pin "25") (pinfunction "ALERT_25") (pintype "bidirectional"))
      (node (ref "R144") (pin "1") (pinfunction "1_1") (pintype "passive"))
      (node (ref "R53") (pin "1") (pinfunction "1_1") (pintype "passive"))
      (node (ref "R96") (pin "1") (pinfunction "1_1") (pintype "passive"))
    )
    (net (code "14") (name "BQ769X2_CHG") (class "Default")
      (node (ref "IC26") (pin "45") (pinfunction "CHG_45") (pintype "output"))
      (node (ref "R80") (pin "1") (pinfunction "1_1") (pintype "passive"))
    )
    (net (code "15") (name "BQ769X2_DSG") (class "Default")
      (node (ref "IC26") (pin "43") (pinfunction "DSG_43") (pintype "output"))
      (node (ref "R81") (pin "2") (pinfunction "2_2") (pintype "passive"))
    )
    (net (code "16") (name "BQ769X2_HDQ{slash}MOSI") (class "Default")
      (node (ref "IC26") (pin "28") (pinfunction "HDQ_28") (pintype "bidirectional"))
      (node (ref "R143") (pin "1") (pinfunction "1_1") (pintype "passive"))
      (node (ref "R58") (pin "1") (pinfunction "1_1") (pintype "passive"))
      (node (ref "R97") (pin "1") (pinfunction "1_1") (pintype "passive"))
    )
    (net (code "17") (name "BQ769X2_NTC") (class "Default")
      (node (ref "C7") (pin "1") (pinfunction "1_1") (pintype "passive"))
      (node (ref "IC26") (pin "21") (pinfunction "TS1_21") (pintype "bidirectional"))
      (node (ref "TP32") (pin "P$1") (pinfunction "TP_P$1") (pintype "input"))
      (node (ref "X14") (pin "1") (pinfunction "1_1") (pintype "passive"))
    )
    (net (code "18") (name "COMMON_DRAIN") (class "Default")
      (node (ref "C28") (pin "1") (pinfunction "1_1") (pintype "passive"))
      (node (ref "C30") (pin "1") (pinfunction "1_1") (pintype "passive"))
      (node (ref "C31") (pin "1") (pinfunction "1_1") (pintype "passive"))
      (node (ref "C32") (pin "1") (pinfunction "1_1") (pintype "passive"))
      (node (ref "C33") (pin "1") (pinfunction "1_1") (pintype "passive"))
      (node (ref "C34") (pin "1") (pinfunction "1_1") (pintype "passive"))
      (node (ref "C35") (pin "1") (pinfunction "1_1") (pintype "passive"))
      (node (ref "C36") (pin "2") (pinfunction "2_2") (pintype "passive"))
      (node (ref "C9") (pin "1") (pinfunction "1_1") (pintype "passive"))
      (node (ref "R36") (pin "2") (pinfunction "2_2") (pintype "passive"))
      (node (ref "R37") (pin "2") (pinfunction "2_2") (pintype "passive"))
      (node (ref "T13") (pin "5") (pinfunction "D_5") (pintype "passive"))
      (node (ref "T14") (pin "5") (pinfunction "D_5") (pintype "passive"))
      (node (ref "TP11") (pin "P$1") (pinfunction "TP_P$1") (pintype "input"))
    )
    (net (code "19") (name "EXT_UC_NRST_3V3") (class "Default")
      (node (ref "IC6") (pin "6") (pinfunction "I/O4_6") (pintype "passive"))
      (node (ref "R67") (pin "2") (pinfunction "2_2") (pintype "passive"))
      (node (ref "X21") (pin "3") (pinfunction "~{RST}_3") (pintype "output"))
      (node (ref "X6") (pin "3") (pinfunction "~{RST}_3") (pintype "output"))
    )
    (net (code "20") (name "EXT_UC_SWCLK_3V3") (class "Default")
      (node (ref "IC6") (pin "3") (pinfunction "I/O2_3") (pintype "passive"))
      (node (ref "R68") (pin "2") (pinfunction "2_2") (pintype "passive"))
      (node (ref "X21") (pin "4") (pinfunction "SWCLK/TCK_4") (pintype "output"))
      (node (ref "X6") (pin "4") (pinfunction "SWCLK/TCK_4") (pintype "output"))
    )
    (net (code "21") (name "EXT_UC_SWDIO_3V3") (class "Default")
      (node (ref "IC6") (pin "1") (pinfunction "I/O1_1") (pintype "passive"))
      (node (ref "R69") (pin "2") (pinfunction "2_2") (pintype "passive"))
      (node (ref "X21") (pin "2") (pinfunction "SWDIO/TMS_2") (pintype "bidirectional"))
      (node (ref "X6") (pin "2") (pinfunction "SWDIO/TMS_2") (pintype "bidirectional"))
    )
    (net (code "22") (name "EXT_UC_SWO_3V3") (class "Default")
      (node (ref "IC6") (pin "4") (pinfunction "I/O3_4") (pintype "passive"))
      (node (ref "R16") (pin "2") (pinfunction "2_2") (pintype "passive"))
      (node (ref "X21") (pin "6") (pinfunction "SWO/TDO_6") (pintype "input"))
      (node (ref "X6") (pin "6") (pinfunction "SWO/TDO_6") (pintype "input"))
    )
    (net (code "23") (name "GND") (class "Default")
      (node (ref "C1") (pin "2") (pinfunction "2_2") (pintype "passive"))
      (node (ref "C10") (pin "2") (pinfunction "2_2") (pintype "passive"))
      (node (ref "C102") (pin "2") (pinfunction "2_2") (pintype "passive"))
      (node (ref "C103") (pin "2") (pinfunction "2_2") (pintype "passive"))
      (node (ref "C11") (pin "2") (pinfunction "2_2") (pintype "passive"))
      (node (ref "C12") (pin "2") (pinfunction "2_2") (pintype "passive"))
      (node (ref "C13") (pin "2") (pinfunction "2_2") (pintype "passive"))
      (node (ref "C16") (pin "2") (pinfunction "2_2") (pintype "passive"))
      (node (ref "C18") (pin "1") (pinfunction "1_1") (pintype "passive"))
      (node (ref "C19") (pin "2") (pinfunction "2_2") (pintype "passive"))
      (node (ref "C2") (pin "2") (pinfunction "2_2") (pintype "passive"))
      (node (ref "C20") (pin "2") (pinfunction "2_2") (pintype "passive"))
      (node (ref "C21") (pin "2") (pinfunction "2_2") (pintype "passive"))
      (node (ref "C22") (pin "2") (pinfunction "2_2") (pintype "passive"))
      (node (ref "C23") (pin "2") (pinfunction "2_2") (pintype "passive"))
      (node (ref "C234") (pin "2") (pinfunction "2_2") (pintype "passive"))
      (node (ref "C235") (pin "2") (pinfunction "2_2") (pintype "passive"))
      (node (ref "C24") (pin "2") (pinfunction "2_2") (pintype "passive"))
      (node (ref "C25") (pin "2") (pinfunction "2_2") (pintype "passive"))
      (node (ref "C26") (pin "2") (pinfunction "2_2") (pintype "passive"))
      (node (ref "C27") (pin "2") (pinfunction "2_2") (pintype "passive"))
      (node (ref "C28") (pin "2") (pinfunction "2_2") (pintype "passive"))
      (node (ref "C282") (pin "2") (pinfunction "2_2") (pintype "passive"))
      (node (ref "C283") (pin "2") (pinfunction "2_2") (pintype "passive"))
      (node (ref "C29") (pin "2") (pinfunction "2_2") (pintype "passive"))
      (node (ref "C295") (pin "2") (pinfunction "2_2") (pintype "passive"))
      (node (ref "C296") (pin "2") (pinfunction "2_2") (pintype "passive"))
      (node (ref "C3") (pin "2") (pinfunction "2_2") (pintype "passive"))
      (node (ref "C30") (pin "2") (pinfunction "2_2") (pintype "passive"))
      (node (ref "C31") (pin "2") (pinfunction "2_2") (pintype "passive"))
      (node (ref "C32") (pin "2") (pinfunction "2_2") (pintype "passive"))
      (node (ref "C33") (pin "2") (pinfunction "2_2") (pintype "passive"))
      (node (ref "C34") (pin "2") (pinfunction "2_2") (pintype "passive"))
      (node (ref "C35") (pin "2") (pinfunction "2_2") (pintype "passive"))
      (node (ref "C38") (pin "1") (pinfunction "1_1") (pintype "passive"))
      (node (ref "C4") (pin "2") (pinfunction "2_2") (pintype "passive"))
      (node (ref "C43") (pin "2") (pinfunction "2_2") (pintype "passive"))
      (node (ref "C44") (pin "2") (pinfunction "2_2") (pintype "passive"))
      (node (ref "C47") (pin "2") (pinfunction "2_2") (pintype "passive"))
      (node (ref "C48") (pin "2") (pinfunction "2_2") (pintype "passive"))
      (node (ref "C5") (pin "2") (pinfunction "2_2") (pintype "passive"))
      (node (ref "C52") (pin "2") (pinfunction "2_2") (pintype "passive"))
      (node (ref "C53") (pin "2") (pinfunction "2_2") (pintype "passive"))
      (node (ref "C6") (pin "2") (pinfunction "2_2") (pintype "passive"))
      (node (ref "C62") (pin "2") (pinfunction "2_2") (pintype "passive"))
      (node (ref "C63") (pin "2") (pinfunction "2_2") (pintype "passive"))
      (node (ref "C64") (pin "2") (pinfunction "2_2") (pintype "passive"))
      (node (ref "C65") (pin "2") (pinfunction "2_2") (pintype "passive"))
      (node (ref "C8") (pin "2") (pinfunction "2_2") (pintype "passive"))
      (node (ref "C9") (pin "2") (pinfunction "2_2") (pintype "passive"))
      (node (ref "D1") (pin "A") (pinfunction "A_A") (pintype "passive"))
      (node (ref "D20") (pin "3") (pinfunction "C_GREEN_3") (pintype "passive"))
      (node (ref "D4") (pin "A") (pinfunction "A_A") (pintype "passive"))
      (node (ref "H1") (pin "B2,3") (pinfunction "MOUNT_B2,3") (pintype "passive"))
      (node (ref "H2") (pin "B2,3") (pinfunction "MOUNT_B2,3") (pintype "passive"))
      (node (ref "IC10") (pin "2") (pinfunction "NC_2") (pintype "passive"))
      (node (ref "IC10") (pin "3") (pinfunction "GND_3") (pintype "input"))
      (node (ref "IC10") (pin "5") (pinfunction "NC_5") (pintype "passive"))
      (node (ref "IC10") (pin "7.1") (pinfunction "GND_7.1") (pintype "input"))
      (node (ref "IC10") (pin "7.2") (pinfunction "GND_7.2") (pintype "input"))
      (node (ref "IC11") (pin "13") (pinfunction "CMPIN_13") (pintype "input"))
      (node (ref "IC11") (pin "22") (pinfunction "GND_22") (pintype "input"))
      (node (ref "IC11") (pin "E1") (pinfunction "GND_E1") (pintype "input"))
      (node (ref "IC11") (pin "E2") (pinfunction "GND_E2") (pintype "input"))
      (node (ref "IC11") (pin "E3") (pinfunction "GND_E3") (pintype "input"))
      (node (ref "IC11") (pin "E4") (pinfunction "GND_E4") (pintype "input"))
      (node (ref "IC11") (pin "E5") (pinfunction "GND_E5") (pintype "input"))
      (node (ref "IC14") (pin "2") (pinfunction "GND_2") (pintype "input"))
      (node (ref "IC26") (pin "19") (pinfunction "NC_19") (pintype "passive"))
      (node (ref "IC26") (pin "36") (pinfunction "REGIN_36") (pintype "input"))
      (node (ref "IC26") (pin "37") (pinfunction "BREG_37") (pintype "output"))
      (node (ref "IC26") (pin "44") (pinfunction "NC_44") (pintype "passive"))
      (node (ref "IC4") (pin "4") (pinfunction "GND_4") (pintype "input"))
      (node (ref "IC5") (pin "2") (pinfunction "GND_2") (pintype "input"))
      (node (ref "IC5") (pin "4") (pinfunction "ADD0_4") (pintype "input"))
      (node (ref "IC6") (pin "2") (pinfunction "GND_2") (pintype "input"))
      (node (ref "IC8") (pin "EP1") (pinfunction "VSS_EP1") (pintype "input"))
      (node (ref "IC8") (pin "EP2") (pinfunction "VSS_EP2") (pintype "input"))
      (node (ref "IC8") (pin "EP3") (pinfunction "VSS_EP3") (pintype "input"))
      (node (ref "IC8") (pin "EP4") (pinfunction "VSS_EP4") (pintype "input"))
      (node (ref "IC8") (pin "EP5") (pinfunction "VSS_EP5") (pintype "input"))
      (node (ref "IC8") (pin "EP6") (pinfunction "VSS_EP6") (pintype "input"))
      (node (ref "IC8") (pin "EP7") (pinfunction "VSS_EP7") (pintype "input"))
      (node (ref "IC8") (pin "EP8") (pinfunction "VSS_EP8") (pintype "input"))
      (node (ref "IC8") (pin "EP9") (pinfunction "VSS_EP9") (pintype "input"))
      (node (ref "PTC1") (pin "1") (pinfunction "1_1") (pintype "passive"))
      (node (ref "Q1") (pin "2") (pinfunction "G1_2") (pintype "bidirectional"))
      (node (ref "Q1") (pin "4") (pinfunction "G2_4") (pintype "bidirectional"))
      (node (ref "R125") (pin "1") (pinfunction "1_1") (pintype "passive"))
      (node (ref "R13") (pin "1") (pinfunction "1_1") (pintype "passive"))
      (node (ref "R14") (pin "1") (pinfunction "1_1") (pintype "passive"))
      (node (ref "R145") (pin "1") (pinfunction "1_1") (pintype "passive"))
      (node (ref "R191") (pin "1") (pinfunction "1_1") (pintype "passive"))
      (node (ref "R192") (pin "2") (pinfunction "2_2") (pintype "passive"))
      (node (ref "R2") (pin "1") (pinfunction "1_1") (pintype "passive"))
      (node (ref "R217") (pin "1") (pinfunction "1_1") (pintype "passive"))
      (node (ref "R228") (pin "2") (pinfunction "2_2") (pintype "passive"))
      (node (ref "R26") (pin "1") (pinfunction "1_1") (pintype "passive"))
      (node (ref "R27") (pin "1") (pinfunction "1_1") (pintype "passive"))
      (node (ref "R34") (pin "1") (pinfunction "1_1") (pintype "passive"))
      (node (ref "R42") (pin "1") (pinfunction "1_1") (pintype "passive"))
      (node (ref "R86") (pin "1") (pinfunction "1_1") (pintype "passive"))
      (node (ref "R87") (pin "1") (pinfunction "1_1") (pintype "passive"))
      (node (ref "R88") (pin "1") (pinfunction "1_1") (pintype "passive"))
      (node (ref "R89") (pin "1") (pinfunction "1_1") (pintype "passive"))
      (node (ref "S1") (pin "3") (pinfunction "P_3") (pintype "passive"))
      (node (ref "S1") (pin "4") (pinfunction "P_4") (pintype "passive"))
      (node (ref "SPACER1") (pin "P$1") (pinfunction "1_P$1") (pintype "passive"))
      (node (ref "SPACER2") (pin "P$1") (pinfunction "1_P$1") (pintype "passive"))
      (node (ref "T15") (pin "2") (pinfunction "S_2") (pintype "passive"))
      (node (ref "T16") (pin "2") (pinfunction "S_2") (pintype "passive"))
      (node (ref "T17") (pin "2") (pinfunction "S_2") (pintype "passive"))
      (node (ref "T2") (pin "2") (pinfunction "S_2") (pintype "passive"))
      (node (ref "T4") (pin "2") (pinfunction "S_2") (pintype "passive"))
      (node (ref "T5") (pin "2") (pinfunction "S_2") (pintype "passive"))
      (node (ref "T6") (pin "2") (pinfunction "S_2") (pintype "passive"))
      (node (ref "T7") (pin "2") (pinfunction "S_2") (pintype "passive"))
      (node (ref "T8") (pin "1") (pinfunction "S_1") (pintype "passive"))
      (node (ref "T8") (pin "2") (pinfunction "S_2") (pintype "passive"))
      (node (ref "T8") (pin "3") (pinfunction "S_3") (pintype "passive"))
      (node (ref "TP24") (pin "P$1") (pinfunction "TP_P$1") (pintype "input"))
      (node (ref "TP6") (pin "P$1") (pinfunction "TP_P$1") (pintype "input"))
      (node (ref "TP7") (pin "P$1") (pinfunction "TP_P$1") (pintype "input"))
      (node (ref "X1") (pin "A1") (pinfunction "GND_A1") (pintype "input"))
      (node (ref "X1") (pin "A12") (pinfunction "GND_A12") (pintype "input"))
      (node (ref "X1") (pin "B1") (pinfunction "GND_B1") (pintype "input"))
      (node (ref "X1") (pin "B12") (pinfunction "GND_B12") (pintype "input"))
      (node (ref "X1") (pin "G1") (pinfunction "SHIELD_G1") (pintype "input"))
      (node (ref "X1") (pin "G2") (pinfunction "SHIELD_G2") (pintype "input"))
      (node (ref "X1") (pin "G3") (pinfunction "SHIELD_G3") (pintype "input"))
      (node (ref "X1") (pin "G4") (pinfunction "SHIELD_G4") (pintype "input"))
      (node (ref "X1") (pin "G5") (pinfunction "SHIELD_G5") (pintype "input"))
      (node (ref "X1") (pin "G6") (pinfunction "SHIELD_G6") (pintype "input"))
      (node (ref "X1") (pin "S1") (pinfunction "SHIELD_S1") (pintype "input"))
      (node (ref "X1") (pin "S10") (pinfunction "SHIELD_S10") (pintype "input"))
      (node (ref "X1") (pin "S11") (pinfunction "SHIELD_S11") (pintype "input"))
      (node (ref "X1") (pin "S12") (pinfunction "SHIELD_S12") (pintype "input"))
      (node (ref "X1") (pin "S13") (pinfunction "SHIELD_S13") (pintype "input"))
      (node (ref "X1") (pin "S14") (pinfunction "SHIELD_S14") (pintype "input"))
      (node (ref "X1") (pin "S15") (pinfunction "SHIELD_S15") (pintype "input"))
      (node (ref "X1") (pin "S16") (pinfunction "SHIELD_S16") (pintype "input"))
      (node (ref "X1") (pin "S17") (pinfunction "SHIELD_S17") (pintype "input"))
      (node (ref "X1") (pin "S18") (pinfunction "SHIELD_S18") (pintype "input"))
      (node (ref "X1") (pin "S19") (pinfunction "SHIELD_S19") (pintype "input"))
      (node (ref "X1") (pin "S2") (pinfunction "SHIELD_S2") (pintype "input"))
      (node (ref "X1") (pin "S20") (pinfunction "SHIELD_S20") (pintype "input"))
      (node (ref "X1") (pin "S21") (pinfunction "SHIELD_S21") (pintype "input"))
      (node (ref "X1") (pin "S22") (pinfunction "SHIELD_S22") (pintype "input"))
      (node (ref "X1") (pin "S23") (pinfunction "SHIELD_S23") (pintype "input"))
      (node (ref "X1") (pin "S24") (pinfunction "SHIELD_S24") (pintype "input"))
      (node (ref "X1") (pin "S25") (pinfunction "SHIELD_S25") (pintype "input"))
      (node (ref "X1") (pin "S26") (pinfunction "SHIELD_S26") (pintype "input"))
      (node (ref "X1") (pin "S27") (pinfunction "SHIELD_S27") (pintype "input"))
      (node (ref "X1") (pin "S28") (pinfunction "SHIELD_S28") (pintype "input"))
      (node (ref "X1") (pin "S29") (pinfunction "SHIELD_S29") (pintype "input"))
      (node (ref "X1") (pin "S3") (pinfunction "SHIELD_S3") (pintype "input"))
      (node (ref "X1") (pin "S30") (pinfunction "SHIELD_S30") (pintype "input"))
      (node (ref "X1") (pin "S31") (pinfunction "SHIELD_S31") (pintype "input"))
      (node (ref "X1") (pin "S32") (pinfunction "SHIELD_S32") (pintype "input"))
      (node (ref "X1") (pin "S33") (pinfunction "SHIELD_S33") (pintype "input"))
      (node (ref "X1") (pin "S34") (pinfunction "SHIELD_S34") (pintype "input"))
      (node (ref "X1") (pin "S4") (pinfunction "SHIELD_S4") (pintype "input"))
      (node (ref "X1") (pin "S5") (pinfunction "SHIELD_S5") (pintype "input"))
      (node (ref "X1") (pin "S6") (pinfunction "SHIELD_S6") (pintype "input"))
      (node (ref "X1") (pin "S7") (pinfunction "SHIELD_S7") (pintype "input"))
      (node (ref "X1") (pin "S8") (pinfunction "SHIELD_S8") (pintype "input"))
      (node (ref "X1") (pin "S9") (pinfunction "SHIELD_S9") (pintype "input"))
      (node (ref "X13") (pin "2") (pinfunction "2_2") (pintype "passive"))
      (node (ref "X13") (pin "3") (pinfunction "3_3") (pintype "passive"))
      (node (ref "X13") (pin "4") (pinfunction "4_4") (pintype "passive"))
      (node (ref "X13") (pin "8") (pinfunction "8_8") (pintype "passive"))
      (node (ref "X14") (pin "S1") (pinfunction "S_S1") (pintype "passive"))
      (node (ref "X14") (pin "S2") (pinfunction "S_S2") (pintype "passive"))
      (node (ref "X2") (pin "2") (pinfunction "2_2") (pintype "passive"))
      (node (ref "X2") (pin "S1") (pinfunction "S_S1") (pintype "passive"))
      (node (ref "X2") (pin "S2") (pinfunction "S_S2") (pintype "passive"))
      (node (ref "X21") (pin "5") (pinfunction "GND_5") (pintype "input"))
      (node (ref "X6") (pin "5") (pinfunction "GND_5") (pintype "input"))
    )
    (net (code "24") (name "Net-(C13-Pad1)") (class "Default")
      (node (ref "C13") (pin "1") (pinfunction "1_1") (pintype "passive"))
      (node (ref "C36") (pin "1") (pinfunction "1_1") (pintype "passive"))
      (node (ref "L2") (pin "NODOT") (pinfunction "NODOT_NODOT") (pintype "passive"))
      (node (ref "R35") (pin "2") (pinfunction "2_2") (pintype "passive"))
      (node (ref "R37") (pin "1") (pinfunction "1_1") (pintype "passive"))
      (node (ref "R6") (pin "2") (pinfunction "2_2") (pintype "passive"))
    )
    (net (code "25") (name "Net-(C14-Pad1)") (class "Default")
      (node (ref "C14") (pin "1") (pinfunction "1_1") (pintype "passive"))
      (node (ref "C50") (pin "1") (pinfunction "1_1") (pintype "passive"))
    )
    (net (code "26") (name "Net-(C39-Pad1)") (class "Default")
      (node (ref "C39") (pin "1") (pinfunction "1_1") (pintype "passive"))
      (node (ref "R10") (pin "1") (pinfunction "1_1") (pintype "passive"))
      (node (ref "T1") (pin "1") (pinfunction "S_1") (pintype "passive"))
      (node (ref "T1") (pin "2") (pinfunction "S_2") (pintype "passive"))
      (node (ref "T1") (pin "3") (pinfunction "S_3") (pintype "passive"))
      (node (ref "T3") (pin "1") (pinfunction "S_1") (pintype "passive"))
      (node (ref "T3") (pin "2") (pinfunction "S_2") (pintype "passive"))
      (node (ref "T3") (pin "3") (pinfunction "S_3") (pintype "passive"))
    )
    (net (code "27") (name "Net-(C41-Pad1)") (class "Default")
      (node (ref "C41") (pin "1") (pinfunction "1_1") (pintype "passive"))
      (node (ref "C61") (pin "2") (pinfunction "2_2") (pintype "passive"))
    )
    (net (code "28") (name "Net-(C65-Pad1)") (class "Default")
      (node (ref "C65") (pin "1") (pinfunction "1_1") (pintype "passive"))
      (node (ref "R62") (pin "1") (pinfunction "1_1") (pintype "passive"))
      (node (ref "R90") (pin "2") (pinfunction "2_2") (pintype "passive"))
    )
    (net (code "29") (name "Net-(D2-C_BLUE)") (class "Default")
      (node (ref "D2") (pin "4") (pinfunction "C_BLUE_4") (pintype "passive"))
      (node (ref "R65") (pin "2") (pinfunction "2_2") (pintype "passive"))
    )
    (net (code "30") (name "Net-(D2-C_GREEN)") (class "Default")
      (node (ref "D2") (pin "3") (pinfunction "C_GREEN_3") (pintype "passive"))
      (node (ref "R64") (pin "2") (pinfunction "2_2") (pintype "passive"))
    )
    (net (code "31") (name "Net-(D2-C_RED)") (class "Default")
      (node (ref "D2") (pin "2") (pinfunction "C_RED_2") (pintype "passive"))
      (node (ref "R63") (pin "2") (pinfunction "2_2") (pintype "passive"))
    )
    (net (code "32") (name "Net-(D3-C_BLUE)") (class "Default")
      (node (ref "D3") (pin "4") (pinfunction "C_BLUE_4") (pintype "passive"))
      (node (ref "R71") (pin "2") (pinfunction "2_2") (pintype "passive"))
    )
    (net (code "33") (name "Net-(D3-C_GREEN)") (class "Default")
      (node (ref "D3") (pin "3") (pinfunction "C_GREEN_3") (pintype "passive"))
      (node (ref "R70") (pin "2") (pinfunction "2_2") (pintype "passive"))
    )
    (net (code "34") (name "Net-(D3-C_RED)") (class "Default")
      (node (ref "D3") (pin "2") (pinfunction "C_RED_2") (pintype "passive"))
      (node (ref "R66") (pin "2") (pinfunction "2_2") (pintype "passive"))
    )
    (net (code "35") (name "Net-(D5-PadC)") (class "Default")
      (node (ref "D5") (pin "C") (pinfunction "C_C") (pintype "passive"))
      (node (ref "D8") (pin "C") (pinfunction "C_C") (pintype "passive"))
      (node (ref "R41") (pin "2") (pinfunction "2_2") (pintype "passive"))
    )
    (net (code "36") (name "Net-(D9-C_BLUE)") (class "Default")
      (node (ref "D9") (pin "4") (pinfunction "C_BLUE_4") (pintype "passive"))
      (node (ref "R74") (pin "2") (pinfunction "2_2") (pintype "passive"))
    )
    (net (code "37") (name "Net-(D9-C_GREEN)") (class "Default")
      (node (ref "D9") (pin "3") (pinfunction "C_GREEN_3") (pintype "passive"))
      (node (ref "R73") (pin "2") (pinfunction "2_2") (pintype "passive"))
    )
    (net (code "38") (name "Net-(D9-C_RED)") (class "Default")
      (node (ref "D9") (pin "2") (pinfunction "C_RED_2") (pintype "passive"))
      (node (ref "R72") (pin "2") (pinfunction "2_2") (pintype "passive"))
    )
    (net (code "39") (name "Net-(D10-PadC)") (class "Default")
      (node (ref "D10") (pin "C") (pinfunction "C_C") (pintype "passive"))
      (node (ref "R189") (pin "1") (pinfunction "1_1") (pintype "passive"))
    )
    (net (code "40") (name "Net-(D11-C)") (class "Default")
      (node (ref "D11") (pin "3") (pinfunction "C_3") (pintype "passive"))
      (node (ref "R121") (pin "1") (pinfunction "1_1") (pintype "passive"))
    )
    (net (code "41") (name "Net-(D12-C_BLUE)") (class "Default")
      (node (ref "D12") (pin "4") (pinfunction "C_BLUE_4") (pintype "passive"))
      (node (ref "R77") (pin "2") (pinfunction "2_2") (pintype "passive"))
    )
    (net (code "42") (name "Net-(D12-C_GREEN)") (class "Default")
      (node (ref "D12") (pin "3") (pinfunction "C_GREEN_3") (pintype "passive"))
      (node (ref "R76") (pin "2") (pinfunction "2_2") (pintype "passive"))
    )
    (net (code "43") (name "Net-(D12-C_RED)") (class "Default")
      (node (ref "D12") (pin "2") (pinfunction "C_RED_2") (pintype "passive"))
      (node (ref "R75") (pin "2") (pinfunction "2_2") (pintype "passive"))
    )
    (net (code "44") (name "Net-(D13-C_BLUE)") (class "Default")
      (node (ref "D13") (pin "4") (pinfunction "C_BLUE_4") (pintype "passive"))
      (node (ref "R101") (pin "2") (pinfunction "2_2") (pintype "passive"))
    )
    (net (code "45") (name "Net-(D13-C_GREEN)") (class "Default")
      (node (ref "D13") (pin "3") (pinfunction "C_GREEN_3") (pintype "passive"))
      (node (ref "R100") (pin "2") (pinfunction "2_2") (pintype "passive"))
    )
    (net (code "46") (name "Net-(D13-C_RED)") (class "Default")
      (node (ref "D13") (pin "2") (pinfunction "C_RED_2") (pintype "passive"))
      (node (ref "R78") (pin "2") (pinfunction "2_2") (pintype "passive"))
    )
    (net (code "47") (name "Net-(D14-C_BLUE)") (class "Default")
      (node (ref "D14") (pin "4") (pinfunction "C_BLUE_4") (pintype "passive"))
      (node (ref "R104") (pin "2") (pinfunction "2_2") (pintype "passive"))
    )
    (net (code "48") (name "Net-(D14-C_GREEN)") (class "Default")
      (node (ref "D14") (pin "3") (pinfunction "C_GREEN_3") (pintype "passive"))
      (node (ref "R103") (pin "2") (pinfunction "2_2") (pintype "passive"))
    )
    (net (code "49") (name "Net-(D14-C_RED)") (class "Default")
      (node (ref "D14") (pin "2") (pinfunction "C_RED_2") (pintype "passive"))
      (node (ref "R102") (pin "2") (pinfunction "2_2") (pintype "passive"))
    )
    (net (code "50") (name "Net-(D15-C_BLUE)") (class "Default")
      (node (ref "D15") (pin "4") (pinfunction "C_BLUE_4") (pintype "passive"))
      (node (ref "R107") (pin "2") (pinfunction "2_2") (pintype "passive"))
    )
    (net (code "51") (name "Net-(D15-C_GREEN)") (class "Default")
      (node (ref "D15") (pin "3") (pinfunction "C_GREEN_3") (pintype "passive"))
      (node (ref "R106") (pin "2") (pinfunction "2_2") (pintype "passive"))
    )
    (net (code "52") (name "Net-(D15-C_RED)") (class "Default")
      (node (ref "D15") (pin "2") (pinfunction "C_RED_2") (pintype "passive"))
      (node (ref "R105") (pin "2") (pinfunction "2_2") (pintype "passive"))
    )
    (net (code "53") (name "Net-(D16-C_BLUE)") (class "Default")
      (node (ref "D16") (pin "4") (pinfunction "C_BLUE_4") (pintype "passive"))
      (node (ref "R110") (pin "2") (pinfunction "2_2") (pintype "passive"))
    )
    (net (code "54") (name "Net-(D16-C_GREEN)") (class "Default")
      (node (ref "D16") (pin "3") (pinfunction "C_GREEN_3") (pintype "passive"))
      (node (ref "R109") (pin "2") (pinfunction "2_2") (pintype "passive"))
    )
    (net (code "55") (name "Net-(D16-C_RED)") (class "Default")
      (node (ref "D16") (pin "2") (pinfunction "C_RED_2") (pintype "passive"))
      (node (ref "R108") (pin "2") (pinfunction "2_2") (pintype "passive"))
    )
    (net (code "56") (name "Net-(D17-C_BLUE)") (class "Default")
      (node (ref "D17") (pin "4") (pinfunction "C_BLUE_4") (pintype "passive"))
      (node (ref "R113") (pin "2") (pinfunction "2_2") (pintype "passive"))
    )
    (net (code "57") (name "Net-(D17-C_GREEN)") (class "Default")
      (node (ref "D17") (pin "3") (pinfunction "C_GREEN_3") (pintype "passive"))
      (node (ref "R112") (pin "2") (pinfunction "2_2") (pintype "passive"))
    )
    (net (code "58") (name "Net-(D17-C_RED)") (class "Default")
      (node (ref "D17") (pin "2") (pinfunction "C_RED_2") (pintype "passive"))
      (node (ref "R111") (pin "2") (pinfunction "2_2") (pintype "passive"))
    )
    (net (code "59") (name "Net-(D18-C_BLUE)") (class "Default")
      (node (ref "D18") (pin "4") (pinfunction "C_BLUE_4") (pintype "passive"))
      (node (ref "R116") (pin "2") (pinfunction "2_2") (pintype "passive"))
    )
    (net (code "60") (name "Net-(D18-C_GREEN)") (class "Default")
      (node (ref "D18") (pin "3") (pinfunction "C_GREEN_3") (pintype "passive"))
      (node (ref "R115") (pin "2") (pinfunction "2_2") (pintype "passive"))
    )
    (net (code "61") (name "Net-(D18-C_RED)") (class "Default")
      (node (ref "D18") (pin "2") (pinfunction "C_RED_2") (pintype "passive"))
      (node (ref "R114") (pin "2") (pinfunction "2_2") (pintype "passive"))
    )
    (net (code "62") (name "Net-(D19-PadC)") (class "Default")
      (node (ref "D19") (pin "C") (pinfunction "C_C") (pintype "passive"))
      (node (ref "D6") (pin "C") (pinfunction "C_C") (pintype "passive"))
      (node (ref "D7") (pin "C") (pinfunction "C_C") (pintype "passive"))
      (node (ref "R83") (pin "1") (pinfunction "1_1") (pintype "passive"))
    )
    (net (code "63") (name "Net-(D20-A)") (class "Default")
      (node (ref "D20") (pin "1") (pinfunction "A_1") (pintype "passive"))
      (node (ref "R56") (pin "1") (pinfunction "1_1") (pintype "passive"))
    )
    (net (code "64") (name "Net-(F2-F1)") (class "Default")
      (node (ref "F1") (pin "2") (pinfunction "2_2") (pintype "passive"))
      (node (ref "F2") (pin "T1") (pinfunction "F1_T1") (pintype "passive"))
    )
    (net (code "65") (name "Net-(F2-H)") (class "Default")
      (node (ref "F2") (pin "T2") (pinfunction "H_T2") (pintype "passive"))
      (node (ref "R147") (pin "2") (pinfunction "2_2") (pintype "passive"))
      (node (ref "R148") (pin "2") (pinfunction "2_2") (pintype "passive"))
    )
    (net (code "66") (name "Net-(IC1-CD)") (class "Default")
      (node (ref "C56") (pin "1") (pinfunction "1_1") (pintype "passive"))
      (node (ref "IC1") (pin "7") (pinfunction "CD_7") (pintype "bidirectional"))
      (node (ref "TP39") (pin "P$1") (pinfunction "TP_P$1") (pintype "input"))
    )
    (net (code "67") (name "Net-(IC1-OUT)") (class "Default")
      (node (ref "IC1") (pin "8") (pinfunction "OUT_8") (pintype "output"))
      (node (ref "R30") (pin "1") (pinfunction "1_1") (pintype "passive"))
      (node (ref "R48") (pin "2") (pinfunction "2_2") (pintype "passive"))
    )
    (net (code "68") (name "Net-(IC1-V1)") (class "Default")
      (node (ref "C45") (pin "2") (pinfunction "2_2") (pintype "passive"))
      (node (ref "C46") (pin "1") (pinfunction "1_1") (pintype "passive"))
      (node (ref "IC1") (pin "5") (pinfunction "V1_5") (pintype "input"))
      (node (ref "R21") (pin "2") (pinfunction "2_2") (pintype "passive"))
    )
    (net (code "69") (name "Net-(IC1-V2)") (class "Default")
      (node (ref "C42") (pin "2") (pinfunction "2_2") (pintype "passive"))
      (node (ref "C45") (pin "1") (pinfunction "1_1") (pintype "passive"))
      (node (ref "IC1") (pin "4") (pinfunction "V2_4") (pintype "input"))
      (node (ref "R20") (pin "2") (pinfunction "2_2") (pintype "passive"))
    )
    (net (code "70") (name "Net-(IC1-V3)") (class "Default")
      (node (ref "C37") (pin "2") (pinfunction "2_2") (pintype "passive"))
      (node (ref "C42") (pin "1") (pinfunction "1_1") (pintype "passive"))
      (node (ref "IC1") (pin "3") (pinfunction "V3_3") (pintype "input"))
      (node (ref "R17") (pin "2") (pinfunction "2_2") (pintype "passive"))
    )
    (net (code "71") (name "Net-(IC1-V4)") (class "Default")
      (node (ref "C37") (pin "1") (pinfunction "1_1") (pintype "passive"))
      (node (ref "IC1") (pin "2") (pinfunction "V4_2") (pintype "input"))
      (node (ref "R15") (pin "2") (pinfunction "2_2") (pintype "passive"))
    )
    (net (code "72") (name "Net-(IC1-VDD)") (class "Default")
      (node (ref "C49") (pin "1") (pinfunction "1_1") (pintype "passive"))
      (node (ref "IC1") (pin "1") (pinfunction "VDD_1") (pintype "input"))
      (node (ref "R25") (pin "2") (pinfunction "2_2") (pintype "passive"))
    )
    (net (code "73") (name "Net-(IC4-A0)") (class "Default")
      (node (ref "C8") (pin "1") (pinfunction "1_1") (pintype "passive"))
      (node (ref "IC4") (pin "5") (pinfunction "A2_5") (pintype "input"))
      (node (ref "IC4") (pin "6") (pinfunction "A1_6") (pintype "input"))
      (node (ref "IC4") (pin "7") (pinfunction "A0_7") (pintype "input"))
      (node (ref "IC4") (pin "8") (pinfunction "VCC_8") (pintype "input"))
      (node (ref "IC5") (pin "5") (pinfunction "V+_5") (pintype "input"))
      (node (ref "R29") (pin "2") (pinfunction "2_2") (pintype "passive"))
    )
    (net (code "74") (name "Net-(IC4-SCL)") (class "Default")
      (node (ref "IC4") (pin "2") (pinfunction "SCL_2") (pintype "input"))
      (node (ref "IC5") (pin "1") (pinfunction "SCL_1") (pintype "input"))
      (node (ref "R92") (pin "1") (pinfunction "1_1") (pintype "passive"))
    )
    (net (code "75") (name "Net-(IC4-SDA)") (class "Default")
      (node (ref "IC4") (pin "1") (pinfunction "SDA_1") (pintype "open_collector"))
      (node (ref "IC5") (pin "6") (pinfunction "SDA_6") (pintype "open_collector"))
      (node (ref "R19") (pin "1") (pinfunction "1_1") (pintype "passive"))
    )
    (net (code "76") (name "Net-(IC8A-OSC32_IN{slash}PC14)") (class "Default")
      (node (ref "C295") (pin "1") (pinfunction "1_1") (pintype "passive"))
      (node (ref "IC8") (pin "3") (pinfunction "OSC32_IN/PC14_3") (pintype "bidirectional"))
      (node (ref "Q2") (pin "1") (pinfunction "1_1") (pintype "passive"))
    )
    (net (code "77") (name "Net-(IC8A-OSC32_OUT{slash}PC15)") (class "Default")
      (node (ref "C296") (pin "1") (pinfunction "1_1") (pintype "passive"))
      (node (ref "IC8") (pin "4") (pinfunction "OSC32_OUT/PC15_4") (pintype "bidirectional"))
      (node (ref "Q2") (pin "2") (pinfunction "2_2") (pintype "passive"))
    )
    (net (code "78") (name "Net-(IC8A-OSC_IN{slash}PF0)") (class "Default")
      (node (ref "C102") (pin "1") (pinfunction "1_1") (pintype "passive"))
      (node (ref "IC8") (pin "5") (pinfunction "OSC_IN/PF0_5") (pintype "bidirectional"))
      (node (ref "Q1") (pin "1") (pinfunction "C1_1") (pintype "bidirectional"))
    )
    (net (code "79") (name "Net-(IC8A-OSC_OUT{slash}PF1)") (class "Default")
      (node (ref "IC8") (pin "6") (pinfunction "OSC_OUT/PF1_6") (pintype "bidirectional"))
      (node (ref "R296") (pin "2") (pinfunction "2_2") (pintype "passive"))
    )
    (net (code "80") (name "Net-(IC8A-VBAT)") (class "Default")
      (node (ref "C10") (pin "1") (pinfunction "1_1") (pintype "passive"))
      (node (ref "C11") (pin "1") (pinfunction "1_1") (pintype "passive"))
      (node (ref "C12") (pin "1") (pinfunction "1_1") (pintype "passive"))
      (node (ref "C47") (pin "1") (pinfunction "1_1") (pintype "passive"))
      (node (ref "C6") (pin "1") (pinfunction "1_1") (pintype "passive"))
      (node (ref "IC8") (pin "1") (pinfunction "VBAT_1") (pintype "input"))
      (node (ref "IC8") (pin "20") (pinfunction "VREF+/VREFBUF_OUT_20") (pintype "input"))
      (node (ref "IC8") (pin "21") (pinfunction "VDDA_21") (pintype "input"))
      (node (ref "IC8") (pin "23") (pinfunction "VDD1_23") (pintype "input"))
      (node (ref "IC8") (pin "35") (pinfunction "VDD2_35") (pintype "input"))
      (node (ref "IC8") (pin "48") (pinfunction "VDD3_48") (pintype "input"))
      (node (ref "R18") (pin "1") (pinfunction "1_1") (pintype "passive"))
    )
    (net (code "81") (name "Net-(IC8B-PA7)") (class "Default")
      (node (ref "IC8") (pin "15") (pinfunction "PA7_15") (pintype "bidirectional"))
      (node (ref "R46") (pin "2") (pinfunction "2_2") (pintype "passive"))
    )
    (net (code "82") (name "Net-(IC8B-PA8)") (class "Default")
      (node (ref "IC8") (pin "30") (pinfunction "PA8_30") (pintype "bidirectional"))
      (node (ref "R118") (pin "2") (pinfunction "2_2") (pintype "passive"))
    )
    (net (code "83") (name "Net-(IC8B-PA11)") (class "Default")
      (node (ref "IC8") (pin "33") (pinfunction "PA11_33") (pintype "bidirectional"))
      (node (ref "R122") (pin "2") (pinfunction "2_2") (pintype "passive"))
    )
    (net (code "84") (name "Net-(IC8B-PA12)") (class "Default")
      (node (ref "IC8") (pin "34") (pinfunction "PA12_34") (pintype "bidirectional"))
      (node (ref "R121") (pin "2") (pinfunction "2_2") (pintype "passive"))
    )
    (net (code "85") (name "Net-(IC8C-PB0)") (class "Default")
      (node (ref "IC8") (pin "17") (pinfunction "PB0_17") (pintype "bidirectional"))
      (node (ref "R47") (pin "2") (pinfunction "2_2") (pintype "passive"))
    )
    (net (code "86") (name "Net-(IC8C-PB1)") (class "Default")
      (node (ref "IC8") (pin "18") (pinfunction "PB1_18") (pintype "bidirectional"))
      (node (ref "R57") (pin "2") (pinfunction "2_2") (pintype "passive"))
    )
    (net (code "87") (name "Net-(IC8C-PB5)") (class "Default")
      (node (ref "IC8") (pin "43") (pinfunction "PB5_43") (pintype "bidirectional"))
      (node (ref "R142") (pin "2") (pinfunction "2_2") (pintype "passive"))
    )
    (net (code "88") (name "Net-(IC8C-PB8)") (class "Default")
      (node (ref "IC8") (pin "46") (pinfunction "PB8_46") (pintype "bidirectional"))
      (node (ref "R145") (pin "2") (pinfunction "2_2") (pintype "passive"))
    )
    (net (code "89") (name "Net-(IC8C-PB9)") (class "Default")
      (node (ref "IC8") (pin "47") (pinfunction "PB9_47") (pintype "bidirectional"))
      (node (ref "R11") (pin "2") (pinfunction "2_2") (pintype "passive"))
    )
    (net (code "90") (name "Net-(IC8C-PB10)") (class "Default")
      (node (ref "IC8") (pin "22") (pinfunction "PB10_22") (pintype "bidirectional"))
      (node (ref "R176") (pin "2") (pinfunction "2_2") (pintype "passive"))
    )
    (net (code "91") (name "Net-(IC8C-PB11)") (class "Default")
      (node (ref "IC8") (pin "24") (pinfunction "PB11_24") (pintype "bidirectional"))
      (node (ref "R177") (pin "2") (pinfunction "2_2") (pintype "passive"))
    )
    (net (code "92") (name "Net-(IC8C-PB13)") (class "Default")
      (node (ref "IC8") (pin "26") (pinfunction "PB13_26") (pintype "bidirectional"))
      (node (ref "R117") (pin "2") (pinfunction "2_2") (pintype "passive"))
    )
    (net (code "93") (name "Net-(IC8D-PC6)") (class "Default")
      (node (ref "IC8") (pin "29") (pinfunction "PC6_29") (pintype "bidirectional"))
      (node (ref "R144") (pin "2") (pinfunction "2_2") (pintype "passive"))
    )
    (net (code "94") (name "Net-(IC8D-PC10)") (class "Default")
      (node (ref "IC8") (pin "39") (pinfunction "PC10_39") (pintype "bidirectional"))
      (node (ref "R143") (pin "2") (pinfunction "2_2") (pintype "passive"))
    )
    (net (code "95") (name "Net-(IC10-IN)") (class "Default")
      (node (ref "C53") (pin "1") (pinfunction "1_1") (pintype "passive"))
      (node (ref "IC10") (pin "6") (pinfunction "IN_6") (pintype "input"))
      (node (ref "R83") (pin "2") (pinfunction "2_2") (pintype "passive"))
    )
    (net (code "96") (name "Net-(IC10-OUT)") (class "Default")
      (node (ref "C52") (pin "1") (pinfunction "1_1") (pintype "passive"))
      (node (ref "IC10") (pin "1") (pinfunction "OUT_1") (pintype "output"))
      (node (ref "R82") (pin "1") (pinfunction "1_1") (pintype "passive"))
    )
    (net (code "97") (name "Net-(IC11-ACDET)") (class "Default")
      (node (ref "IC11") (pin "6") (pinfunction "ACDET_6") (pintype "input"))
      (node (ref "R24") (pin "1") (pinfunction "1_1") (pintype "passive"))
      (node (ref "R26") (pin "2") (pinfunction "2_2") (pintype "passive"))
    )
    (net (code "98") (name "Net-(IC11-ACDRV)") (class "Default")
      (node (ref "IC11") (pin "4") (pinfunction "ACDRV_4") (pintype "output"))
      (node (ref "R22") (pin "2") (pinfunction "2_2") (pintype "passive"))
    )
    (net (code "99") (name "Net-(IC11-ACN)") (class "Default")
      (node (ref "C17") (pin "2") (pinfunction "2_2") (pintype "passive"))
      (node (ref "C18") (pin "2") (pinfunction "2_2") (pintype "passive"))
      (node (ref "C20") (pin "1") (pinfunction "1_1") (pintype "passive"))
      (node (ref "C22") (pin "1") (pinfunction "1_1") (pintype "passive"))
      (node (ref "C23") (pin "1") (pinfunction "1_1") (pintype "passive"))
      (node (ref "C24") (pin "1") (pinfunction "1_1") (pintype "passive"))
      (node (ref "C25") (pin "1") (pinfunction "1_1") (pintype "passive"))
      (node (ref "C26") (pin "1") (pinfunction "1_1") (pintype "passive"))
      (node (ref "C27") (pin "1") (pinfunction "1_1") (pintype "passive"))
      (node (ref "IC11") (pin "1") (pinfunction "ACN_1") (pintype "input"))
      (node (ref "R7") (pin "2") (pinfunction "2_2") (pintype "passive"))
      (node (ref "T9") (pin "5") (pinfunction "D_5") (pintype "passive"))
      (node (ref "T9") (pin "P$1") (pinfunction "D_P$1") (pintype "passive"))
      (node (ref "T9") (pin "P$4") (pinfunction "D_P$4") (pintype "passive"))
      (node (ref "T9") (pin "P$5") (pinfunction "D_P$5") (pintype "passive"))
      (node (ref "T9") (pin "P$6") (pinfunction "D_P$6") (pintype "passive"))
      (node (ref "T9") (pin "P$7") (pinfunction "D_P$7") (pintype "passive"))
    )
    (net (code "100") (name "Net-(IC11-ACOK)") (class "Default")
      (node (ref "IC11") (pin "5") (pinfunction "ACOK_5") (pintype "open_collector"))
      (node (ref "TP38") (pin "P$1") (pinfunction "TP_P$1") (pintype "input"))
    )
    (net (code "101") (name "Net-(IC11-ACP)") (class "Default")
      (node (ref "C17") (pin "1") (pinfunction "1_1") (pintype "passive"))
      (node (ref "C38") (pin "2") (pinfunction "2_2") (pintype "passive"))
      (node (ref "IC11") (pin "2") (pinfunction "ACP_2") (pintype "input"))
      (node (ref "R7") (pin "1") (pinfunction "1_1") (pintype "passive"))
      (node (ref "T1") (pin "5") (pinfunction "D_5") (pintype "passive"))
    )
    (net (code "102") (name "Net-(IC11-BATSRC)") (class "Default")
      (node (ref "IC11") (pin "17") (pinfunction "BATSRC_17") (pintype "input"))
      (node (ref "R6") (pin "1") (pinfunction "1_1") (pintype "passive"))
    )
    (net (code "103") (name "Net-(IC11-BTST)") (class "Default")
      (node (ref "C14") (pin "2") (pinfunction "2_2") (pintype "passive"))
      (node (ref "IC11") (pin "25") (pinfunction "BTST_25") (pintype "input"))
    )
    (net (code "104") (name "Net-(IC11-CMSRC)") (class "Default")
      (node (ref "IC11") (pin "3") (pinfunction "CMSRC_3") (pintype "input"))
      (node (ref "R10") (pin "2") (pinfunction "2_2") (pintype "passive"))
    )
    (net (code "105") (name "Net-(IC11-HIDRV)") (class "Default")
      (node (ref "IC11") (pin "26") (pinfunction "HIDRV_26") (pintype "output"))
      (node (ref "R5") (pin "1") (pinfunction "1_1") (pintype "passive"))
    )
    (net (code "106") (name "Net-(IC11-ILIM)") (class "Default")
      (node (ref "IC11") (pin "21") (pinfunction "ILIM_21") (pintype "input"))
      (node (ref "R28") (pin "2") (pinfunction "2_2") (pintype "passive"))
      (node (ref "R42") (pin "2") (pinfunction "2_2") (pintype "passive"))
    )
    (net (code "107") (name "Net-(IC11-LODRV)") (class "Default")
      (node (ref "IC11") (pin "23") (pinfunction "LODRV_23") (pintype "output"))
      (node (ref "R4") (pin "1") (pinfunction "1_1") (pintype "passive"))
    )
    (net (code "108") (name "Net-(IC11-PHASE)") (class "Default")
      (node (ref "C50") (pin "2") (pinfunction "2_2") (pintype "passive"))
      (node (ref "IC11") (pin "27") (pinfunction "PHASE_27") (pintype "input"))
      (node (ref "L2") (pin "DOT") (pinfunction "DOT_DOT") (pintype "passive"))
      (node (ref "T8") (pin "5") (pinfunction "D_5") (pintype "passive"))
      (node (ref "T8") (pin "P$1") (pinfunction "D_P$1") (pintype "passive"))
      (node (ref "T8") (pin "P$2") (pinfunction "D_P$2") (pintype "passive"))
      (node (ref "T8") (pin "P$3") (pinfunction "D_P$3") (pintype "passive"))
      (node (ref "T8") (pin "P$4") (pinfunction "D_P$4") (pintype "passive"))
      (node (ref "T8") (pin "P$5") (pinfunction "D_P$5") (pintype "passive"))
      (node (ref "T8") (pin "P$6") (pinfunction "D_P$6") (pintype "passive"))
      (node (ref "T8") (pin "P$7") (pinfunction "D_P$7") (pintype "passive"))
      (node (ref "T9") (pin "1") (pinfunction "S_1") (pintype "passive"))
      (node (ref "T9") (pin "2") (pinfunction "S_2") (pintype "passive"))
      (node (ref "T9") (pin "3") (pinfunction "S_3") (pintype "passive"))
    )
    (net (code "109") (name "Net-(IC11-REGN)") (class "Default")
      (node (ref "C43") (pin "1") (pinfunction "1_1") (pintype "passive"))
      (node (ref "IC11") (pin "24") (pinfunction "REGN_24") (pintype "output"))
    )
    (net (code "110") (name "Net-(IC11-SCL)") (class "Default")
      (node (ref "IC11") (pin "12") (pinfunction "SCL_12") (pintype "open_collector"))
      (node (ref "R44") (pin "2") (pinfunction "2_2") (pintype "passive"))
    )
    (net (code "111") (name "Net-(IC11-SDA)") (class "Default")
      (node (ref "IC11") (pin "11") (pinfunction "SDA_11") (pintype "open_collector"))
      (node (ref "R45") (pin "2") (pinfunction "2_2") (pintype "passive"))
    )
    (net (code "112") (name "Net-(IC11-SRN)") (class "Default")
      (node (ref "IC11") (pin "19") (pinfunction "SRN_19") (pintype "input"))
      (node (ref "R36") (pin "1") (pinfunction "1_1") (pintype "passive"))
    )
    (net (code "113") (name "Net-(IC11-SRP)") (class "Default")
      (node (ref "IC11") (pin "20") (pinfunction "SRP_20") (pintype "input"))
      (node (ref "R35") (pin "1") (pinfunction "1_1") (pintype "passive"))
    )
    (net (code "114") (name "Net-(IC11-VCC)") (class "Default")
      (node (ref "C44") (pin "1") (pinfunction "1_1") (pintype "passive"))
      (node (ref "IC11") (pin "28") (pinfunction "VCC_28") (pintype "input"))
      (node (ref "R41") (pin "1") (pinfunction "1_1") (pintype "passive"))
    )
    (net (code "115") (name "Net-(IC11-~{BATPRES})") (class "Default")
      (node (ref "IC11") (pin "15") (pinfunction "~{BATPRES}_15") (pintype "input"))
      (node (ref "R27") (pin "2") (pinfunction "2_2") (pintype "passive"))
    )
    (net (code "116") (name "Net-(IC11-~{PROCHOT})") (class "Default")
      (node (ref "IC11") (pin "10") (pinfunction "~{PROCHOT}_10") (pintype "open_collector"))
      (node (ref "TP36") (pin "P$1") (pinfunction "TP_P$1") (pintype "input"))
    )
    (net (code "117") (name "Net-(IC11-~{TB_STAT})") (class "Default")
      (node (ref "IC11") (pin "16") (pinfunction "~{TB_STAT}_16") (pintype "open_collector"))
      (node (ref "TP37") (pin "P$1") (pinfunction "TP_P$1") (pintype "input"))
    )
    (net (code "118") (name "Net-(IC14-I{slash}O1)") (class "Default")
      (node (ref "IC14") (pin "1") (pinfunction "I/O1_1") (pintype "passive"))
      (node (ref "R60") (pin "2") (pinfunction "2_2") (pintype "passive"))
      (node (ref "TP33") (pin "P$1") (pinfunction "TP_P$1") (pintype "input"))
      (node (ref "X13") (pin "1") (pinfunction "1_1") (pintype "passive"))
    )
    (net (code "119") (name "Net-(IC14-I{slash}O2)") (class "Default")
      (node (ref "IC14") (pin "3") (pinfunction "I/O2_3") (pintype "passive"))
      (node (ref "R61") (pin "2") (pinfunction "2_2") (pintype "passive"))
      (node (ref "TP40") (pin "P$1") (pinfunction "TP_P$1") (pintype "input"))
      (node (ref "X13") (pin "9") (pinfunction "9_9") (pintype "passive"))
    )
    (net (code "120") (name "Net-(IC14-I{slash}O3)") (class "Default")
      (node (ref "IC14") (pin "4") (pinfunction "I/O3_4") (pintype "passive"))
      (node (ref "R62") (pin "2") (pinfunction "2_2") (pintype "passive"))
      (node (ref "TP18") (pin "P$1") (pinfunction "TP_P$1") (pintype "input"))
      (node (ref "X13") (pin "10") (pinfunction "10_10") (pintype "passive"))
    )
    (net (code "121") (name "Net-(IC26A-DFETOFF)") (class "Default")
      (node (ref "IC26") (pin "30") (pinfunction "DFETOFF_30") (pintype "bidirectional"))
      (node (ref "R59") (pin "1") (pinfunction "1_1") (pintype "passive"))
    )
    (net (code "122") (name "Net-(IC26A-FUSE)") (class "Default")
      (node (ref "IC26") (pin "38") (pinfunction "FUSE_38") (pintype "bidirectional"))
      (node (ref "R49") (pin "2") (pinfunction "2_2") (pintype "passive"))
      (node (ref "R50") (pin "2") (pinfunction "2_2") (pintype "passive"))
    )
    (net (code "123") (name "Net-(IC26A-LD)") (class "Default")
      (node (ref "IC26") (pin "41") (pinfunction "LD_41") (pintype "bidirectional"))
      (node (ref "R227") (pin "1") (pinfunction "1_1") (pintype "passive"))
    )
    (net (code "124") (name "Net-(IC26A-PACK)") (class "Default")
      (node (ref "IC26") (pin "42") (pinfunction "PACK_42") (pintype "input"))
      (node (ref "R218") (pin "1") (pinfunction "1_1") (pintype "passive"))
    )
    (net (code "125") (name "Net-(IC26A-SCL)") (class "Default")
      (node (ref "IC26") (pin "26") (pinfunction "SCL_26") (pintype "bidirectional"))
      (node (ref "R232") (pin "1") (pinfunction "1_1") (pintype "passive"))
    )
    (net (code "126") (name "Net-(IC26A-SDA)") (class "Default")
      (node (ref "IC26") (pin "27") (pinfunction "SDA_27") (pintype "bidirectional"))
      (node (ref "R229") (pin "1") (pinfunction "1_1") (pintype "passive"))
    )
    (net (code "127") (name "Net-(IC26A-TS2)") (class "Default")
      (node (ref "IC26") (pin "22") (pinfunction "TS2_22") (pintype "bidirectional"))
      (node (ref "R228") (pin "1") (pinfunction "1_1") (pintype "passive"))
    )
    (net (code "128") (name "Net-(IC26B-BAT)") (class "Default")
      (node (ref "C171") (pin "1") (pinfunction "1_1") (pintype "passive"))
      (node (ref "C173") (pin "1") (pinfunction "1_1") (pintype "passive"))
      (node (ref "IC26") (pin "47") (pinfunction "BAT_47") (pintype "input"))
      (node (ref "R189") (pin "2") (pinfunction "2_2") (pintype "passive"))
    )
    (net (code "129") (name "Net-(IC26B-CP1)") (class "Default")
      (node (ref "C173") (pin "2") (pinfunction "2_2") (pintype "passive"))
      (node (ref "IC26") (pin "46") (pinfunction "CP1_46") (pintype "bidirectional"))
    )
    (net (code "130") (name "Net-(IC26B-NC__{slash}VC11)") (class "Default")
      (node (ref "C166") (pin "2") (pinfunction "2_2") (pintype "passive"))
      (node (ref "C167") (pin "1") (pinfunction "1_1") (pintype "passive"))
      (node (ref "IC26") (pin "10") (pinfunction "VC5_/VC6_10") (pintype "bidirectional"))
      (node (ref "IC26") (pin "11") (pinfunction "NC__/VC5_11") (pintype "bidirectional"))
      (node (ref "IC26") (pin "12") (pinfunction "VC4_12") (pintype "bidirectional"))
      (node (ref "IC26") (pin "13") (pinfunction "VC3_13") (pintype "bidirectional"))
      (node (ref "IC26") (pin "14") (pinfunction "VC2_14") (pintype "bidirectional"))
      (node (ref "IC26") (pin "3") (pinfunction "NC__/VC13_3") (pintype "bidirectional"))
      (node (ref "IC26") (pin "4") (pinfunction "VC8_/VC12_4") (pintype "bidirectional"))
      (node (ref "IC26") (pin "5") (pinfunction "NC__/VC11_5") (pintype "bidirectional"))
      (node (ref "IC26") (pin "6") (pinfunction "VC7_/VC10_6") (pintype "bidirectional"))
      (node (ref "IC26") (pin "7") (pinfunction "NC__/VC9_7") (pintype "bidirectional"))
      (node (ref "IC26") (pin "8") (pinfunction "VC6_/VC8_8") (pintype "bidirectional"))
      (node (ref "IC26") (pin "9") (pinfunction "NC__/VC7_9") (pintype "bidirectional"))
      (node (ref "R134") (pin "2") (pinfunction "2_2") (pintype "passive"))
    )
    (net (code "131") (name "Net-(IC26B-NC__{slash}VC15)") (class "Default")
      (node (ref "C166") (pin "1") (pinfunction "1_1") (pintype "passive"))
      (node (ref "C170") (pin "2") (pinfunction "2_2") (pintype "passive"))
      (node (ref "IC26") (pin "1") (pinfunction "NC__/VC15_1") (pintype "bidirectional"))
      (node (ref "IC26") (pin "2") (pinfunction "VC9_/VC14_2") (pintype "bidirectional"))
      (node (ref "R131") (pin "2") (pinfunction "2_2") (pintype "passive"))
    )
    (net (code "132") (name "Net-(IC26B-REG18)") (class "Default")
      (node (ref "C177") (pin "1") (pinfunction "1_1") (pintype "passive"))
      (node (ref "IC26") (pin "24") (pinfunction "REG18_24") (pintype "output"))
    )
    (net (code "133") (name "Net-(IC26B-SRN)") (class "Default")
      (node (ref "C175") (pin "2") (pinfunction "2_2") (pintype "passive"))
      (node (ref "IC26") (pin "20") (pinfunction "SRN_20") (pintype "input"))
      (node (ref "R191") (pin "2") (pinfunction "2_2") (pintype "passive"))
    )
    (net (code "134") (name "Net-(IC26B-SRP)") (class "Default")
      (node (ref "C175") (pin "1") (pinfunction "1_1") (pintype "passive"))
      (node (ref "IC26") (pin "18") (pinfunction "SRP_18") (pintype "input"))
      (node (ref "R190") (pin "2") (pinfunction "2_2") (pintype "passive"))
    )
    (net (code "135") (name "Net-(IC26B-VC0)") (class "Default")
      (node (ref "C168") (pin "1") (pinfunction "1_1") (pintype "passive"))
      (node (ref "IC26") (pin "16") (pinfunction "VC0_16") (pintype "bidirectional"))
      (node (ref "R140") (pin "2") (pinfunction "2_2") (pintype "passive"))
    )
    (net (code "136") (name "Net-(IC26B-VC1)") (class "Default")
      (node (ref "C167") (pin "2") (pinfunction "2_2") (pintype "passive"))
      (node (ref "C169") (pin "1") (pinfunction "1_1") (pintype "passive"))
      (node (ref "IC26") (pin "15") (pinfunction "VC1_15") (pintype "bidirectional"))
      (node (ref "R137") (pin "2") (pinfunction "2_2") (pintype "passive"))
    )
    (net (code "137") (name "Net-(IC26B-VC10{slash}VC16)") (class "Default")
      (node (ref "C170") (pin "1") (pinfunction "1_1") (pintype "passive"))
      (node (ref "IC26") (pin "48") (pinfunction "VC10/VC16_48") (pintype "bidirectional"))
      (node (ref "R128") (pin "2") (pinfunction "2_2") (pintype "passive"))
    )
    (net (code "138") (name "Net-(Q1-C2)") (class "Default")
      (node (ref "C103") (pin "1") (pinfunction "1_1") (pintype "passive"))
      (node (ref "Q1") (pin "3") (pinfunction "C2_3") (pintype "bidirectional"))
      (node (ref "R296") (pin "1") (pinfunction "1_1") (pintype "passive"))
    )
    (net (code "139") (name "Net-(R126-Pad2)") (class "Default")
      (node (ref "R126") (pin "2") (pinfunction "2_2") (pintype "passive"))
      (node (ref "R127") (pin "1") (pinfunction "1_1") (pintype "passive"))
    )
    (net (code "140") (name "Net-(R127-Pad2)") (class "Default")
      (node (ref "R127") (pin "2") (pinfunction "2_2") (pintype "passive"))
      (node (ref "R128") (pin "1") (pinfunction "1_1") (pintype "passive"))
    )
    (net (code "141") (name "Net-(R129-Pad2)") (class "Default")
      (node (ref "R129") (pin "2") (pinfunction "2_2") (pintype "passive"))
      (node (ref "R130") (pin "1") (pinfunction "1_1") (pintype "passive"))
    )
    (net (code "142") (name "Net-(R130-Pad2)") (class "Default")
      (node (ref "R130") (pin "2") (pinfunction "2_2") (pintype "passive"))
      (node (ref "R131") (pin "1") (pinfunction "1_1") (pintype "passive"))
    )
    (net (code "143") (name "Net-(R132-Pad2)") (class "Default")
      (node (ref "R132") (pin "2") (pinfunction "2_2") (pintype "passive"))
      (node (ref "R133") (pin "1") (pinfunction "1_1") (pintype "passive"))
    )
    (net (code "144") (name "Net-(R133-Pad2)") (class "Default")
      (node (ref "R133") (pin "2") (pinfunction "2_2") (pintype "passive"))
      (node (ref "R134") (pin "1") (pinfunction "1_1") (pintype "passive"))
    )
    (net (code "145") (name "Net-(R135-Pad2)") (class "Default")
      (node (ref "R135") (pin "2") (pinfunction "2_2") (pintype "passive"))
      (node (ref "R136") (pin "1") (pinfunction "1_1") (pintype "passive"))
    )
    (net (code "146") (name "Net-(R136-Pad2)") (class "Default")
      (node (ref "R136") (pin "2") (pinfunction "2_2") (pintype "passive"))
      (node (ref "R137") (pin "1") (pinfunction "1_1") (pintype "passive"))
    )
    (net (code "147") (name "Net-(R138-Pad2)") (class "Default")
      (node (ref "R138") (pin "2") (pinfunction "2_2") (pintype "passive"))
      (node (ref "R139") (pin "1") (pinfunction "1_1") (pintype "passive"))
    )
    (net (code "148") (name "Net-(R139-Pad2)") (class "Default")
      (node (ref "R139") (pin "2") (pinfunction "2_2") (pintype "passive"))
      (node (ref "R140") (pin "1") (pinfunction "1_1") (pintype "passive"))
    )
    (net (code "149") (name "Net-(R141-Pad1)") (class "Default")
      (node (ref "R141") (pin "1") (pinfunction "1_1") (pintype "passive"))
      (node (ref "R24") (pin "2") (pinfunction "2_2") (pintype "passive"))
    )
    (net (code "150") (name "Net-(T1-G)") (class "Default")
      (node (ref "C39") (pin "2") (pinfunction "2_2") (pintype "passive"))
      (node (ref "C40") (pin "1") (pinfunction "1_1") (pintype "passive"))
      (node (ref "R22") (pin "1") (pinfunction "1_1") (pintype "passive"))
      (node (ref "R23") (pin "1") (pinfunction "1_1") (pintype "passive"))
      (node (ref "T1") (pin "4") (pinfunction "G_4") (pintype "passive"))
    )
    (net (code "151") (name "Net-(T2-D)") (class "Default")
      (node (ref "R3") (pin "1") (pinfunction "1_1") (pintype "passive"))
      (node (ref "R8") (pin "1") (pinfunction "1_1") (pintype "passive"))
      (node (ref "T2") (pin "3") (pinfunction "D_3") (pintype "passive"))
      (node (ref "T7") (pin "3") (pinfunction "D_3") (pintype "passive"))
    )
    (net (code "152") (name "Net-(T3-D)") (class "Default")
      (node (ref "C40") (pin "2") (pinfunction "2_2") (pintype "passive"))
      (node (ref "L16") (pin "1") (pinfunction "1_1") (pintype "passive"))
      (node (ref "R141") (pin "2") (pinfunction "2_2") (pintype "passive"))
      (node (ref "T3") (pin "5") (pinfunction "D_5") (pintype "passive"))
    )
    (net (code "153") (name "Net-(T3-G)") (class "Default")
      (node (ref "R23") (pin "2") (pinfunction "2_2") (pintype "passive"))
      (node (ref "T3") (pin "4") (pinfunction "G_4") (pintype "passive"))
    )
    (net (code "154") (name "Net-(T4-D)") (class "Default")
      (node (ref "R102") (pin "1") (pinfunction "1_1") (pintype "passive"))
      (node (ref "R105") (pin "1") (pinfunction "1_1") (pintype "passive"))
      (node (ref "R108") (pin "1") (pinfunction "1_1") (pintype "passive"))
      (node (ref "R111") (pin "1") (pinfunction "1_1") (pintype "passive"))
      (node (ref "R114") (pin "1") (pinfunction "1_1") (pintype "passive"))
      (node (ref "R63") (pin "1") (pinfunction "1_1") (pintype "passive"))
      (node (ref "R66") (pin "1") (pinfunction "1_1") (pintype "passive"))
      (node (ref "R72") (pin "1") (pinfunction "1_1") (pintype "passive"))
      (node (ref "R75") (pin "1") (pinfunction "1_1") (pintype "passive"))
      (node (ref "R78") (pin "1") (pinfunction "1_1") (pintype "passive"))
      (node (ref "T4") (pin "3") (pinfunction "D_3") (pintype "passive"))
    )
    (net (code "155") (name "Net-(T5-D)") (class "Default")
      (node (ref "R100") (pin "1") (pinfunction "1_1") (pintype "passive"))
      (node (ref "R103") (pin "1") (pinfunction "1_1") (pintype "passive"))
      (node (ref "R106") (pin "1") (pinfunction "1_1") (pintype "passive"))
      (node (ref "R109") (pin "1") (pinfunction "1_1") (pintype "passive"))
      (node (ref "R112") (pin "1") (pinfunction "1_1") (pintype "passive"))
      (node (ref "R115") (pin "1") (pinfunction "1_1") (pintype "passive"))
      (node (ref "R64") (pin "1") (pinfunction "1_1") (pintype "passive"))
      (node (ref "R70") (pin "1") (pinfunction "1_1") (pintype "passive"))
      (node (ref "R73") (pin "1") (pinfunction "1_1") (pintype "passive"))
      (node (ref "R76") (pin "1") (pinfunction "1_1") (pintype "passive"))
      (node (ref "T5") (pin "3") (pinfunction "D_3") (pintype "passive"))
    )
    (net (code "156") (name "Net-(T6-D)") (class "Default")
      (node (ref "R101") (pin "1") (pinfunction "1_1") (pintype "passive"))
      (node (ref "R104") (pin "1") (pinfunction "1_1") (pintype "passive"))
      (node (ref "R107") (pin "1") (pinfunction "1_1") (pintype "passive"))
      (node (ref "R110") (pin "1") (pinfunction "1_1") (pintype "passive"))
      (node (ref "R113") (pin "1") (pinfunction "1_1") (pintype "passive"))
      (node (ref "R116") (pin "1") (pinfunction "1_1") (pintype "passive"))
      (node (ref "R65") (pin "1") (pinfunction "1_1") (pintype "passive"))
      (node (ref "R71") (pin "1") (pinfunction "1_1") (pintype "passive"))
      (node (ref "R74") (pin "1") (pinfunction "1_1") (pintype "passive"))
      (node (ref "R77") (pin "1") (pinfunction "1_1") (pintype "passive"))
      (node (ref "T6") (pin "3") (pinfunction "D_3") (pintype "passive"))
    )
    (net (code "157") (name "Net-(T8-G)") (class "Default")
      (node (ref "R4") (pin "2") (pinfunction "2_2") (pintype "passive"))
      (node (ref "T8") (pin "4") (pinfunction "G_4") (pintype "passive"))
    )
    (net (code "158") (name "Net-(T9-G)") (class "Default")
      (node (ref "R5") (pin "2") (pinfunction "2_2") (pintype "passive"))
      (node (ref "T9") (pin "4") (pinfunction "G_4") (pintype "passive"))
    )
    (net (code "159") (name "Net-(T11-G)") (class "Default")
      (node (ref "C59") (pin "1") (pinfunction "1_1") (pintype "passive"))
      (node (ref "R30") (pin "2") (pinfunction "2_2") (pintype "passive"))
      (node (ref "T11") (pin "1") (pinfunction "G_1") (pintype "passive"))
    )
    (net (code "160") (name "Net-(T12-G)") (class "Default")
      (node (ref "C60") (pin "1") (pinfunction "1_1") (pintype "passive"))
      (node (ref "R49") (pin "1") (pinfunction "1_1") (pintype "passive"))
      (node (ref "T12") (pin "1") (pinfunction "G_1") (pintype "passive"))
    )
    (net (code "161") (name "Net-(T13-G)") (class "Default")
      (node (ref "R43") (pin "1") (pinfunction "1_1") (pintype "passive"))
      (node (ref "R80") (pin "2") (pinfunction "2_2") (pintype "passive"))
      (node (ref "R84") (pin "2") (pinfunction "2_2") (pintype "passive"))
      (node (ref "T13") (pin "4") (pinfunction "G_4") (pintype "passive"))
    )
    (net (code "162") (name "Net-(T14-G)") (class "Default")
      (node (ref "R79") (pin "1") (pinfunction "1_1") (pintype "passive"))
      (node (ref "R81") (pin "1") (pinfunction "1_1") (pintype "passive"))
      (node (ref "R85") (pin "2") (pinfunction "2_2") (pintype "passive"))
      (node (ref "T14") (pin "4") (pinfunction "G_4") (pintype "passive"))
    )
    (net (code "163") (name "Net-(T15-G)") (class "Default")
      (node (ref "C62") (pin "1") (pinfunction "1_1") (pintype "passive"))
      (node (ref "PTC1") (pin "2") (pinfunction "2_2") (pintype "passive"))
      (node (ref "R54") (pin "1") (pinfunction "1_1") (pintype "passive"))
      (node (ref "T15") (pin "1") (pinfunction "G_1") (pintype "passive"))
      (node (ref "TP35") (pin "P$1") (pinfunction "TP_P$1") (pintype "input"))
    )
    (net (code "164") (name "Net-(T16-D)") (class "Default")
      (node (ref "R84") (pin "1") (pinfunction "1_1") (pintype "passive"))
      (node (ref "T16") (pin "3") (pinfunction "D_3") (pintype "passive"))
    )
    (net (code "165") (name "Net-(T17-D)") (class "Default")
      (node (ref "R85") (pin "1") (pinfunction "1_1") (pintype "passive"))
      (node (ref "T17") (pin "3") (pinfunction "D_3") (pintype "passive"))
    )
    (net (code "166") (name "Net-(TP1-TP)") (class "Default")
      (node (ref "R51") (pin "2") (pinfunction "2_2") (pintype "passive"))
      (node (ref "TP1") (pin "P$1") (pinfunction "TP_P$1") (pintype "input"))
    )
    (net (code "167") (name "Net-(TP2-TP)") (class "Default")
      (node (ref "R52") (pin "2") (pinfunction "2_2") (pintype "passive"))
      (node (ref "TP2") (pin "P$1") (pinfunction "TP_P$1") (pintype "input"))
    )
    (net (code "168") (name "Net-(TP3-TP)") (class "Default")
      (node (ref "R53") (pin "2") (pinfunction "2_2") (pintype "passive"))
      (node (ref "TP3") (pin "P$1") (pinfunction "TP_P$1") (pintype "input"))
    )
    (net (code "169") (name "Net-(TP4-TP)") (class "Default")
      (node (ref "R58") (pin "2") (pinfunction "2_2") (pintype "passive"))
      (node (ref "TP4") (pin "P$1") (pinfunction "TP_P$1") (pintype "input"))
    )
    (net (code "170") (name "Net-(TP5-TP)") (class "Default")
      (node (ref "R95") (pin "2") (pinfunction "2_2") (pintype "passive"))
      (node (ref "TP5") (pin "P$1") (pinfunction "TP_P$1") (pintype "input"))
    )
    (net (code "171") (name "Net-(TP23-TP)") (class "Default")
      (node (ref "C3") (pin "1") (pinfunction "1_1") (pintype "passive"))
      (node (ref "R9") (pin "2") (pinfunction "2_2") (pintype "passive"))
      (node (ref "R99") (pin "2") (pinfunction "2_2") (pintype "passive"))
      (node (ref "TP23") (pin "P$1") (pinfunction "TP_P$1") (pintype "input"))
      (node (ref "X2") (pin "1") (pinfunction "1_1") (pintype "passive"))
    )
    (net (code "172") (name "Net-(TP41-TP)") (class "Default")
      (node (ref "R12") (pin "1") (pinfunction "1_1") (pintype "passive"))
      (node (ref "R149") (pin "1") (pinfunction "1_1") (pintype "passive"))
      (node (ref "S1") (pin "1") (pinfunction "S_1") (pintype "passive"))
      (node (ref "S1") (pin "2") (pinfunction "S_2") (pintype "passive"))
      (node (ref "TP41") (pin "P$1") (pinfunction "TP_P$1") (pintype "input"))
    )
    (net (code "173") (name "Net-(TP42-TP)") (class "Default")
      (node (ref "C64") (pin "1") (pinfunction "1_1") (pintype "passive"))
      (node (ref "R61") (pin "1") (pinfunction "1_1") (pintype "passive"))
      (node (ref "TP42") (pin "P$1") (pinfunction "TP_P$1") (pintype "input"))
    )
    (net (code "174") (name "SCP_HEATER") (class "Default")
      (node (ref "R147") (pin "1") (pinfunction "1_1") (pintype "passive"))
      (node (ref "R148") (pin "1") (pinfunction "1_1") (pintype "passive"))
      (node (ref "T11") (pin "3") (pinfunction "D_3") (pintype "passive"))
      (node (ref "T12") (pin "3") (pinfunction "D_3") (pintype "passive"))
      (node (ref "T15") (pin "3") (pinfunction "D_3") (pintype "passive"))
      (node (ref "TP34") (pin "P$1") (pinfunction "TP_P$1") (pintype "input"))
    )
    (net (code "175") (name "SINGLE_WIRE_CAN_3V3") (class "Default")
      (node (ref "D11") (pin "2") (pinfunction "A2_2") (pintype "passive"))
      (node (ref "R122") (pin "1") (pinfunction "1_1") (pintype "passive"))
      (node (ref "R123") (pin "1") (pinfunction "1_1") (pintype "passive"))
      (node (ref "R90") (pin "1") (pinfunction "1_1") (pintype "passive"))
    )
    (net (code "176") (name "TYPE_C_CC1") (class "Default")
      (node (ref "C282") (pin "1") (pinfunction "1_1") (pintype "passive"))
      (node (ref "R322") (pin "1") (pinfunction "1_1") (pintype "passive"))
      (node (ref "TP9") (pin "P$1") (pinfunction "TP_P$1") (pintype "input"))
      (node (ref "X1") (pin "A5") (pinfunction "CC1_A5") (pintype "bidirectional"))
    )
    (net (code "177") (name "TYPE_C_CC2") (class "Default")
      (node (ref "C283") (pin "1") (pinfunction "1_1") (pintype "passive"))
      (node (ref "R337") (pin "1") (pinfunction "1_1") (pintype "passive"))
      (node (ref "TP10") (pin "P$1") (pinfunction "TP_P$1") (pintype "input"))
      (node (ref "X1") (pin "B5") (pinfunction "CC2_B5") (pintype "bidirectional"))
    )
    (net (code "178") (name "TYPE_C_VBUS") (class "Default")
      (node (ref "C19") (pin "1") (pinfunction "1_1") (pintype "passive"))
      (node (ref "D1") (pin "C") (pinfunction "C_C") (pintype "passive"))
      (node (ref "D5") (pin "A") (pinfunction "A_A") (pintype "passive"))
      (node (ref "D7") (pin "A") (pinfunction "A_A") (pintype "passive"))
      (node (ref "L16") (pin "2") (pinfunction "2_2") (pintype "passive"))
      (node (ref "R1") (pin "2") (pinfunction "2_2") (pintype "passive"))
      (node (ref "R56") (pin "2") (pinfunction "2_2") (pintype "passive"))
      (node (ref "TP8") (pin "P$1") (pinfunction "TP_P$1") (pintype "input"))
      (node (ref "X1") (pin "A4") (pinfunction "VBUS_A4") (pintype "output"))
      (node (ref "X1") (pin "A9") (pinfunction "VBUS_A9") (pintype "output"))
      (node (ref "X1") (pin "B4") (pinfunction "VBUS_B4") (pintype "output"))
      (node (ref "X1") (pin "B9") (pinfunction "VBUS_B9") (pintype "output"))
    )
    (net (code "179") (name "UC_ADC_HW_VERSION") (class "Default")
      (node (ref "C16") (pin "1") (pinfunction "1_1") (pintype "passive"))
      (node (ref "IC8") (pin "12") (pinfunction "PA4_12") (pintype "bidirectional"))
      (node (ref "R124") (pin "1") (pinfunction "1_1") (pintype "passive"))
      (node (ref "R125") (pin "2") (pinfunction "2_2") (pintype "passive"))
    )
    (net (code "180") (name "UC_ADC_IADP") (class "Default")
      (node (ref "C2") (pin "1") (pinfunction "1_1") (pintype "passive"))
      (node (ref "IC11") (pin "7") (pinfunction "IADP_7") (pintype "output"))
      (node (ref "IC8") (pin "27") (pinfunction "PB14_27") (pintype "bidirectional"))
    )
    (net (code "181") (name "UC_ADC_IDCHG") (class "Default")
      (node (ref "C5") (pin "1") (pinfunction "1_1") (pintype "passive"))
      (node (ref "IC11") (pin "8") (pinfunction "IDCHG_8") (pintype "output"))
      (node (ref "IC8") (pin "25") (pinfunction "PB12_25") (pintype "bidirectional"))
    )
    (net (code "182") (name "UC_ADC_NTC") (class "Default")
      (node (ref "C4") (pin "1") (pinfunction "1_1") (pintype "passive"))
      (node (ref "IC8") (pin "13") (pinfunction "PA5_13") (pintype "bidirectional"))
      (node (ref "R9") (pin "1") (pinfunction "1_1") (pintype "passive"))
    )
    (net (code "183") (name "UC_ADC_VBUS") (class "Default")
      (node (ref "C1") (pin "1") (pinfunction "1_1") (pintype "passive"))
      (node (ref "IC8") (pin "14") (pinfunction "PA6_14") (pintype "bidirectional"))
      (node (ref "R1") (pin "1") (pinfunction "1_1") (pintype "passive"))
      (node (ref "R2") (pin "2") (pinfunction "2_2") (pintype "passive"))
    )
    (net (code "184") (name "UC_BQ76952_RST_SHUT") (class "Default")
      (node (ref "IC26") (pin "33") (pinfunction "RST_SHUT_33") (pintype "input"))
      (node (ref "R11") (pin "1") (pinfunction "1_1") (pintype "passive"))
      (node (ref "R217") (pin "2") (pinfunction "2_2") (pintype "passive"))
    )
    (net (code "185") (name "UC_CHARGER_EN") (class "Default")
      (node (ref "IC8") (pin "28") (pinfunction "PB15_28") (pintype "bidirectional"))
      (node (ref "R28") (pin "1") (pinfunction "1_1") (pintype "passive"))
    )
    (net (code "186") (name "UC_CHG_FET_DISABLE") (class "Default")
      (node (ref "R117") (pin "1") (pinfunction "1_1") (pintype "passive"))
      (node (ref "R86") (pin "2") (pinfunction "2_2") (pintype "passive"))
      (node (ref "T16") (pin "1") (pinfunction "G_1") (pintype "passive"))
    )
    (net (code "187") (name "UC_DSG_FET_DISABLE") (class "Default")
      (node (ref "R118") (pin "1") (pinfunction "1_1") (pintype "passive"))
      (node (ref "R87") (pin "2") (pinfunction "2_2") (pintype "passive"))
      (node (ref "T17") (pin "1") (pinfunction "G_1") (pintype "passive"))
    )
    (net (code "188") (name "UC_I2C_SCL") (class "Default")
      (node (ref "IC8") (pin "38") (pinfunction "PA15_38") (pintype "bidirectional"))
      (node (ref "R232") (pin "2") (pinfunction "2_2") (pintype "passive"))
      (node (ref "R44") (pin "1") (pinfunction "1_1") (pintype "passive"))
      (node (ref "R51") (pin "1") (pinfunction "1_1") (pintype "passive"))
      (node (ref "R92") (pin "2") (pinfunction "2_2") (pintype "passive"))
      (node (ref "R93") (pin "1") (pinfunction "1_1") (pintype "passive"))
    )
    (net (code "189") (name "UC_I2C_SDA") (class "Default")
      (node (ref "IC8") (pin "45") (pinfunction "PB7_45") (pintype "bidirectional"))
      (node (ref "R19") (pin "2") (pinfunction "2_2") (pintype "passive"))
      (node (ref "R229") (pin "2") (pinfunction "2_2") (pintype "passive"))
      (node (ref "R45") (pin "1") (pinfunction "1_1") (pintype "passive"))
      (node (ref "R52") (pin "1") (pinfunction "1_1") (pintype "passive"))
      (node (ref "R94") (pin "1") (pinfunction "1_1") (pintype "passive"))
    )
    (net (code "190") (name "UC_NRST_3V3") (class "Default")
      (node (ref "C48") (pin "1") (pinfunction "1_1") (pintype "passive"))
      (node (ref "IC8") (pin "7") (pinfunction "~{NRST}/PG10/MCO_7") (pintype "bidirectional"))
      (node (ref "R67") (pin "1") (pinfunction "1_1") (pintype "passive"))
    )
    (net (code "191") (name "UC_NTC_EN") (class "Default")
      (node (ref "IC8") (pin "9") (pinfunction "PA1_9") (pintype "bidirectional"))
      (node (ref "R99") (pin "1") (pinfunction "1_1") (pintype "passive"))
    )
    (net (code "192") (name "UC_SWCLK_3V3") (class "Default")
      (node (ref "IC8") (pin "37") (pinfunction "PA14_37") (pintype "bidirectional"))
      (node (ref "R68") (pin "1") (pinfunction "1_1") (pintype "passive"))
    )
    (net (code "193") (name "UC_SWDIO_3V3") (class "Default")
      (node (ref "IC8") (pin "36") (pinfunction "PA13_36") (pintype "bidirectional"))
      (node (ref "R69") (pin "1") (pinfunction "1_1") (pintype "passive"))
    )
    (net (code "194") (name "UC_SWO_3V3") (class "Default")
      (node (ref "IC8") (pin "41") (pinfunction "PB3_41") (pintype "bidirectional"))
      (node (ref "R16") (pin "1") (pinfunction "1_1") (pintype "passive"))
    )
    (net (code "195") (name "UC_USB_CC1") (class "Default")
      (node (ref "C234") (pin "1") (pinfunction "1_1") (pintype "passive"))
      (node (ref "IC8") (pin "31") (pinfunction "PA9_31") (pintype "bidirectional"))
      (node (ref "IC8") (pin "44") (pinfunction "PB6_44") (pintype "bidirectional"))
      (node (ref "R13") (pin "2") (pinfunction "2_2") (pintype "passive"))
      (node (ref "R322") (pin "2") (pinfunction "2_2") (pintype "passive"))
      (node (ref "T2") (pin "1") (pinfunction "G_1") (pintype "passive"))
    )
    (net (code "196") (name "UC_USB_CC2") (class "Default")
      (node (ref "C235") (pin "1") (pinfunction "1_1") (pintype "passive"))
      (node (ref "IC8") (pin "32") (pinfunction "PA10_32") (pintype "bidirectional"))
      (node (ref "IC8") (pin "42") (pinfunction "PB4_42") (pintype "bidirectional"))
      (node (ref "R14") (pin "2") (pinfunction "2_2") (pintype "passive"))
      (node (ref "R337") (pin "2") (pinfunction "2_2") (pintype "passive"))
      (node (ref "T7") (pin "1") (pinfunction "G_1") (pintype "passive"))
    )
    (net (code "197") (name "UC_USB_DET_3V3") (class "Default")
      (node (ref "IC8") (pin "10") (pinfunction "PA2_10") (pintype "bidirectional"))
      (node (ref "R3") (pin "2") (pinfunction "2_2") (pintype "passive"))
    )
    (net (code "198") (name "UC_USER_BTN") (class "Default")
      (node (ref "C29") (pin "1") (pinfunction "1_1") (pintype "passive"))
      (node (ref "IC8") (pin "8") (pinfunction "PA0_8") (pintype "bidirectional"))
      (node (ref "R12") (pin "2") (pinfunction "2_2") (pintype "passive"))
    )
    (net (code "199") (name "VBAT_FUSED") (class "Default")
      (node (ref "C41") (pin "2") (pinfunction "2_2") (pintype "passive"))
      (node (ref "D19") (pin "A") (pinfunction "A_A") (pintype "passive"))
      (node (ref "F2") (pin "T3") (pinfunction "F2_T3") (pintype "passive"))
      (node (ref "R43") (pin "2") (pinfunction "2_2") (pintype "passive"))
      (node (ref "T13") (pin "1") (pinfunction "S_1") (pintype "passive"))
      (node (ref "T13") (pin "2") (pinfunction "S_2") (pintype "passive"))
      (node (ref "T13") (pin "3") (pinfunction "S_3") (pintype "passive"))
    )
    (net (code "200") (name "VSS_BAT") (class "Default")
      (node (ref "C168") (pin "2") (pinfunction "2_2") (pintype "passive"))
      (node (ref "C169") (pin "2") (pinfunction "2_2") (pintype "passive"))
      (node (ref "C171") (pin "2") (pinfunction "2_2") (pintype "passive"))
      (node (ref "C177") (pin "2") (pinfunction "2_2") (pintype "passive"))
      (node (ref "C46") (pin "2") (pinfunction "2_2") (pintype "passive"))
      (node (ref "C49") (pin "2") (pinfunction "2_2") (pintype "passive"))
      (node (ref "C56") (pin "2") (pinfunction "2_2") (pintype "passive"))
      (node (ref "C59") (pin "2") (pinfunction "2_2") (pintype "passive"))
      (node (ref "C60") (pin "2") (pinfunction "2_2") (pintype "passive"))
      (node (ref "C7") (pin "2") (pinfunction "2_2") (pintype "passive"))
      (node (ref "IC1") (pin "6") (pinfunction "VSS_6") (pintype "input"))
      (node (ref "IC1") (pin "P$1") (pinfunction "VSS_P$1") (pintype "input"))
      (node (ref "IC1") (pin "P$2") (pinfunction "VSS_P$2") (pintype "input"))
      (node (ref "IC26") (pin "17") (pinfunction "VSS_17") (pintype "input"))
      (node (ref "R138") (pin "1") (pinfunction "1_1") (pintype "passive"))
      (node (ref "R190") (pin "1") (pinfunction "1_1") (pintype "passive"))
      (node (ref "R192") (pin "1") (pinfunction "1_1") (pintype "passive"))
      (node (ref "R48") (pin "1") (pinfunction "1_1") (pintype "passive"))
      (node (ref "R50") (pin "1") (pinfunction "1_1") (pintype "passive"))
      (node (ref "T11") (pin "2") (pinfunction "S_2") (pintype "passive"))
      (node (ref "T12") (pin "2") (pinfunction "S_2") (pintype "passive"))
      (node (ref "TP29") (pin "P$1") (pinfunction "TP_P$1") (pintype "input"))
      (node (ref "X11") (pin "P$1") (pinfunction "P_P$1") (pintype "passive"))
      (node (ref "X11") (pin "P$10") (pinfunction "P_P$10") (pintype "passive"))
      (node (ref "X11") (pin "P$11") (pinfunction "P_P$11") (pintype "passive"))
      (node (ref "X11") (pin "P$12") (pinfunction "P_P$12") (pintype "passive"))
      (node (ref "X11") (pin "P$13") (pinfunction "P_P$13") (pintype "passive"))
      (node (ref "X11") (pin "P$14") (pinfunction "P_P$14") (pintype "passive"))
      (node (ref "X11") (pin "P$15") (pinfunction "P_P$15") (pintype "passive"))
      (node (ref "X11") (pin "P$16") (pinfunction "P_P$16") (pintype "passive"))
      (node (ref "X11") (pin "P$17") (pinfunction "P_P$17") (pintype "passive"))
      (node (ref "X11") (pin "P$18") (pinfunction "P_P$18") (pintype "passive"))
      (node (ref "X11") (pin "P$19") (pinfunction "P_P$19") (pintype "passive"))
      (node (ref "X11") (pin "P$2") (pinfunction "P_P$2") (pintype "passive"))
      (node (ref "X11") (pin "P$20") (pinfunction "P_P$20") (pintype "passive"))
      (node (ref "X11") (pin "P$21") (pinfunction "P_P$21") (pintype "passive"))
      (node (ref "X11") (pin "P$22") (pinfunction "P_P$22") (pintype "passive"))
      (node (ref "X11") (pin "P$23") (pinfunction "P_P$23") (pintype "passive"))
      (node (ref "X11") (pin "P$24") (pinfunction "P_P$24") (pintype "passive"))
      (node (ref "X11") (pin "P$25") (pinfunction "P_P$25") (pintype "passive"))
      (node (ref "X11") (pin "P$26") (pinfunction "P_P$26") (pintype "passive"))
      (node (ref "X11") (pin "P$27") (pinfunction "P_P$27") (pintype "passive"))
      (node (ref "X11") (pin "P$28") (pinfunction "P_P$28") (pintype "passive"))
      (node (ref "X11") (pin "P$29") (pinfunction "P_P$29") (pintype "passive"))
      (node (ref "X11") (pin "P$3") (pinfunction "P_P$3") (pintype "passive"))
      (node (ref "X11") (pin "P$30") (pinfunction "P_P$30") (pintype "passive"))
      (node (ref "X11") (pin "P$31") (pinfunction "P_P$31") (pintype "passive"))
      (node (ref "X11") (pin "P$32") (pinfunction "P_P$32") (pintype "passive"))
      (node (ref "X11") (pin "P$33") (pinfunction "P_P$33") (pintype "passive"))
      (node (ref "X11") (pin "P$34") (pinfunction "P_P$34") (pintype "passive"))
      (node (ref "X11") (pin "P$35") (pinfunction "P_P$35") (pintype "passive"))
      (node (ref "X11") (pin "P$36") (pinfunction "P_P$36") (pintype "passive"))
      (node (ref "X11") (pin "P$37") (pinfunction "P_P$37") (pintype "passive"))
      (node (ref "X11") (pin "P$38") (pinfunction "P_P$38") (pintype "passive"))
      (node (ref "X11") (pin "P$39") (pinfunction "P_P$39") (pintype "passive"))
      (node (ref "X11") (pin "P$4") (pinfunction "P_P$4") (pintype "passive"))
      (node (ref "X11") (pin "P$40") (pinfunction "P_P$40") (pintype "passive"))
      (node (ref "X11") (pin "P$41") (pinfunction "P_P$41") (pintype "passive"))
      (node (ref "X11") (pin "P$42") (pinfunction "P_P$42") (pintype "passive"))
      (node (ref "X11") (pin "P$43") (pinfunction "P_P$43") (pintype "passive"))
      (node (ref "X11") (pin "P$44") (pinfunction "P_P$44") (pintype "passive"))
      (node (ref "X11") (pin "P$45") (pinfunction "P_P$45") (pintype "passive"))
      (node (ref "X11") (pin "P$46") (pinfunction "P_P$46") (pintype "passive"))
      (node (ref "X11") (pin "P$47") (pinfunction "P_P$47") (pintype "passive"))
      (node (ref "X11") (pin "P$48") (pinfunction "P_P$48") (pintype "passive"))
      (node (ref "X11") (pin "P$49") (pinfunction "P_P$49") (pintype "passive"))
      (node (ref "X11") (pin "P$5") (pinfunction "P_P$5") (pintype "passive"))
      (node (ref "X11") (pin "P$50") (pinfunction "P_P$50") (pintype "passive"))
      (node (ref "X11") (pin "P$51") (pinfunction "P_P$51") (pintype "passive"))
      (node (ref "X11") (pin "P$52") (pinfunction "P_P$52") (pintype "passive"))
      (node (ref "X11") (pin "P$53") (pinfunction "P_P$53") (pintype "passive"))
      (node (ref "X11") (pin "P$54") (pinfunction "P_P$54") (pintype "passive"))
      (node (ref "X11") (pin "P$55") (pinfunction "P_P$55") (pintype "passive"))
      (node (ref "X11") (pin "P$56") (pinfunction "P_P$56") (pintype "passive"))
      (node (ref "X11") (pin "P$57") (pinfunction "P_P$57") (pintype "passive"))
      (node (ref "X11") (pin "P$58") (pinfunction "P_P$58") (pintype "passive"))
      (node (ref "X11") (pin "P$59") (pinfunction "P_P$59") (pintype "passive"))
      (node (ref "X11") (pin "P$6") (pinfunction "P_P$6") (pintype "passive"))
      (node (ref "X11") (pin "P$60") (pinfunction "P_P$60") (pintype "passive"))
      (node (ref "X11") (pin "P$61") (pinfunction "P_P$61") (pintype "passive"))
      (node (ref "X11") (pin "P$62") (pinfunction "P_P$62") (pintype "passive"))
      (node (ref "X11") (pin "P$63") (pinfunction "P_P$63") (pintype "passive"))
      (node (ref "X11") (pin "P$64") (pinfunction "P_P$64") (pintype "passive"))
      (node (ref "X11") (pin "P$65") (pinfunction "P_P$65") (pintype "passive"))
      (node (ref "X11") (pin "P$66") (pinfunction "P_P$66") (pintype "passive"))
      (node (ref "X11") (pin "P$67") (pinfunction "P_P$67") (pintype "passive"))
      (node (ref "X11") (pin "P$7") (pinfunction "P_P$7") (pintype "passive"))
      (node (ref "X11") (pin "P$8") (pinfunction "P_P$8") (pintype "passive"))
      (node (ref "X11") (pin "P$9") (pinfunction "P_P$9") (pintype "passive"))
      (node (ref "X14") (pin "2") (pinfunction "2_2") (pintype "passive"))
    )
    (net (code "201") (name "V_PACK") (class "Default")
      (node (ref "C61") (pin "1") (pinfunction "1_1") (pintype "passive"))
      (node (ref "D4") (pin "C") (pinfunction "C_C") (pintype "passive"))
      (node (ref "D6") (pin "A") (pinfunction "A_A") (pintype "passive"))
      (node (ref "D8") (pin "A") (pinfunction "A_A") (pintype "passive"))
      (node (ref "R218") (pin "2") (pinfunction "2_2") (pintype "passive"))
      (node (ref "R227") (pin "2") (pinfunction "2_2") (pintype "passive"))
      (node (ref "R79") (pin "2") (pinfunction "2_2") (pintype "passive"))
      (node (ref "T14") (pin "1") (pinfunction "S_1") (pintype "passive"))
      (node (ref "T14") (pin "2") (pinfunction "S_2") (pintype "passive"))
      (node (ref "T14") (pin "3") (pinfunction "S_3") (pintype "passive"))
      (node (ref "TP43") (pin "P$1") (pinfunction "TP_P$1") (pintype "input"))
      (node (ref "X13") (pin "5") (pinfunction "5_5") (pintype "passive"))
      (node (ref "X13") (pin "6") (pinfunction "6_6") (pintype "passive"))
      (node (ref "X13") (pin "7") (pinfunction "7_7") (pintype "passive"))
    )
    (net (code "202") (name "unconnected-(D11-A1-Pad1)") (class "Default")
      (node (ref "D11") (pin "1") (pinfunction "A1_1") (pintype "passive"))
    )
    (net (code "203") (name "unconnected-(D20-C_BLUE-Pad4)") (class "Default")
      (node (ref "D20") (pin "4") (pinfunction "C_BLUE_4") (pintype "passive"))
    )
    (net (code "204") (name "unconnected-(D20-C_RED-Pad2)") (class "Default")
      (node (ref "D20") (pin "2") (pinfunction "C_RED_2") (pintype "passive"))
    )
    (net (code "205") (name "unconnected-(IC4-ALERT-Pad3)") (class "Default")
      (node (ref "IC4") (pin "3") (pinfunction "ALERT_3") (pintype "open_collector"))
    )
    (net (code "206") (name "unconnected-(IC5-ALERT-Pad3)") (class "Default")
      (node (ref "IC5") (pin "3") (pinfunction "ALERT_3") (pintype "open_collector"))
    )
    (net (code "207") (name "unconnected-(IC8B-PA3-Pad11)") (class "Default")
      (node (ref "IC8") (pin "11") (pinfunction "PA3_11") (pintype "bidirectional"))
    )
    (net (code "208") (name "unconnected-(IC8C-PB2-Pad19)") (class "Default")
      (node (ref "IC8") (pin "19") (pinfunction "PB2_19") (pintype "bidirectional"))
    )
    (net (code "209") (name "unconnected-(IC8D-PC4-Pad16)") (class "Default")
      (node (ref "IC8") (pin "16") (pinfunction "PC4_16") (pintype "bidirectional"))
    )
    (net (code "210") (name "unconnected-(IC8D-PC11-Pad40)") (class "Default")
      (node (ref "IC8") (pin "40") (pinfunction "PC11_40") (pintype "bidirectional"))
    )
    (net (code "211") (name "unconnected-(IC10-EN-Pad4)") (class "Default")
      (node (ref "IC10") (pin "4") (pinfunction "EN_4") (pintype "input"))
    )
    (net (code "212") (name "unconnected-(IC11-BATDRV-Pad18)") (class "Default")
      (node (ref "IC11") (pin "18") (pinfunction "BATDRV_18") (pintype "output"))
    )
    (net (code "213") (name "unconnected-(IC11-CMPOUT-Pad14)") (class "Default")
      (node (ref "IC11") (pin "14") (pinfunction "CMPOUT_14") (pintype "open_collector"))
    )
    (net (code "214") (name "unconnected-(IC11-PMON-Pad9)") (class "Default")
      (node (ref "IC11") (pin "9") (pinfunction "PMON_9") (pintype "output"))
    )
    (net (code "215") (name "unconnected-(IC14-I{slash}O4-Pad6)") (class "Default")
      (node (ref "IC14") (pin "6") (pinfunction "I/O4_6") (pintype "passive"))
    )
    (net (code "216") (name "unconnected-(IC26A-DCHG-Pad31)") (class "Default")
      (node (ref "IC26") (pin "31") (pinfunction "DCHG_31") (pintype "bidirectional"))
    )
    (net (code "217") (name "unconnected-(IC26A-DDSG-Pad32)") (class "Default")
      (node (ref "IC26") (pin "32") (pinfunction "DDSG_32") (pintype "bidirectional"))
    )
    (net (code "218") (name "unconnected-(IC26A-PCHG-Pad40)") (class "Default")
      (node (ref "IC26") (pin "40") (pinfunction "PCHG_40") (pintype "output"))
    )
    (net (code "219") (name "unconnected-(IC26A-PDSG-Pad39)") (class "Default")
      (node (ref "IC26") (pin "39") (pinfunction "PDSG_39") (pintype "output"))
    )
    (net (code "220") (name "unconnected-(IC26A-TS3-Pad23)") (class "Default")
      (node (ref "IC26") (pin "23") (pinfunction "TS3_23") (pintype "bidirectional"))
    )
    (net (code "221") (name "unconnected-(IC26B-REG1-Pad35)") (class "Default")
      (node (ref "IC26") (pin "35") (pinfunction "REG1_35") (pintype "output"))
    )
    (net (code "222") (name "unconnected-(IC26B-REG2-Pad34)") (class "Default")
      (node (ref "IC26") (pin "34") (pinfunction "REG2_34") (pintype "output"))
    )
    (net (code "223") (name "unconnected-(X1-DN1-PadA7)") (class "Default")
      (node (ref "X1") (pin "A7") (pinfunction "DN1_A7") (pintype "bidirectional"))
    )
    (net (code "224") (name "unconnected-(X1-DN2-PadB7)") (class "Default")
      (node (ref "X1") (pin "B7") (pinfunction "DN2_B7") (pintype "bidirectional"))
    )
    (net (code "225") (name "unconnected-(X1-DP1-PadA6)") (class "Default")
      (node (ref "X1") (pin "A6") (pinfunction "DP1_A6") (pintype "bidirectional"))
    )
    (net (code "226") (name "unconnected-(X1-DP2-PadB6)") (class "Default")
      (node (ref "X1") (pin "B6") (pinfunction "DP2_B6") (pintype "bidirectional"))
    )
    (net (code "227") (name "unconnected-(X1-SBU1-PadA8)") (class "Default")
      (node (ref "X1") (pin "A8") (pinfunction "SBU1_A8") (pintype "bidirectional"))
    )
    (net (code "228") (name "unconnected-(X1-SBU2-PadB8)") (class "Default")
      (node (ref "X1") (pin "B8") (pinfunction "SBU2_B8") (pintype "bidirectional"))
    )
    (net (code "229") (name "unconnected-(X1-SSRXN1-PadB10)") (class "Default")
      (node (ref "X1") (pin "B10") (pinfunction "SSRXN1_B10") (pintype "bidirectional"))
    )
    (net (code "230") (name "unconnected-(X1-SSRXN2-PadA10)") (class "Default")
      (node (ref "X1") (pin "A10") (pinfunction "SSRXN2_A10") (pintype "bidirectional"))
    )
    (net (code "231") (name "unconnected-(X1-SSRXP1-PadB11)") (class "Default")
      (node (ref "X1") (pin "B11") (pinfunction "SSRXP1_B11") (pintype "bidirectional"))
    )
    (net (code "232") (name "unconnected-(X1-SSRXP2-PadA11)") (class "Default")
      (node (ref "X1") (pin "A11") (pinfunction "SSRXP2_A11") (pintype "bidirectional"))
    )
    (net (code "233") (name "unconnected-(X1-SSTXN1-PadA3)") (class "Default")
      (node (ref "X1") (pin "A3") (pinfunction "SSTXN1_A3") (pintype "bidirectional"))
    )
    (net (code "234") (name "unconnected-(X1-SSTXN2-PadB3)") (class "Default")
      (node (ref "X1") (pin "B3") (pinfunction "SSTXN2_B3") (pintype "bidirectional"))
    )
    (net (code "235") (name "unconnected-(X1-SSTXP1-PadA2)") (class "Default")
      (node (ref "X1") (pin "A2") (pinfunction "SSTXP1_A2") (pintype "bidirectional"))
    )
    (net (code "236") (name "unconnected-(X1-SSTXP2-PadB2)") (class "Default")
      (node (ref "X1") (pin "B2") (pinfunction "SSTXP2_B2") (pintype "bidirectional"))
    )
  )
)
